# LautIOProto2.net
KiCad netlist of a schematic drawn in EAGLE
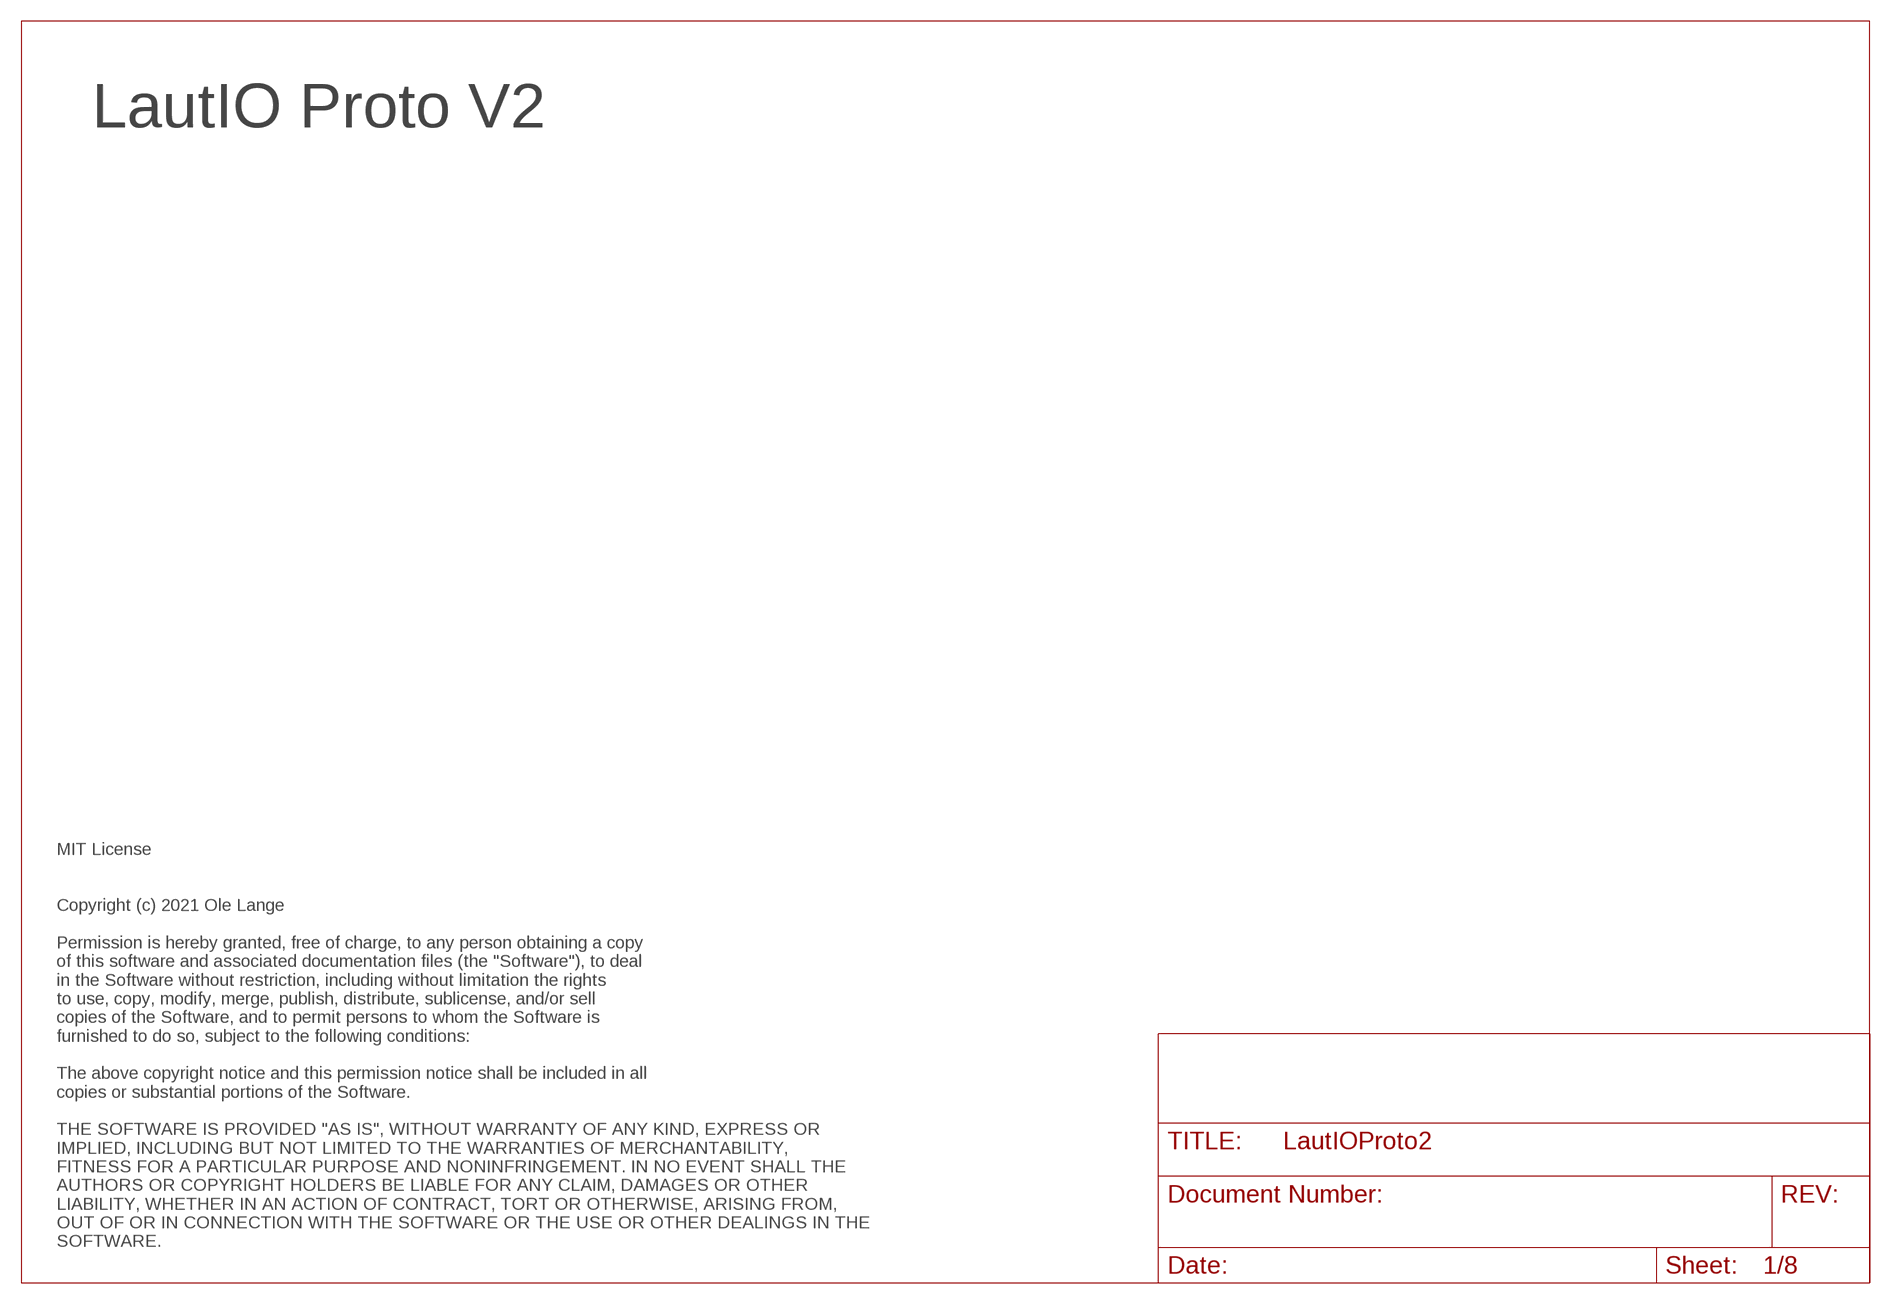
[diagram p0: schematic, sheet 1]
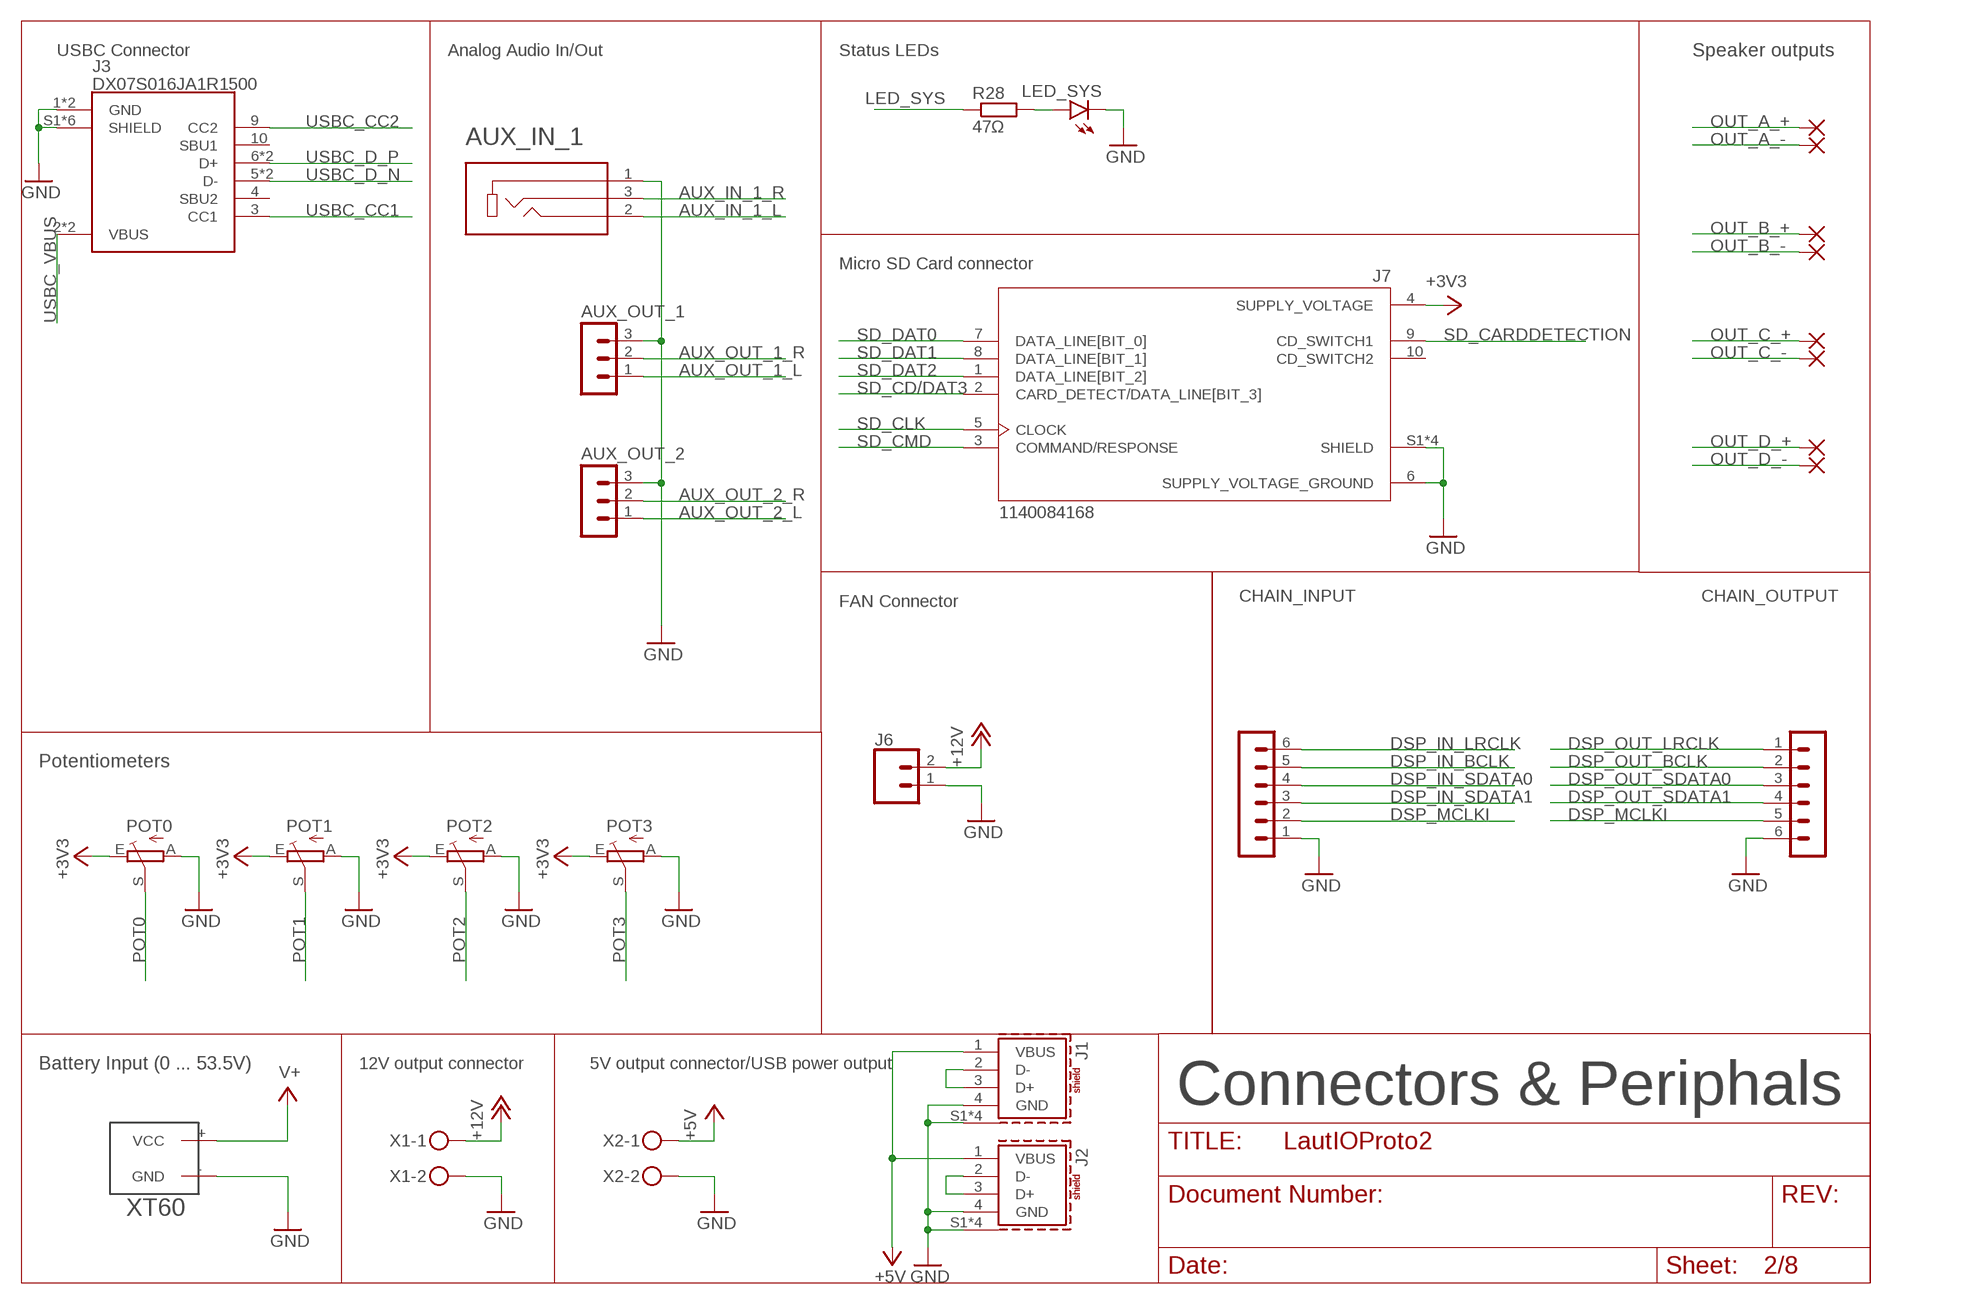
[diagram p1: schematic, sheet 2]
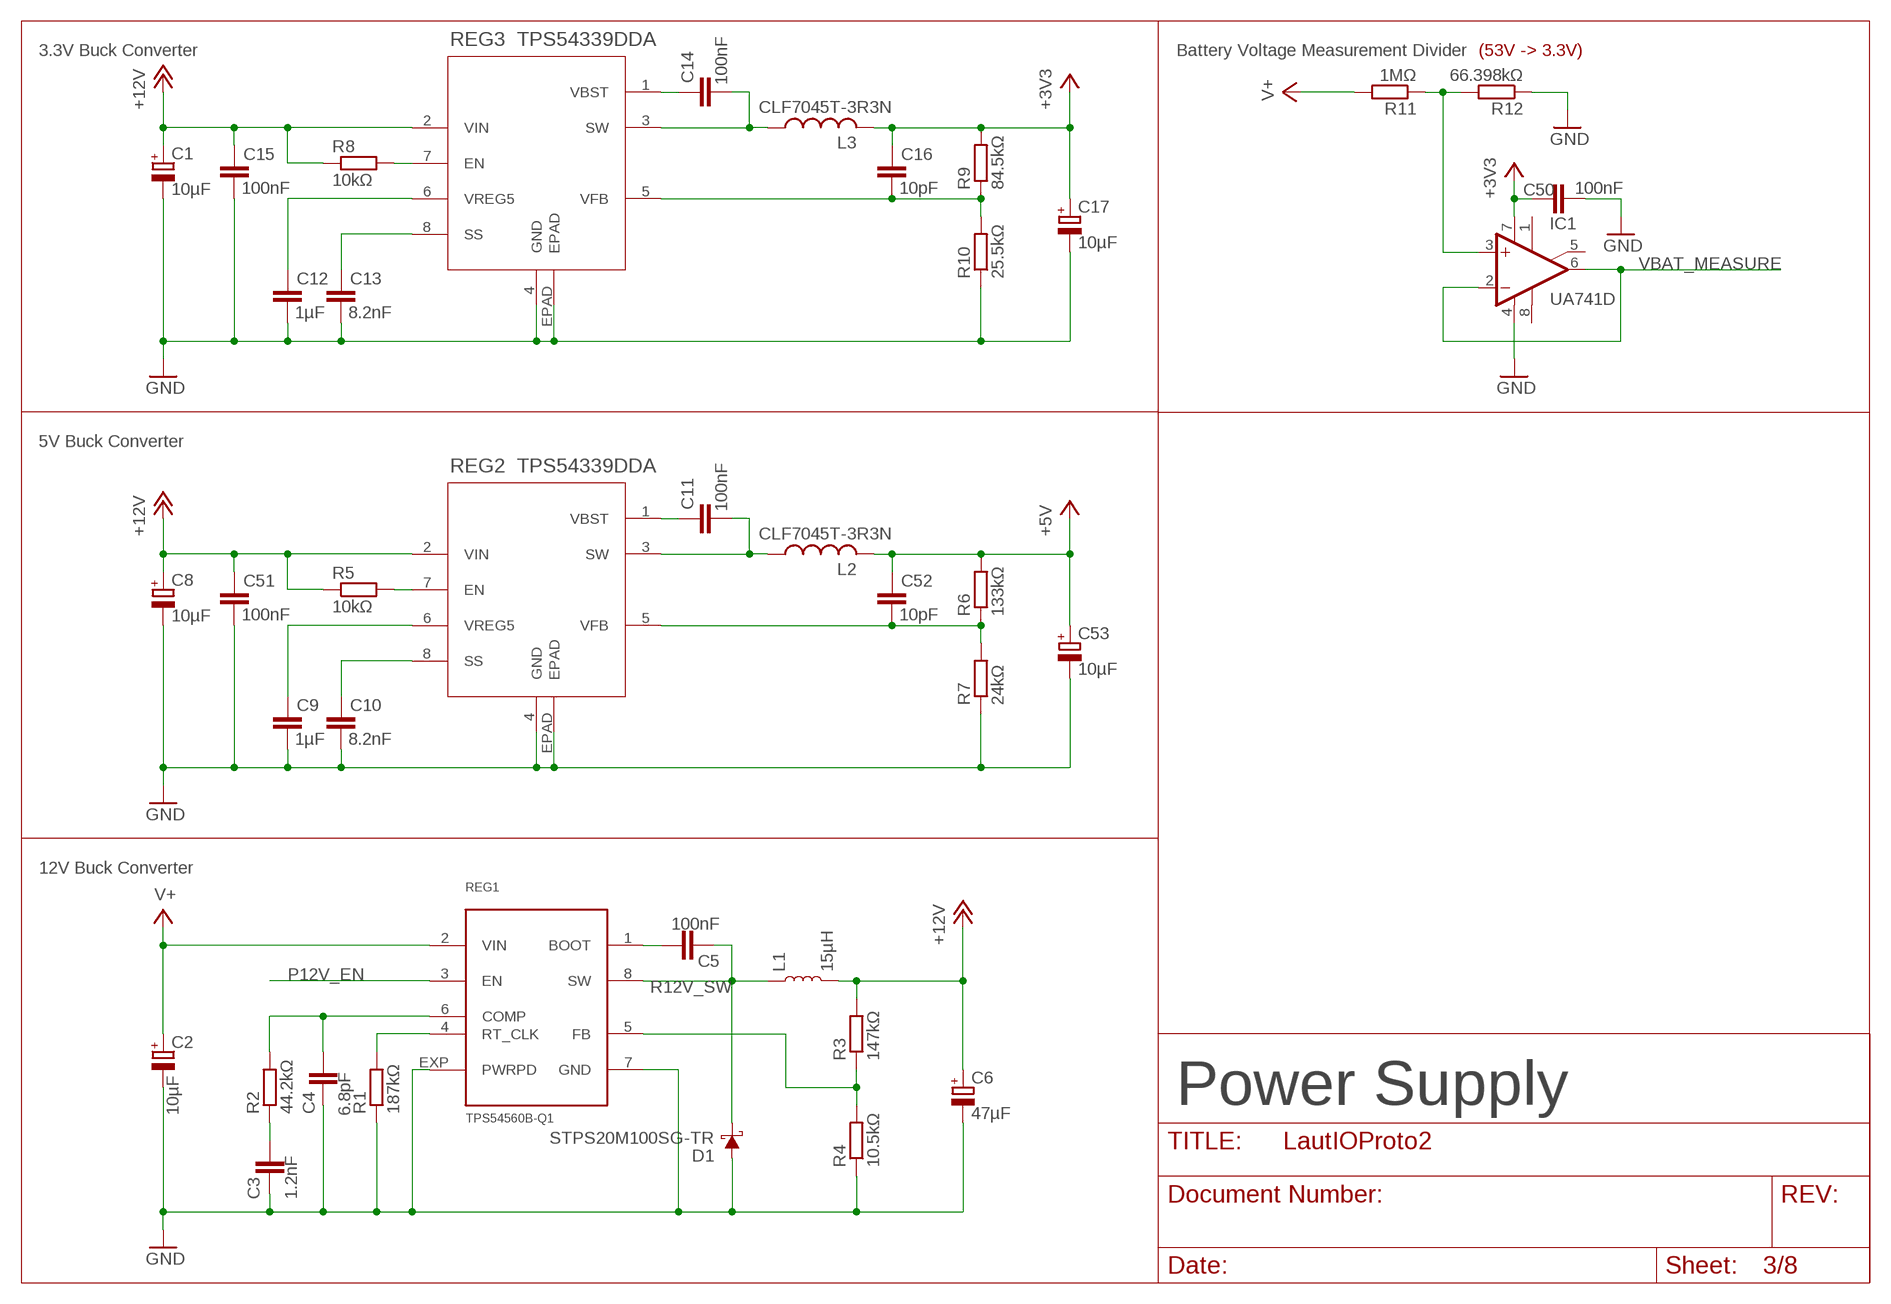
[diagram p2: schematic, sheet 3]
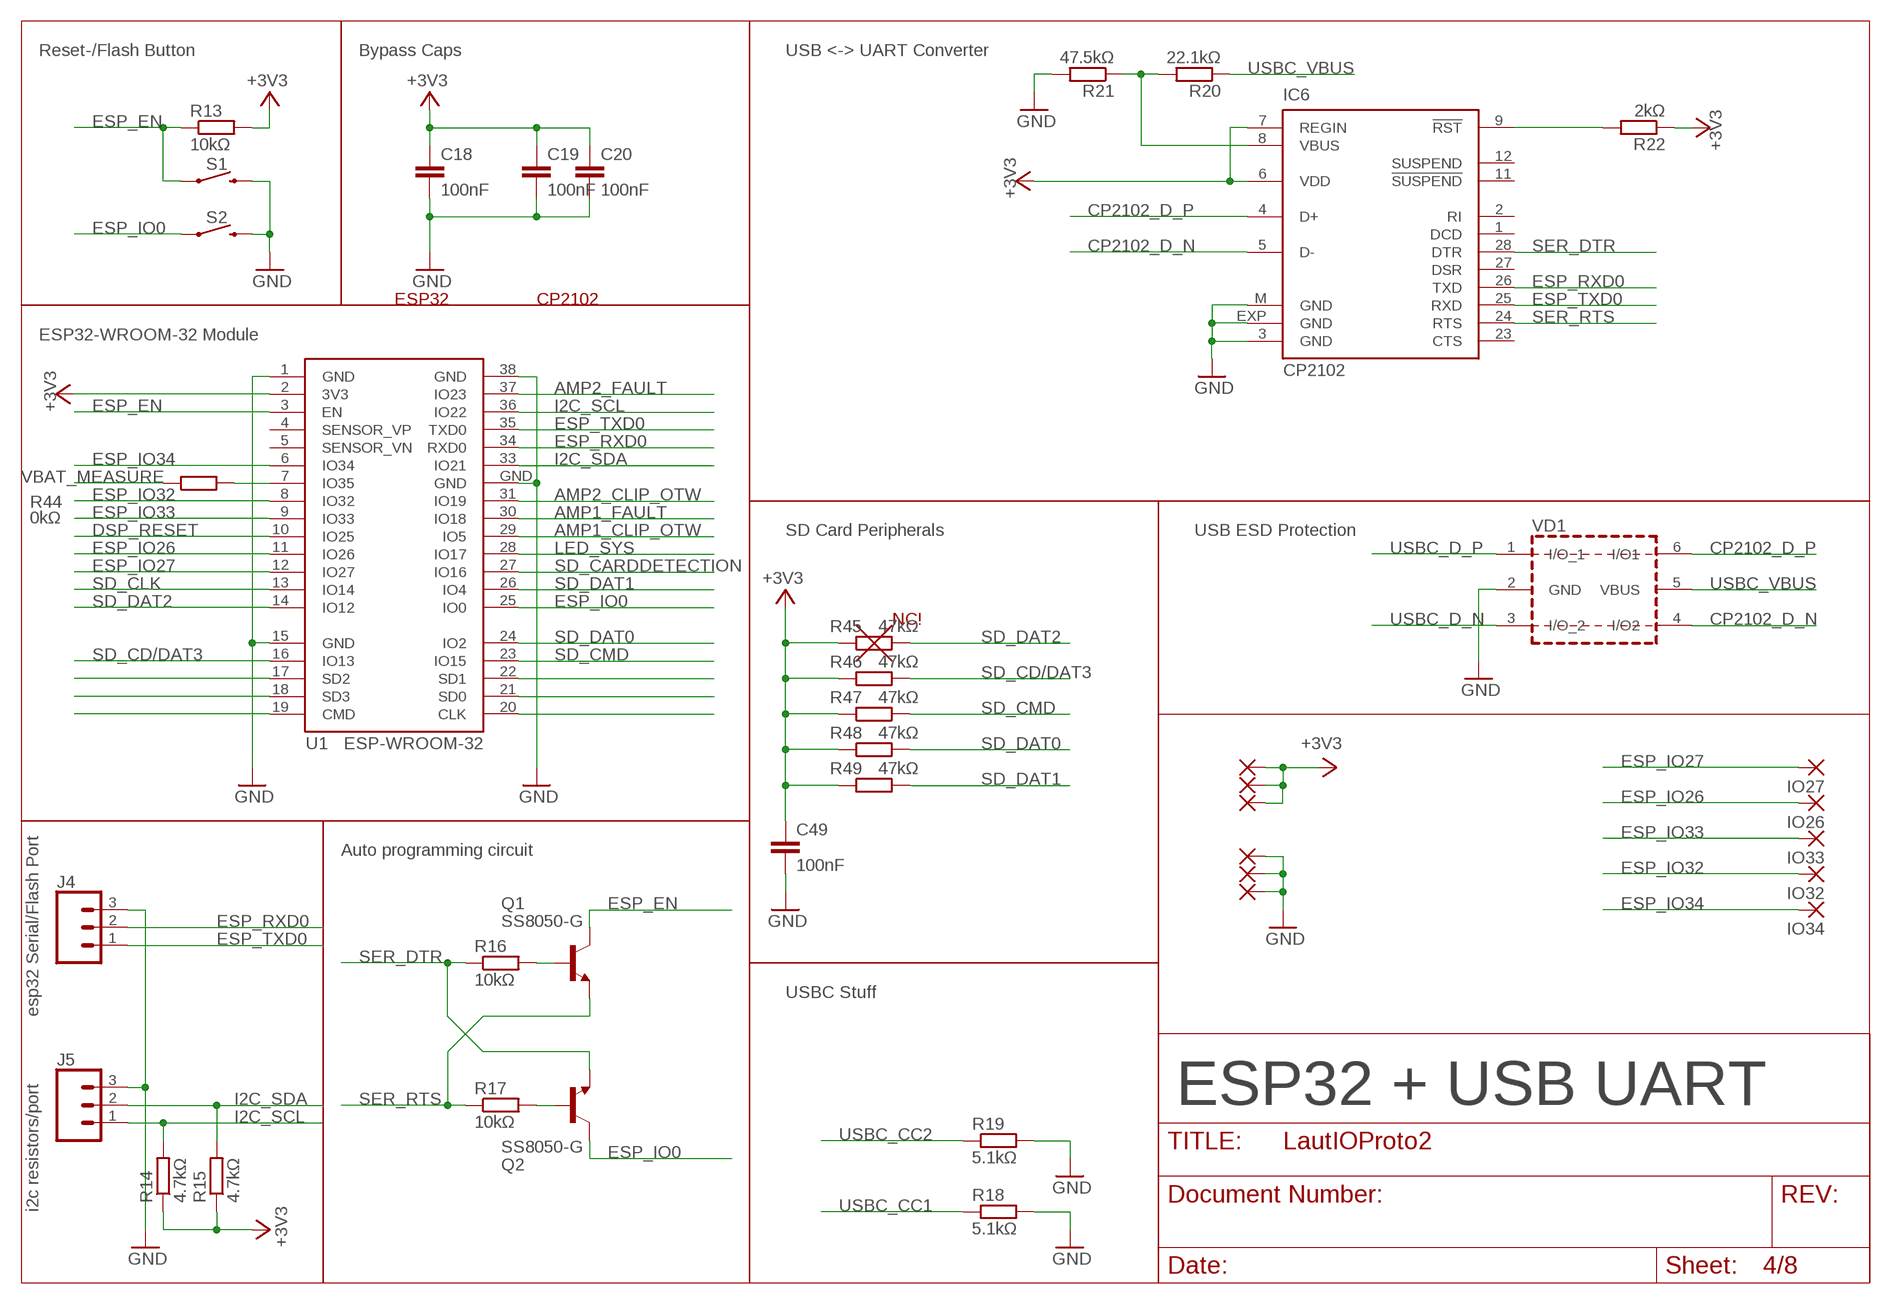
[diagram p3: schematic, sheet 4]
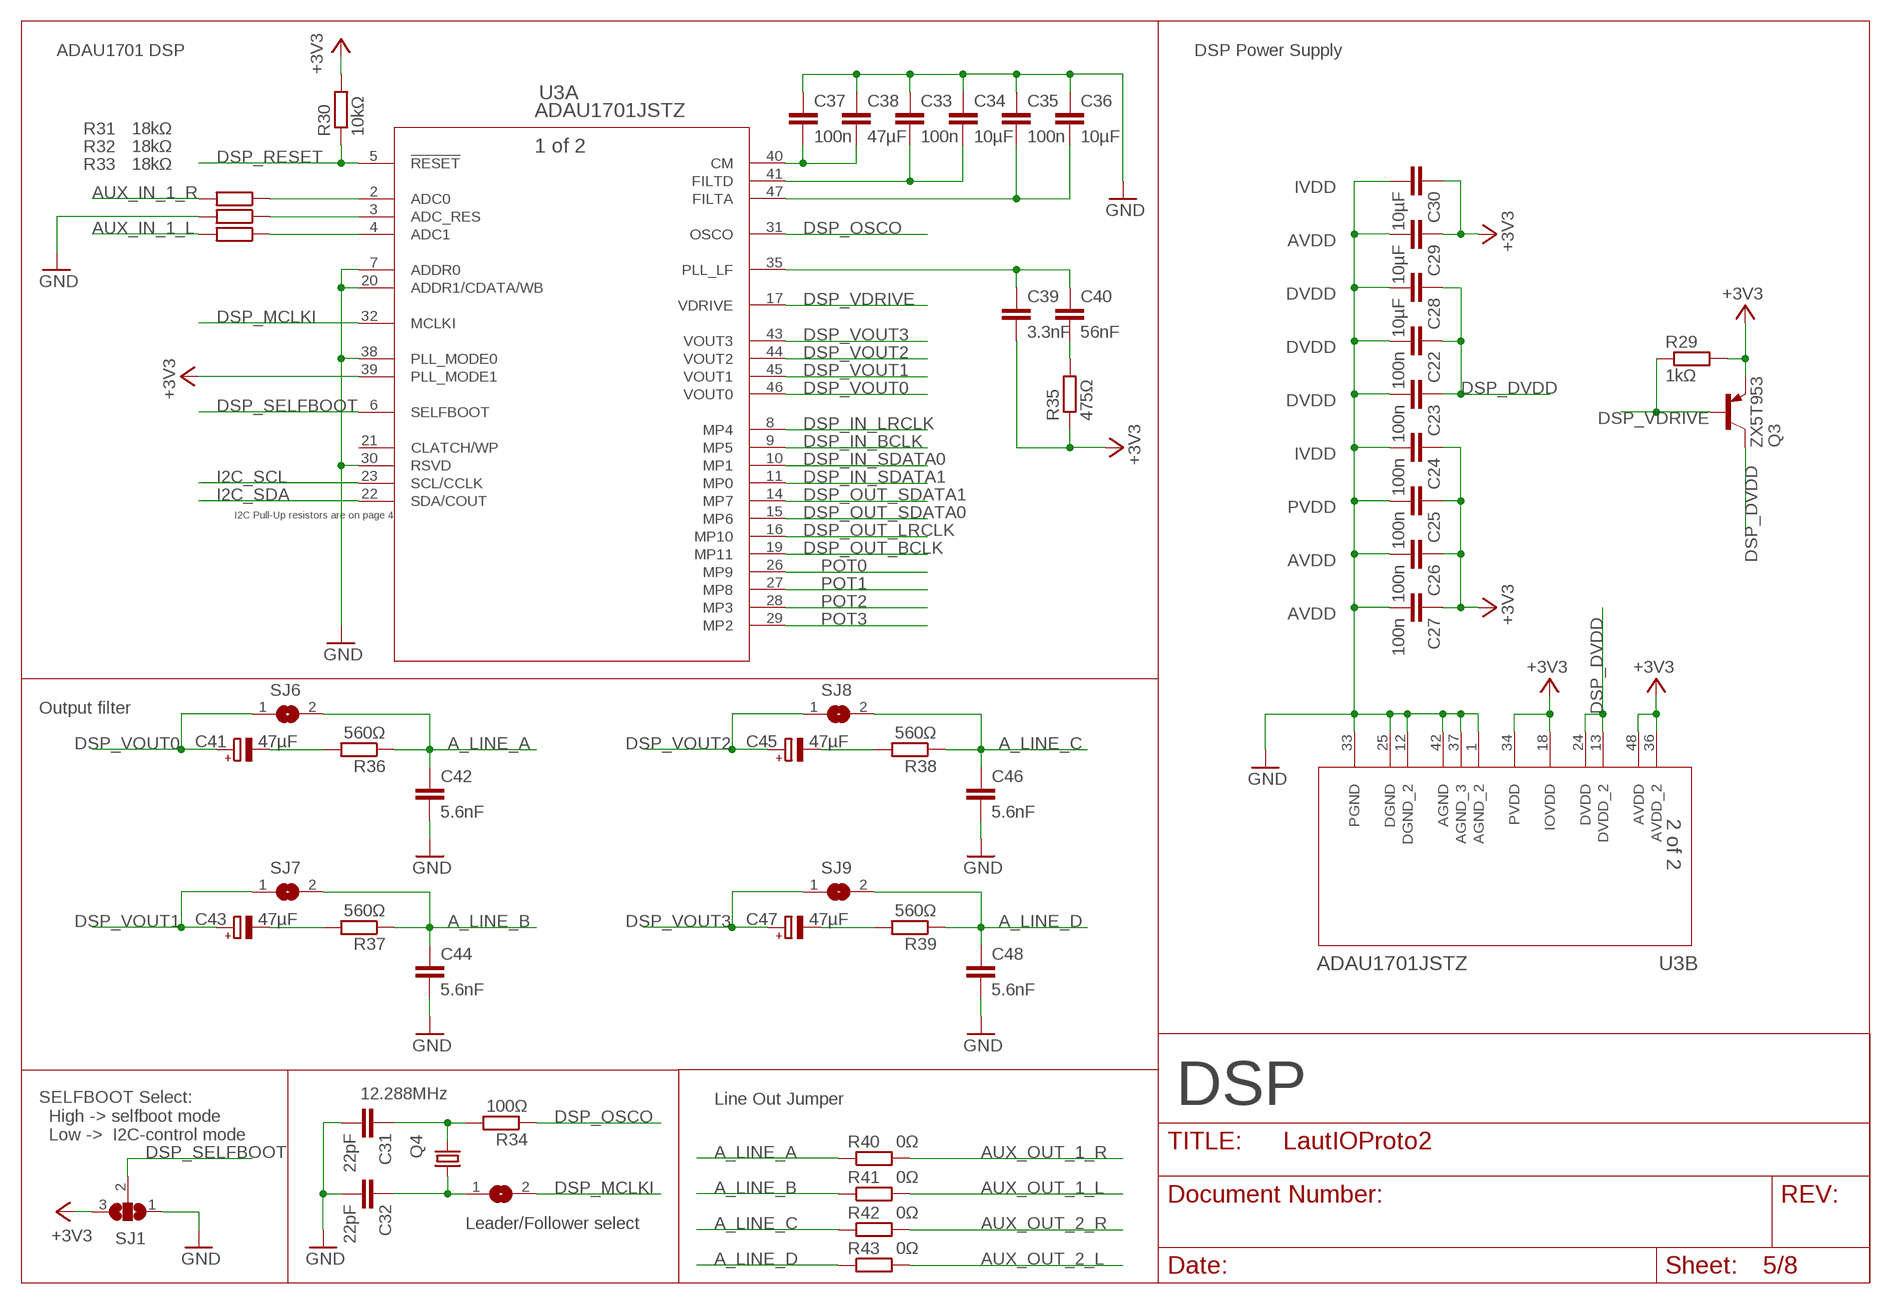
[diagram p4: schematic, sheet 5]
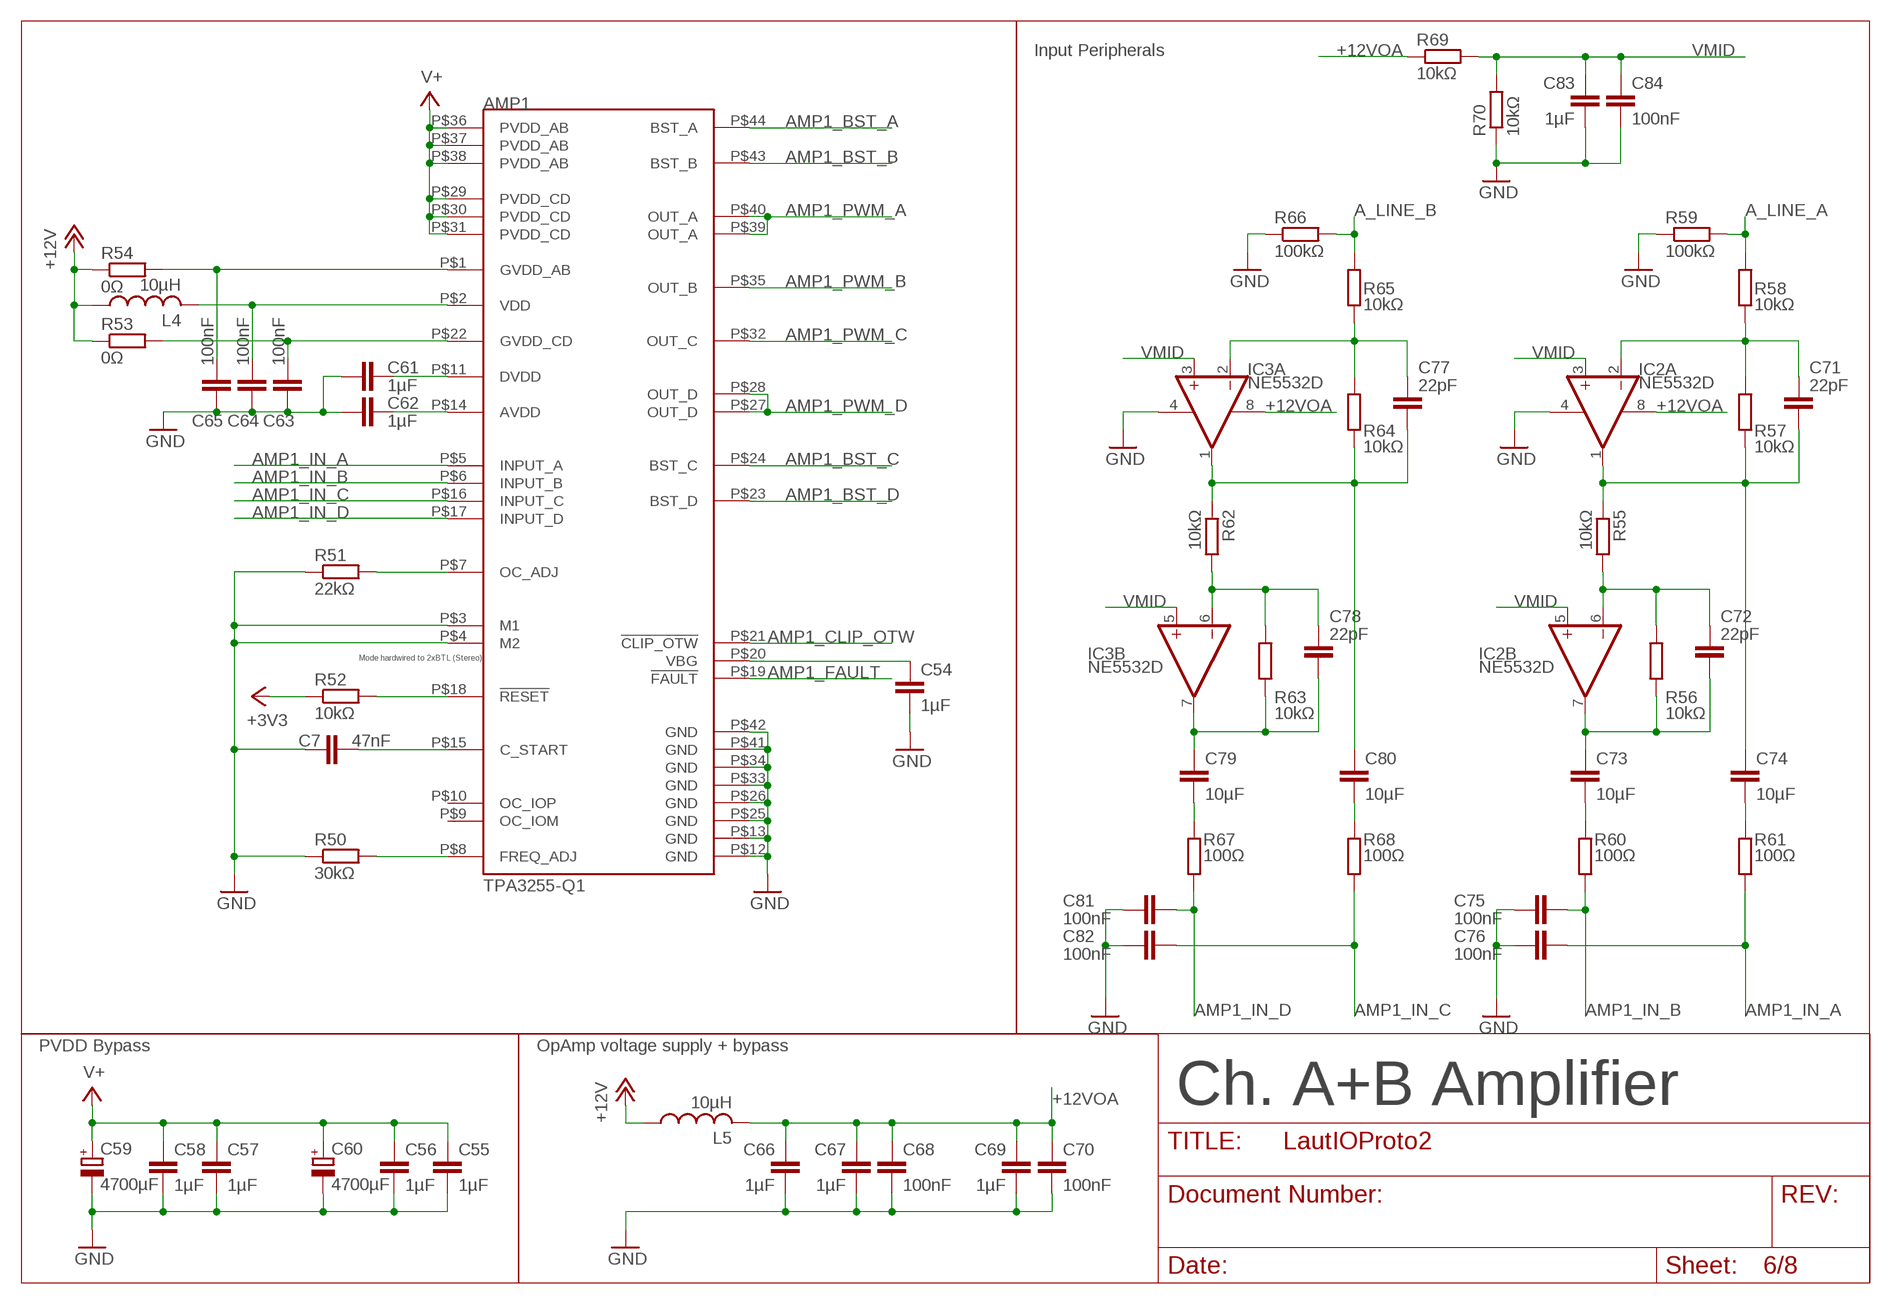
[diagram p5: schematic, sheet 6]
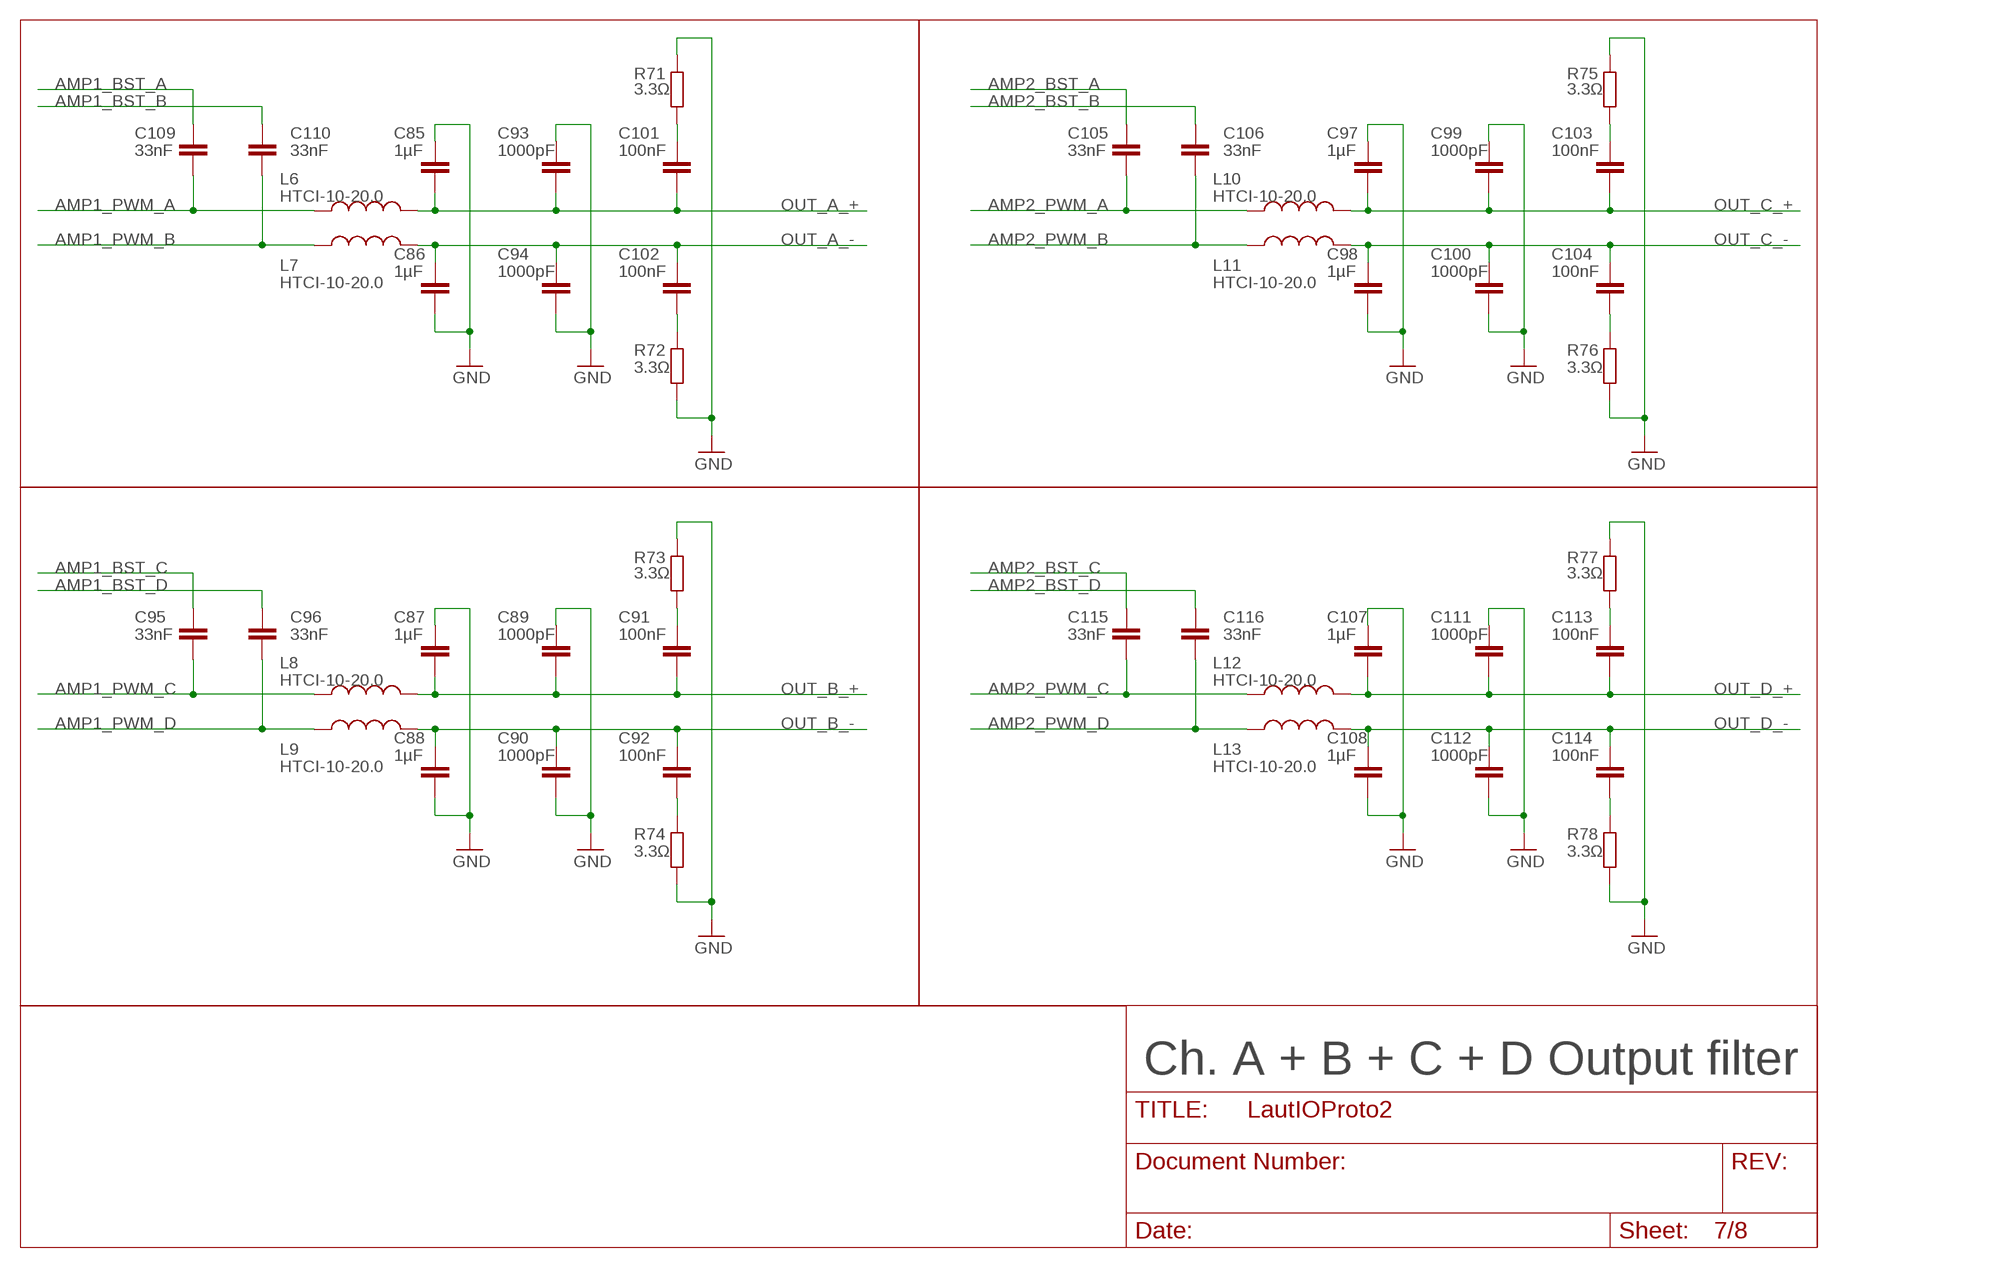
[diagram p6: schematic, sheet 7]
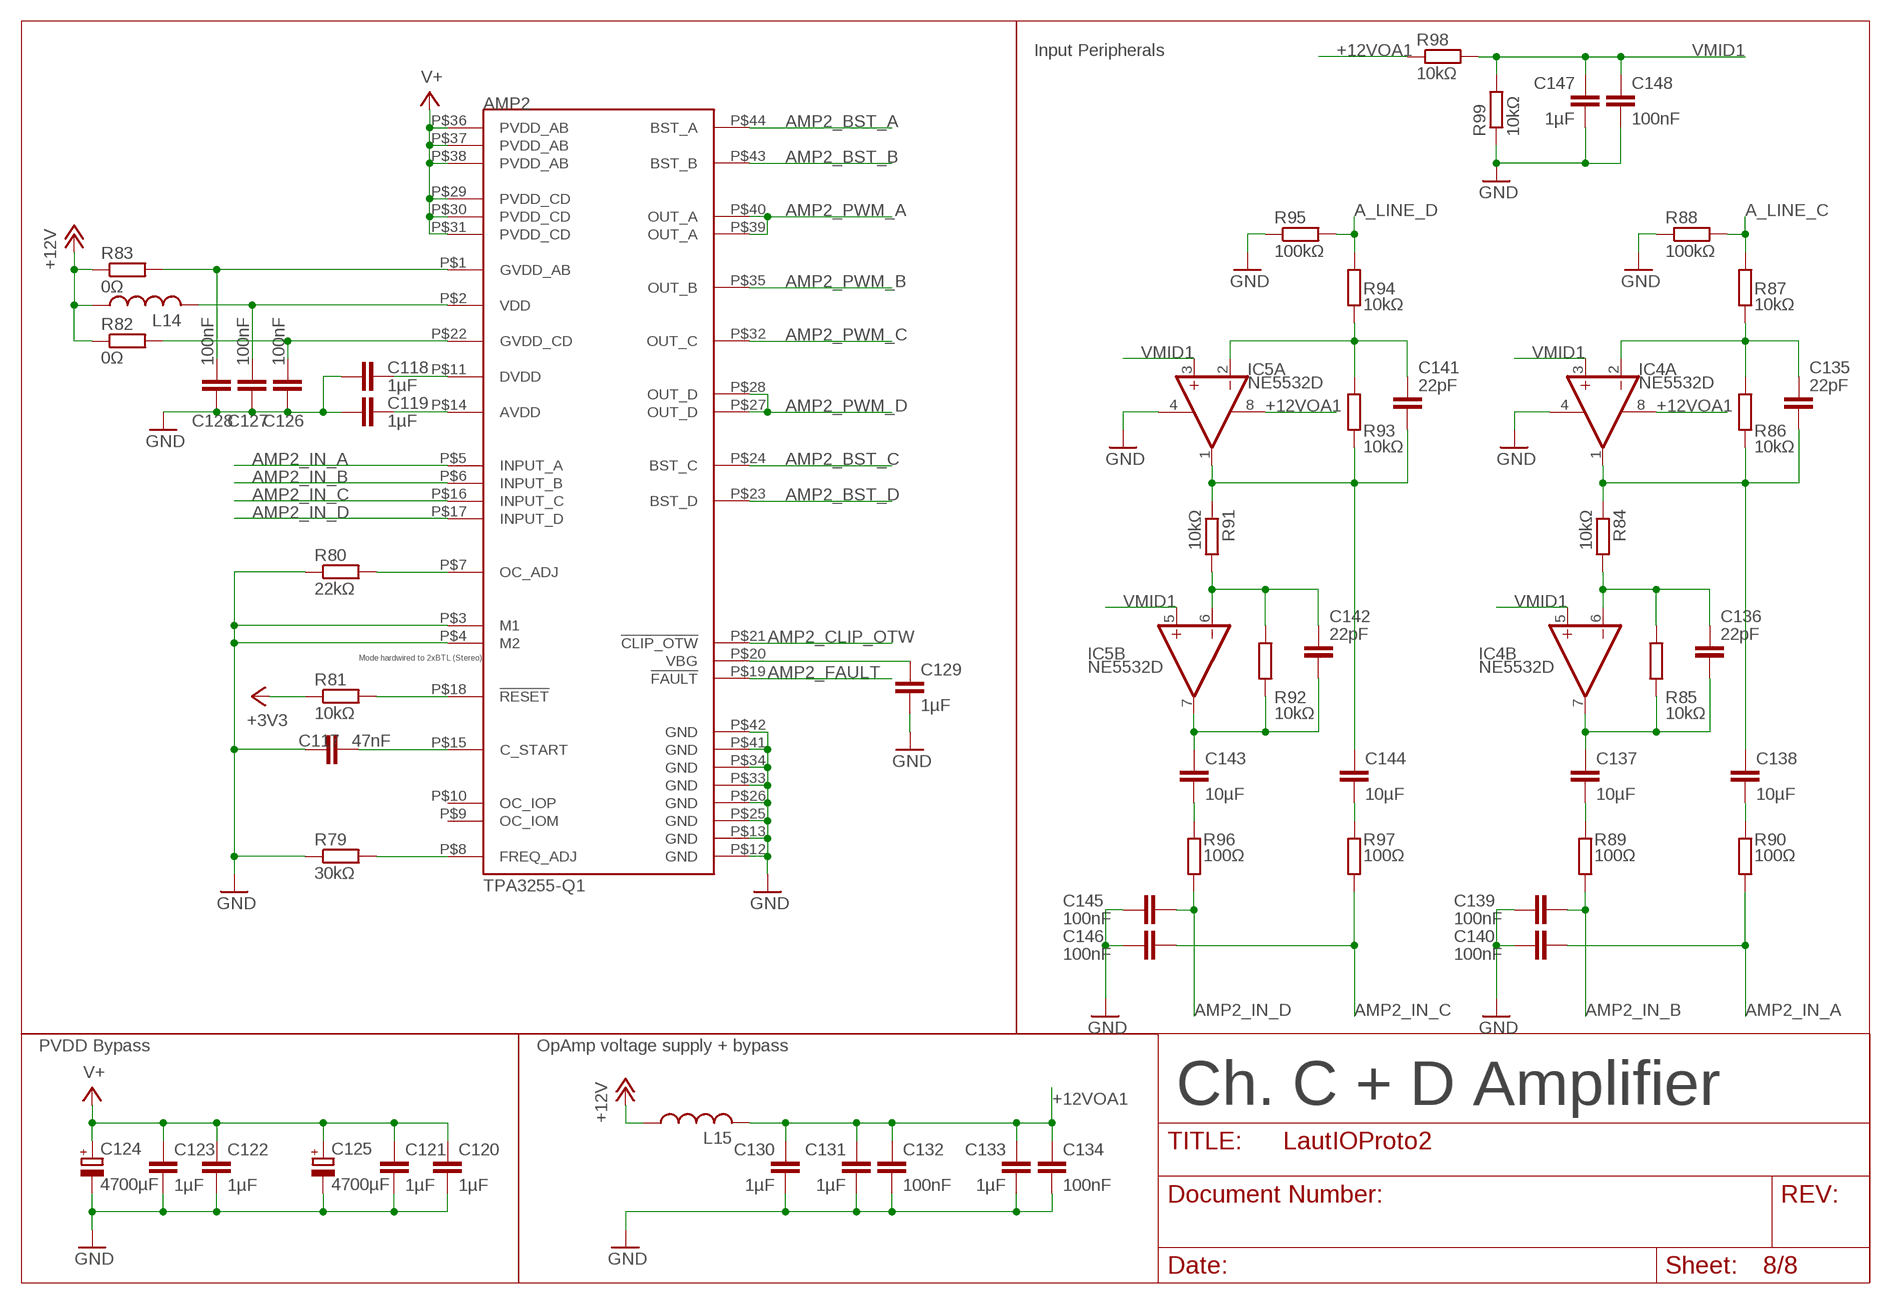
[diagram p7: schematic, sheet 8]

(export (version "E")
  (design (tool "Eeschema 10.0.6"))
  (components
    (comp (ref "AMP2")
      (value "TPA3255-Q1")
      (footprint "eagle-import:HTSSOP44")
      (libsource (lib "eagle-import") (part "TPA3255-Q1"))
    )
    (comp (ref "C117")
      (value "47nF")
      (footprint "eagle-import:C0603")
      (libsource (lib "eagle-import") (part "C-EUC0603"))
    )
    (comp (ref "C118")
      (value "1µF")
      (footprint "eagle-import:C3216")
      (libsource (lib "eagle-import") (part "C-EUC3216"))
    )
    (comp (ref "C119")
      (value "1µF")
      (footprint "eagle-import:C3216")
      (libsource (lib "eagle-import") (part "C-EUC3216"))
    )
    (comp (ref "C120")
      (value "1µF")
      (footprint "eagle-import:C3216")
      (libsource (lib "eagle-import") (part "C-EUC3216"))
    )
    (comp (ref "C121")
      (value "1µF")
      (footprint "eagle-import:C3216")
      (libsource (lib "eagle-import") (part "C-EUC3216"))
    )
    (comp (ref "C122")
      (value "1µF")
      (footprint "eagle-import:C3216")
      (libsource (lib "eagle-import") (part "C-EUC3216"))
    )
    (comp (ref "C123")
      (value "1µF")
      (footprint "eagle-import:C3216")
      (libsource (lib "eagle-import") (part "C-EUC3216"))
    )
    (comp (ref "C124")
      (value "4700µF")
      (footprint "eagle-import:EB22,5D")
      (libsource (lib "eagle-import") (part "CPOL-EUE10-22.5"))
    )
    (comp (ref "C125")
      (value "4700µF")
      (footprint "eagle-import:EB22,5D")
      (libsource (lib "eagle-import") (part "CPOL-EUE10-22.5"))
    )
    (comp (ref "C126")
      (value "100nF")
      (footprint "eagle-import:C0603")
      (libsource (lib "eagle-import") (part "C-EUC0603"))
    )
    (comp (ref "C127")
      (value "100nF")
      (footprint "eagle-import:C0603")
      (libsource (lib "eagle-import") (part "C-EUC0603"))
    )
    (comp (ref "C128")
      (value "100nF")
      (footprint "eagle-import:C0603")
      (libsource (lib "eagle-import") (part "C-EUC0603"))
    )
    (comp (ref "C129")
      (value "1µF")
      (footprint "eagle-import:C3216")
      (libsource (lib "eagle-import") (part "C-EUC3216"))
    )
    (comp (ref "C130")
      (value "1µF")
      (footprint "eagle-import:C3216")
      (libsource (lib "eagle-import") (part "C-EUC3216"))
    )
    (comp (ref "C131")
      (value "1µF")
      (footprint "eagle-import:C3216")
      (libsource (lib "eagle-import") (part "C-EUC3216"))
    )
    (comp (ref "C132")
      (value "100nF")
      (footprint "eagle-import:C0603")
      (libsource (lib "eagle-import") (part "C-EUC0603"))
    )
    (comp (ref "C133")
      (value "1µF")
      (footprint "eagle-import:C3216")
      (libsource (lib "eagle-import") (part "C-EUC3216"))
    )
    (comp (ref "C134")
      (value "100nF")
      (footprint "eagle-import:C0603")
      (libsource (lib "eagle-import") (part "C-EUC0603"))
    )
    (comp (ref "C135")
      (value "22pF")
      (footprint "eagle-import:C0603")
      (libsource (lib "eagle-import") (part "C-EUC0603"))
    )
    (comp (ref "C136")
      (value "22pF")
      (footprint "eagle-import:C0603")
      (libsource (lib "eagle-import") (part "C-EUC0603"))
    )
    (comp (ref "C137")
      (value "10µF")
      (footprint "eagle-import:C3216")
      (libsource (lib "eagle-import") (part "C-EUC3216"))
    )
    (comp (ref "C138")
      (value "10µF")
      (footprint "eagle-import:C3216")
      (libsource (lib "eagle-import") (part "C-EUC3216"))
    )
    (comp (ref "C139")
      (value "100nF")
      (footprint "eagle-import:C0603")
      (libsource (lib "eagle-import") (part "C-EUC0603"))
    )
    (comp (ref "C140")
      (value "100nF")
      (footprint "eagle-import:C0603")
      (libsource (lib "eagle-import") (part "C-EUC0603"))
    )
    (comp (ref "C141")
      (value "22pF")
      (footprint "eagle-import:C0603")
      (libsource (lib "eagle-import") (part "C-EUC0603"))
    )
    (comp (ref "C142")
      (value "22pF")
      (footprint "eagle-import:C0603")
      (libsource (lib "eagle-import") (part "C-EUC0603"))
    )
    (comp (ref "C143")
      (value "10µF")
      (footprint "eagle-import:C3216")
      (libsource (lib "eagle-import") (part "C-EUC3216"))
    )
    (comp (ref "C144")
      (value "10µF")
      (footprint "eagle-import:C3216")
      (libsource (lib "eagle-import") (part "C-EUC3216"))
    )
    (comp (ref "C145")
      (value "100nF")
      (footprint "eagle-import:C0603")
      (libsource (lib "eagle-import") (part "C-EUC0603"))
    )
    (comp (ref "C146")
      (value "100nF")
      (footprint "eagle-import:C0603")
      (libsource (lib "eagle-import") (part "C-EUC0603"))
    )
    (comp (ref "C147")
      (value "1µF")
      (footprint "eagle-import:C3216")
      (libsource (lib "eagle-import") (part "C-EUC3216"))
    )
    (comp (ref "C148")
      (value "100nF")
      (footprint "eagle-import:C0603")
      (libsource (lib "eagle-import") (part "C-EUC0603"))
    )
    (comp (ref "IC4")
      (value "NE5532D")
      (footprint "eagle-import:SO08")
      (libsource (lib "eagle-import") (part "NE5532D"))
    )
    (comp (ref "IC5")
      (value "NE5532D")
      (footprint "eagle-import:SO08")
      (libsource (lib "eagle-import") (part "NE5532D"))
    )
    (comp (ref "L14")
      (value "L-USL2012C")
      (footprint "eagle-import:L2012C")
      (libsource (lib "eagle-import") (part "L-USL2012C"))
    )
    (comp (ref "L15")
      (value "L-USL2012C")
      (footprint "eagle-import:L2012C")
      (libsource (lib "eagle-import") (part "L-USL2012C"))
    )
    (comp (ref "R79")
      (value "30kΩ")
      (footprint "eagle-import:R0603")
      (libsource (lib "eagle-import") (part "R-EU_R0603"))
    )
    (comp (ref "R80")
      (value "22kΩ")
      (footprint "eagle-import:R0603")
      (libsource (lib "eagle-import") (part "R-EU_R0603"))
    )
    (comp (ref "R81")
      (value "10kΩ")
      (footprint "eagle-import:R0603")
      (libsource (lib "eagle-import") (part "R-EU_R0603"))
    )
    (comp (ref "R82")
      (value "0Ω")
      (footprint "eagle-import:R0603")
      (libsource (lib "eagle-import") (part "R-EU_R0603"))
    )
    (comp (ref "R83")
      (value "0Ω")
      (footprint "eagle-import:R0603")
      (libsource (lib "eagle-import") (part "R-EU_R0603"))
    )
    (comp (ref "R84")
      (value "10kΩ")
      (footprint "eagle-import:R0603")
      (libsource (lib "eagle-import") (part "R-EU_R0603"))
    )
    (comp (ref "R85")
      (value "10kΩ")
      (footprint "eagle-import:R0603")
      (libsource (lib "eagle-import") (part "R-EU_R0603"))
    )
    (comp (ref "R86")
      (value "10kΩ")
      (footprint "eagle-import:R0603")
      (libsource (lib "eagle-import") (part "R-EU_R0603"))
    )
    (comp (ref "R87")
      (value "10kΩ")
      (footprint "eagle-import:R0603")
      (libsource (lib "eagle-import") (part "R-EU_R0603"))
    )
    (comp (ref "R88")
      (value "100kΩ")
      (footprint "eagle-import:R0603")
      (libsource (lib "eagle-import") (part "R-EU_R0603"))
    )
    (comp (ref "R89")
      (value "100Ω")
      (footprint "eagle-import:R0603")
      (libsource (lib "eagle-import") (part "R-EU_R0603"))
    )
    (comp (ref "R90")
      (value "100Ω")
      (footprint "eagle-import:R0603")
      (libsource (lib "eagle-import") (part "R-EU_R0603"))
    )
    (comp (ref "R91")
      (value "10kΩ")
      (footprint "eagle-import:R0603")
      (libsource (lib "eagle-import") (part "R-EU_R0603"))
    )
    (comp (ref "R92")
      (value "10kΩ")
      (footprint "eagle-import:R0603")
      (libsource (lib "eagle-import") (part "R-EU_R0603"))
    )
    (comp (ref "R93")
      (value "10kΩ")
      (footprint "eagle-import:R0603")
      (libsource (lib "eagle-import") (part "R-EU_R0603"))
    )
    (comp (ref "R94")
      (value "10kΩ")
      (footprint "eagle-import:R0603")
      (libsource (lib "eagle-import") (part "R-EU_R0603"))
    )
    (comp (ref "R95")
      (value "100kΩ")
      (footprint "eagle-import:R0603")
      (libsource (lib "eagle-import") (part "R-EU_R0603"))
    )
    (comp (ref "R96")
      (value "100Ω")
      (footprint "eagle-import:R0603")
      (libsource (lib "eagle-import") (part "R-EU_R0603"))
    )
    (comp (ref "R97")
      (value "100Ω")
      (footprint "eagle-import:R0603")
      (libsource (lib "eagle-import") (part "R-EU_R0603"))
    )
    (comp (ref "R98")
      (value "10kΩ")
      (footprint "eagle-import:R0603")
      (libsource (lib "eagle-import") (part "R-EU_R0603"))
    )
    (comp (ref "R99")
      (value "10kΩ")
      (footprint "eagle-import:R0603")
      (libsource (lib "eagle-import") (part "R-EU_R0603"))
    )
    (comp (ref "AMP1")
      (value "TPA3255-Q1")
      (footprint "eagle-import:HTSSOP44")
      (libsource (lib "eagle-import") (part "TPA3255-Q1"))
    )
    (comp (ref "C7")
      (value "47nF")
      (footprint "eagle-import:C0603")
      (libsource (lib "eagle-import") (part "C-EUC0603"))
    )
    (comp (ref "C54")
      (value "1µF")
      (footprint "eagle-import:C3216")
      (libsource (lib "eagle-import") (part "C-EUC3216"))
    )
    (comp (ref "C55")
      (value "1µF")
      (footprint "eagle-import:C3216")
      (libsource (lib "eagle-import") (part "C-EUC3216"))
    )
    (comp (ref "C56")
      (value "1µF")
      (footprint "eagle-import:C3216")
      (libsource (lib "eagle-import") (part "C-EUC3216"))
    )
    (comp (ref "C57")
      (value "1µF")
      (footprint "eagle-import:C3216")
      (libsource (lib "eagle-import") (part "C-EUC3216"))
    )
    (comp (ref "C58")
      (value "1µF")
      (footprint "eagle-import:C3216")
      (libsource (lib "eagle-import") (part "C-EUC3216"))
    )
    (comp (ref "C59")
      (value "4700µF")
      (footprint "eagle-import:EB22,5D")
      (libsource (lib "eagle-import") (part "CPOL-EUE10-22.5"))
    )
    (comp (ref "C60")
      (value "4700µF")
      (footprint "eagle-import:EB22,5D")
      (libsource (lib "eagle-import") (part "CPOL-EUE10-22.5"))
    )
    (comp (ref "C61")
      (value "1µF")
      (footprint "eagle-import:C3216")
      (libsource (lib "eagle-import") (part "C-EUC3216"))
    )
    (comp (ref "C62")
      (value "1µF")
      (footprint "eagle-import:C3216")
      (libsource (lib "eagle-import") (part "C-EUC3216"))
    )
    (comp (ref "C63")
      (value "100nF")
      (footprint "eagle-import:C0603")
      (libsource (lib "eagle-import") (part "C-EUC0603"))
    )
    (comp (ref "C64")
      (value "100nF")
      (footprint "eagle-import:C0603")
      (libsource (lib "eagle-import") (part "C-EUC0603"))
    )
    (comp (ref "C65")
      (value "100nF")
      (footprint "eagle-import:C0603")
      (libsource (lib "eagle-import") (part "C-EUC0603"))
    )
    (comp (ref "C66")
      (value "1µF")
      (footprint "eagle-import:C3216")
      (libsource (lib "eagle-import") (part "C-EUC3216"))
    )
    (comp (ref "C67")
      (value "1µF")
      (footprint "eagle-import:C3216")
      (libsource (lib "eagle-import") (part "C-EUC3216"))
    )
    (comp (ref "C68")
      (value "100nF")
      (footprint "eagle-import:C0603")
      (libsource (lib "eagle-import") (part "C-EUC0603"))
    )
    (comp (ref "C69")
      (value "1µF")
      (footprint "eagle-import:C3216")
      (libsource (lib "eagle-import") (part "C-EUC3216"))
    )
    (comp (ref "C70")
      (value "100nF")
      (footprint "eagle-import:C0603")
      (libsource (lib "eagle-import") (part "C-EUC0603"))
    )
    (comp (ref "C71")
      (value "22pF")
      (footprint "eagle-import:C0603")
      (libsource (lib "eagle-import") (part "C-EUC0603"))
    )
    (comp (ref "C72")
      (value "22pF")
      (footprint "eagle-import:C0603")
      (libsource (lib "eagle-import") (part "C-EUC0603"))
    )
    (comp (ref "C73")
      (value "10µF")
      (footprint "eagle-import:C3216")
      (libsource (lib "eagle-import") (part "C-EUC3216"))
    )
    (comp (ref "C74")
      (value "10µF")
      (footprint "eagle-import:C3216")
      (libsource (lib "eagle-import") (part "C-EUC3216"))
    )
    (comp (ref "C75")
      (value "100nF")
      (footprint "eagle-import:C0603")
      (libsource (lib "eagle-import") (part "C-EUC0603"))
    )
    (comp (ref "C76")
      (value "100nF")
      (footprint "eagle-import:C0603")
      (libsource (lib "eagle-import") (part "C-EUC0603"))
    )
    (comp (ref "C77")
      (value "22pF")
      (footprint "eagle-import:C0603")
      (libsource (lib "eagle-import") (part "C-EUC0603"))
    )
    (comp (ref "C78")
      (value "22pF")
      (footprint "eagle-import:C0603")
      (libsource (lib "eagle-import") (part "C-EUC0603"))
    )
    (comp (ref "C79")
      (value "10µF")
      (footprint "eagle-import:C3216")
      (libsource (lib "eagle-import") (part "C-EUC3216"))
    )
    (comp (ref "C80")
      (value "10µF")
      (footprint "eagle-import:C3216")
      (libsource (lib "eagle-import") (part "C-EUC3216"))
    )
    (comp (ref "C81")
      (value "100nF")
      (footprint "eagle-import:C0603")
      (libsource (lib "eagle-import") (part "C-EUC0603"))
    )
    (comp (ref "C82")
      (value "100nF")
      (footprint "eagle-import:C0603")
      (libsource (lib "eagle-import") (part "C-EUC0603"))
    )
    (comp (ref "C83")
      (value "1µF")
      (footprint "eagle-import:C3216")
      (libsource (lib "eagle-import") (part "C-EUC3216"))
    )
    (comp (ref "C84")
      (value "100nF")
      (footprint "eagle-import:C0603")
      (libsource (lib "eagle-import") (part "C-EUC0603"))
    )
    (comp (ref "IC2")
      (value "NE5532D")
      (footprint "eagle-import:SO08")
      (libsource (lib "eagle-import") (part "NE5532D"))
    )
    (comp (ref "IC3")
      (value "NE5532D")
      (footprint "eagle-import:SO08")
      (libsource (lib "eagle-import") (part "NE5532D"))
    )
    (comp (ref "L4")
      (value "10µH")
      (footprint "eagle-import:L2012C")
      (libsource (lib "eagle-import") (part "L-USL2012C"))
    )
    (comp (ref "L5")
      (value "10µH")
      (footprint "eagle-import:L2012C")
      (libsource (lib "eagle-import") (part "L-USL2012C"))
    )
    (comp (ref "R50")
      (value "30kΩ")
      (footprint "eagle-import:R0603")
      (libsource (lib "eagle-import") (part "R-EU_R0603"))
    )
    (comp (ref "R51")
      (value "22kΩ")
      (footprint "eagle-import:R0603")
      (libsource (lib "eagle-import") (part "R-EU_R0603"))
    )
    (comp (ref "R52")
      (value "10kΩ")
      (footprint "eagle-import:R0603")
      (libsource (lib "eagle-import") (part "R-EU_R0603"))
    )
    (comp (ref "R53")
      (value "0Ω")
      (footprint "eagle-import:R0603")
      (libsource (lib "eagle-import") (part "R-EU_R0603"))
    )
    (comp (ref "R54")
      (value "0Ω")
      (footprint "eagle-import:R0603")
      (libsource (lib "eagle-import") (part "R-EU_R0603"))
    )
    (comp (ref "R55")
      (value "10kΩ")
      (footprint "eagle-import:R0603")
      (libsource (lib "eagle-import") (part "R-EU_R0603"))
    )
    (comp (ref "R56")
      (value "10kΩ")
      (footprint "eagle-import:R0603")
      (libsource (lib "eagle-import") (part "R-EU_R0603"))
    )
    (comp (ref "R57")
      (value "10kΩ")
      (footprint "eagle-import:R0603")
      (libsource (lib "eagle-import") (part "R-EU_R0603"))
    )
    (comp (ref "R58")
      (value "10kΩ")
      (footprint "eagle-import:R0603")
      (libsource (lib "eagle-import") (part "R-EU_R0603"))
    )
    (comp (ref "R59")
      (value "100kΩ")
      (footprint "eagle-import:R0603")
      (libsource (lib "eagle-import") (part "R-EU_R0603"))
    )
    (comp (ref "R60")
      (value "100Ω")
      (footprint "eagle-import:R0603")
      (libsource (lib "eagle-import") (part "R-EU_R0603"))
    )
    (comp (ref "R61")
      (value "100Ω")
      (footprint "eagle-import:R0603")
      (libsource (lib "eagle-import") (part "R-EU_R0603"))
    )
    (comp (ref "R62")
      (value "10kΩ")
      (footprint "eagle-import:R0603")
      (libsource (lib "eagle-import") (part "R-EU_R0603"))
    )
    (comp (ref "R63")
      (value "10kΩ")
      (footprint "eagle-import:R0603")
      (libsource (lib "eagle-import") (part "R-EU_R0603"))
    )
    (comp (ref "R64")
      (value "10kΩ")
      (footprint "eagle-import:R0603")
      (libsource (lib "eagle-import") (part "R-EU_R0603"))
    )
    (comp (ref "R65")
      (value "10kΩ")
      (footprint "eagle-import:R0603")
      (libsource (lib "eagle-import") (part "R-EU_R0603"))
    )
    (comp (ref "R66")
      (value "100kΩ")
      (footprint "eagle-import:R0603")
      (libsource (lib "eagle-import") (part "R-EU_R0603"))
    )
    (comp (ref "R67")
      (value "100Ω")
      (footprint "eagle-import:R0603")
      (libsource (lib "eagle-import") (part "R-EU_R0603"))
    )
    (comp (ref "R68")
      (value "100Ω")
      (footprint "eagle-import:R0603")
      (libsource (lib "eagle-import") (part "R-EU_R0603"))
    )
    (comp (ref "R69")
      (value "10kΩ")
      (footprint "eagle-import:R0603")
      (libsource (lib "eagle-import") (part "R-EU_R0603"))
    )
    (comp (ref "R70")
      (value "10kΩ")
      (footprint "eagle-import:R0603")
      (libsource (lib "eagle-import") (part "R-EU_R0603"))
    )
    (comp (ref "C22")
      (value "100n")
      (footprint "eagle-import:C0603")
      (libsource (lib "eagle-import") (part "C-EUC0603"))
    )
    (comp (ref "C23")
      (value "100n")
      (footprint "eagle-import:C0603")
      (libsource (lib "eagle-import") (part "C-EUC0603"))
    )
    (comp (ref "C24")
      (value "100n")
      (footprint "eagle-import:C0603")
      (libsource (lib "eagle-import") (part "C-EUC0603"))
    )
    (comp (ref "C25")
      (value "100n")
      (footprint "eagle-import:C0603")
      (libsource (lib "eagle-import") (part "C-EUC0603"))
    )
    (comp (ref "C26")
      (value "100n")
      (footprint "eagle-import:C0603")
      (libsource (lib "eagle-import") (part "C-EUC0603"))
    )
    (comp (ref "C27")
      (value "100n")
      (footprint "eagle-import:C0603")
      (libsource (lib "eagle-import") (part "C-EUC0603"))
    )
    (comp (ref "C28")
      (value "10µF")
      (footprint "eagle-import:C1206K")
      (libsource (lib "eagle-import") (part "C-EUC1206K"))
    )
    (comp (ref "C29")
      (value "10µF")
      (footprint "eagle-import:C1206K")
      (libsource (lib "eagle-import") (part "C-EUC1206K"))
    )
    (comp (ref "C30")
      (value "10µF")
      (footprint "eagle-import:C1206K")
      (libsource (lib "eagle-import") (part "C-EUC1206K"))
    )
    (comp (ref "C31")
      (value "22pF")
      (footprint "eagle-import:C0603")
      (libsource (lib "eagle-import") (part "C-EUC0603"))
    )
    (comp (ref "C32")
      (value "22pF")
      (footprint "eagle-import:C0603")
      (libsource (lib "eagle-import") (part "C-EUC0603"))
    )
    (comp (ref "C33")
      (value "100n")
      (footprint "eagle-import:C0603")
      (libsource (lib "eagle-import") (part "C-EUC0603"))
    )
    (comp (ref "C34")
      (value "10µF")
      (footprint "eagle-import:C1206K")
      (libsource (lib "eagle-import") (part "C-EUC1206K"))
    )
    (comp (ref "C35")
      (value "100n")
      (footprint "eagle-import:C0603")
      (libsource (lib "eagle-import") (part "C-EUC0603"))
    )
    (comp (ref "C36")
      (value "10µF")
      (footprint "eagle-import:C1206K")
      (libsource (lib "eagle-import") (part "C-EUC1206K"))
    )
    (comp (ref "C37")
      (value "100n")
      (footprint "eagle-import:C0603")
      (libsource (lib "eagle-import") (part "C-EUC0603"))
    )
    (comp (ref "C38")
      (value "47µF")
      (footprint "eagle-import:C1206K")
      (libsource (lib "eagle-import") (part "C-EUC1206K"))
    )
    (comp (ref "C39")
      (value "3.3nF")
      (footprint "eagle-import:C0603")
      (libsource (lib "eagle-import") (part "C-EUC0603"))
    )
    (comp (ref "C40")
      (value "56nF")
      (footprint "eagle-import:C0603")
      (libsource (lib "eagle-import") (part "C-EUC0603"))
    )
    (comp (ref "C41")
      (value "47µF")
      (footprint "eagle-import:153CLV-0605")
      (libsource (lib "eagle-import") (part "CPOL-EU153CLV-0605"))
    )
    (comp (ref "C42")
      (value "5.6nF")
      (footprint "eagle-import:C0603")
      (libsource (lib "eagle-import") (part "C-EUC0603"))
    )
    (comp (ref "C43")
      (value "47µF")
      (footprint "eagle-import:153CLV-0605")
      (libsource (lib "eagle-import") (part "CPOL-EU153CLV-0605"))
    )
    (comp (ref "C44")
      (value "5.6nF")
      (footprint "eagle-import:C0603")
      (libsource (lib "eagle-import") (part "C-EUC0603"))
    )
    (comp (ref "C45")
      (value "47µF")
      (footprint "eagle-import:153CLV-0605")
      (libsource (lib "eagle-import") (part "CPOL-EU153CLV-0605"))
    )
    (comp (ref "C46")
      (value "5.6nF")
      (footprint "eagle-import:C0603")
      (libsource (lib "eagle-import") (part "C-EUC0603"))
    )
    (comp (ref "C47")
      (value "47µF")
      (footprint "eagle-import:153CLV-0605")
      (libsource (lib "eagle-import") (part "CPOL-EU153CLV-0605"))
    )
    (comp (ref "C48")
      (value "5.6nF")
      (footprint "eagle-import:C0603")
      (libsource (lib "eagle-import") (part "C-EUC0603"))
    )
    (comp (ref "Q3")
      (value "ZX5T953")
      (footprint "eagle-import:SOT223")
      (libsource (lib "eagle-import") (part "FZT753SMD"))
    )
    (comp (ref "Q4")
      (value "12.288MHz")
      (footprint "eagle-import:CSM-7X-DU")
      (libsource (lib "eagle-import") (part "CSM-7X-DU"))
    )
    (comp (ref "R29")
      (value "1kΩ")
      (footprint "eagle-import:R0603")
      (libsource (lib "eagle-import") (part "R-EU_R0603"))
    )
    (comp (ref "R30")
      (value "10kΩ")
      (footprint "eagle-import:R0603")
      (libsource (lib "eagle-import") (part "R-EU_R0603"))
    )
    (comp (ref "R31")
      (value "18kΩ")
      (footprint "eagle-import:R0603")
      (libsource (lib "eagle-import") (part "R-EU_R0603"))
    )
    (comp (ref "R32")
      (value "18kΩ")
      (footprint "eagle-import:R0603")
      (libsource (lib "eagle-import") (part "R-EU_R0603"))
    )
    (comp (ref "R33")
      (value "18kΩ")
      (footprint "eagle-import:R0603")
      (libsource (lib "eagle-import") (part "R-EU_R0603"))
    )
    (comp (ref "R34")
      (value "100Ω")
      (footprint "eagle-import:R0603")
      (libsource (lib "eagle-import") (part "R-EU_R0603"))
    )
    (comp (ref "R35")
      (value "475Ω")
      (footprint "eagle-import:R0603")
      (libsource (lib "eagle-import") (part "R-EU_R0603"))
    )
    (comp (ref "R36")
      (value "560Ω")
      (footprint "eagle-import:R0603")
      (libsource (lib "eagle-import") (part "R-EU_R0603"))
    )
    (comp (ref "R37")
      (value "560Ω")
      (footprint "eagle-import:R0603")
      (libsource (lib "eagle-import") (part "R-EU_R0603"))
    )
    (comp (ref "R38")
      (value "560Ω")
      (footprint "eagle-import:R0603")
      (libsource (lib "eagle-import") (part "R-EU_R0603"))
    )
    (comp (ref "R39")
      (value "560Ω")
      (footprint "eagle-import:R0603")
      (libsource (lib "eagle-import") (part "R-EU_R0603"))
    )
    (comp (ref "R40")
      (value "0Ω")
      (footprint "eagle-import:R0603")
      (libsource (lib "eagle-import") (part "R-EU_R0603"))
    )
    (comp (ref "R41")
      (value "0Ω")
      (footprint "eagle-import:R0603")
      (libsource (lib "eagle-import") (part "R-EU_R0603"))
    )
    (comp (ref "R42")
      (value "0Ω")
      (footprint "eagle-import:R0603")
      (libsource (lib "eagle-import") (part "R-EU_R0603"))
    )
    (comp (ref "R43")
      (value "0Ω")
      (footprint "eagle-import:R0603")
      (libsource (lib "eagle-import") (part "R-EU_R0603"))
    )
    (comp (ref "SJ1")
      (value "SJ2W")
      (footprint "eagle-import:SJ_2")
      (libsource (lib "eagle-import") (part "SJ2W"))
    )
    (comp (ref "SJ2") (value "SJ") (footprint "eagle-import:SJ") (libsource (lib "eagle-import") (part "SJ")))
    (comp (ref "SJ6") (value "SJ") (footprint "eagle-import:SJ") (libsource (lib "eagle-import") (part "SJ")))
    (comp (ref "SJ7") (value "SJ") (footprint "eagle-import:SJ") (libsource (lib "eagle-import") (part "SJ")))
    (comp (ref "SJ8") (value "SJ") (footprint "eagle-import:SJ") (libsource (lib "eagle-import") (part "SJ")))
    (comp (ref "SJ9") (value "SJ") (footprint "eagle-import:SJ") (libsource (lib "eagle-import") (part "SJ")))
    (comp (ref "U3")
      (value "ADAU1701JSTZ")
      (footprint "eagle-import:ST_48_ADI")
      (libsource (lib "eagle-import") (part "ADAU1701JSTZ"))
    )
    (comp (ref "C1")
      (value "10µF")
      (footprint "eagle-import:153CLV-0605")
      (libsource (lib "eagle-import") (part "CPOL-EU153CLV-0605"))
    )
    (comp (ref "C2")
      (value "10µF")
      (footprint "eagle-import:153CLV-0605")
      (libsource (lib "eagle-import") (part "CPOL-EU153CLV-0605"))
    )
    (comp (ref "C3")
      (value "1.2nF")
      (footprint "eagle-import:C0603")
      (libsource (lib "eagle-import") (part "C-EUC0603"))
    )
    (comp (ref "C4")
      (value "6.8pF")
      (footprint "eagle-import:C0603")
      (libsource (lib "eagle-import") (part "C-EUC0603"))
    )
    (comp (ref "C5")
      (value "100nF")
      (footprint "eagle-import:C0603")
      (libsource (lib "eagle-import") (part "C-EUC0603"))
    )
    (comp (ref "C6")
      (value "47µF")
      (footprint "eagle-import:153CLV-0807")
      (libsource (lib "eagle-import") (part "CPOL-EU153CLV-0807"))
    )
    (comp (ref "C8")
      (value "10µF")
      (footprint "eagle-import:153CLV-0605")
      (libsource (lib "eagle-import") (part "CPOL-EU153CLV-0605"))
    )
    (comp (ref "C9")
      (value "1µF")
      (footprint "eagle-import:C3216")
      (libsource (lib "eagle-import") (part "C-EUC3216"))
    )
    (comp (ref "C10")
      (value "8.2nF")
      (footprint "eagle-import:C0603")
      (libsource (lib "eagle-import") (part "C-EUC0603"))
    )
    (comp (ref "C11")
      (value "100nF")
      (footprint "eagle-import:C0603")
      (libsource (lib "eagle-import") (part "C-EUC0603"))
    )
    (comp (ref "C12")
      (value "1µF")
      (footprint "eagle-import:C3216")
      (libsource (lib "eagle-import") (part "C-EUC3216"))
    )
    (comp (ref "C13")
      (value "8.2nF")
      (footprint "eagle-import:C0603")
      (libsource (lib "eagle-import") (part "C-EUC0603"))
    )
    (comp (ref "C14")
      (value "100nF")
      (footprint "eagle-import:C0603")
      (libsource (lib "eagle-import") (part "C-EUC0603"))
    )
    (comp (ref "C15")
      (value "100nF")
      (footprint "eagle-import:C0603")
      (libsource (lib "eagle-import") (part "C-EUC0603"))
    )
    (comp (ref "C16")
      (value "10pF")
      (footprint "eagle-import:C0603")
      (libsource (lib "eagle-import") (part "C-EUC0603"))
    )
    (comp (ref "C17")
      (value "10µF")
      (footprint "eagle-import:153CLV-0605")
      (libsource (lib "eagle-import") (part "CPOL-EU153CLV-0605"))
    )
    (comp (ref "C50")
      (value "100nF")
      (footprint "eagle-import:C0603")
      (libsource (lib "eagle-import") (part "C-EUC0603"))
    )
    (comp (ref "C51")
      (value "100nF")
      (footprint "eagle-import:C0603")
      (libsource (lib "eagle-import") (part "C-EUC0603"))
    )
    (comp (ref "C52")
      (value "10pF")
      (footprint "eagle-import:C0603")
      (libsource (lib "eagle-import") (part "C-EUC0603"))
    )
    (comp (ref "C53")
      (value "10µF")
      (footprint "eagle-import:153CLV-0605")
      (libsource (lib "eagle-import") (part "CPOL-EU153CLV-0605"))
    )
    (comp (ref "D1")
      (value "STPS20M100SG-TR")
      (footprint "eagle-import:TO-263_D2PAK")
      (libsource (lib "eagle-import") (part "STPS20M100SG-TR"))
    )
    (comp (ref "IC1")
      (value "UA741D")
      (footprint "eagle-import:SO08")
      (libsource (lib "eagle-import") (part "741DUA"))
    )
    (comp (ref "L1")
      (value "15µH")
      (footprint "eagle-import:INDUCTOR_SDR1307")
      (libsource (lib "eagle-import") (part "INDUCTOR-SDR13-27UH"))
    )
    (comp (ref "L2")
      (value "CLF7045T-3R3N")
      (footprint "eagle-import:L5650M")
      (libsource (lib "eagle-import") (part "L-USL5650M"))
    )
    (comp (ref "L3")
      (value "CLF7045T-3R3N")
      (footprint "eagle-import:L5650M")
      (libsource (lib "eagle-import") (part "L-USL5650M"))
    )
    (comp (ref "R1")
      (value "187kΩ")
      (footprint "eagle-import:R0603")
      (libsource (lib "eagle-import") (part "R-EU_R0603"))
    )
    (comp (ref "R2")
      (value "44.2kΩ")
      (footprint "eagle-import:R0603")
      (libsource (lib "eagle-import") (part "R-EU_R0603"))
    )
    (comp (ref "R3")
      (value "147kΩ")
      (footprint "eagle-import:R0603")
      (libsource (lib "eagle-import") (part "R-EU_R0603"))
    )
    (comp (ref "R4")
      (value "10.5kΩ")
      (footprint "eagle-import:R0603")
      (libsource (lib "eagle-import") (part "R-EU_R0603"))
    )
    (comp (ref "R5")
      (value "10kΩ")
      (footprint "eagle-import:R0603")
      (libsource (lib "eagle-import") (part "R-EU_R0603"))
    )
    (comp (ref "R6")
      (value "133kΩ")
      (footprint "eagle-import:R0603")
      (libsource (lib "eagle-import") (part "R-EU_R0603"))
    )
    (comp (ref "R7")
      (value "24kΩ")
      (footprint "eagle-import:R0603")
      (libsource (lib "eagle-import") (part "R-EU_R0603"))
    )
    (comp (ref "R8")
      (value "10kΩ")
      (footprint "eagle-import:R0603")
      (libsource (lib "eagle-import") (part "R-EU_R0603"))
    )
    (comp (ref "R9")
      (value "84.5kΩ")
      (footprint "eagle-import:R0603")
      (libsource (lib "eagle-import") (part "R-EU_R0603"))
    )
    (comp (ref "R10")
      (value "25.5kΩ")
      (footprint "eagle-import:R0603")
      (libsource (lib "eagle-import") (part "R-EU_R0603"))
    )
    (comp (ref "R11")
      (value "1MΩ")
      (footprint "eagle-import:R0603")
      (libsource (lib "eagle-import") (part "R-EU_R0603"))
    )
    (comp (ref "R12")
      (value "66.398kΩ")
      (footprint "eagle-import:R0603")
      (libsource (lib "eagle-import") (part "R-EU_R0603"))
    )
    (comp (ref "REG1")
      (value "TPS54560B-Q1")
      (footprint "eagle-import:HSOP8")
      (libsource (lib "eagle-import") (part "TPS54560B-Q1"))
    )
    (comp (ref "REG2")
      (value "TPS54339DDA")
      (footprint "eagle-import:DDA8_3P1X2P4_TEX")
      (libsource (lib "eagle-import") (part "TPS54339DDA"))
    )
    (comp (ref "REG3")
      (value "TPS54339DDA")
      (footprint "eagle-import:DDA8_3P1X2P4_TEX")
      (libsource (lib "eagle-import") (part "TPS54339DDA"))
    )
    (comp (ref "3V3IO")
      (value "SMD2")
      (footprint "eagle-import:SMD1,27-2,54")
      (libsource (lib "eagle-import") (part "SMD2"))
    )
    (comp (ref "C18")
      (value "100nF")
      (footprint "eagle-import:C0603")
      (libsource (lib "eagle-import") (part "C-EUC0603"))
    )
    (comp (ref "C19")
      (value "100nF")
      (footprint "eagle-import:C0603")
      (libsource (lib "eagle-import") (part "C-EUC0603"))
    )
    (comp (ref "C20")
      (value "100nF")
      (footprint "eagle-import:C0603")
      (libsource (lib "eagle-import") (part "C-EUC0603"))
    )
    (comp (ref "C49")
      (value "100nF")
      (footprint "eagle-import:C0603")
      (libsource (lib "eagle-import") (part "C-EUC0603"))
    )
    (comp (ref "IC6")
      (value "CP2102")
      (footprint "eagle-import:MLP28")
      (fields (field (name "MF") "FARNELL") (field (name "MPN") "CP2102-GM"))
      (libsource (lib "eagle-import") (part "CP2102"))
    )
    (comp (ref "IO1")
      (value "SMD2")
      (footprint "eagle-import:SMD1,27-2,54")
      (libsource (lib "eagle-import") (part "SMD2"))
    )
    (comp (ref "IO2")
      (value "SMD2")
      (footprint "eagle-import:SMD1,27-2,54")
      (libsource (lib "eagle-import") (part "SMD2"))
    )
    (comp (ref "IO3")
      (value "SMD2")
      (footprint "eagle-import:SMD1,27-2,54")
      (libsource (lib "eagle-import") (part "SMD2"))
    )
    (comp (ref "IO4")
      (value "SMD2")
      (footprint "eagle-import:SMD1,27-2,54")
      (libsource (lib "eagle-import") (part "SMD2"))
    )
    (comp (ref "IO5")
      (value "SMD2")
      (footprint "eagle-import:SMD1,27-2,54")
      (libsource (lib "eagle-import") (part "SMD2"))
    )
    (comp (ref "IO26")
      (value "SMD2")
      (footprint "eagle-import:SMD1,27-2,54")
      (libsource (lib "eagle-import") (part "SMD2"))
    )
    (comp (ref "IO27")
      (value "SMD2")
      (footprint "eagle-import:SMD1,27-2,54")
      (libsource (lib "eagle-import") (part "SMD2"))
    )
    (comp (ref "IO32")
      (value "SMD2")
      (footprint "eagle-import:SMD1,27-2,54")
      (libsource (lib "eagle-import") (part "SMD2"))
    )
    (comp (ref "IO33")
      (value "SMD2")
      (footprint "eagle-import:SMD1,27-2,54")
      (libsource (lib "eagle-import") (part "SMD2"))
    )
    (comp (ref "IO34")
      (value "SMD2")
      (footprint "eagle-import:SMD1,27-2,54")
      (libsource (lib "eagle-import") (part "SMD2"))
    )
    (comp (ref "J4")
      (value "455-1750-1-ND")
      (footprint "eagle-import:1X03")
      (libsource (lib "eagle-import") (part "CONN_03"))
    )
    (comp (ref "J5")
      (value "455-1750-1-ND")
      (footprint "eagle-import:1X03")
      (libsource (lib "eagle-import") (part "CONN_03"))
    )
    (comp (ref "Q1")
      (value "SS8050-G")
      (footprint "eagle-import:SOT23-BEC")
      (libsource (lib "eagle-import") (part "BC849SMD"))
    )
    (comp (ref "Q2")
      (value "SS8050-G")
      (footprint "eagle-import:SOT23-BEC")
      (libsource (lib "eagle-import") (part "BC849SMD"))
    )
    (comp (ref "R13")
      (value "10kΩ")
      (footprint "eagle-import:R0603")
      (libsource (lib "eagle-import") (part "R-EU_R0603"))
    )
    (comp (ref "R14")
      (value "4.7kΩ")
      (footprint "eagle-import:R0603")
      (libsource (lib "eagle-import") (part "R-EU_R0603"))
    )
    (comp (ref "R15")
      (value "4.7kΩ")
      (footprint "eagle-import:R0603")
      (libsource (lib "eagle-import") (part "R-EU_R0603"))
    )
    (comp (ref "R16")
      (value "10kΩ")
      (footprint "eagle-import:R0603")
      (libsource (lib "eagle-import") (part "R-EU_R0603"))
    )
    (comp (ref "R17")
      (value "10kΩ")
      (footprint "eagle-import:R0603")
      (libsource (lib "eagle-import") (part "R-EU_R0603"))
    )
    (comp (ref "R18")
      (value "5.1kΩ")
      (footprint "eagle-import:R0603")
      (libsource (lib "eagle-import") (part "R-EU_R0603"))
    )
    (comp (ref "R19")
      (value "5.1kΩ")
      (footprint "eagle-import:R0603")
      (libsource (lib "eagle-import") (part "R-EU_R0603"))
    )
    (comp (ref "R20")
      (value "22.1kΩ")
      (footprint "eagle-import:R0603")
      (libsource (lib "eagle-import") (part "R-EU_R0603"))
    )
    (comp (ref "R21")
      (value "47.5kΩ")
      (footprint "eagle-import:R0603")
      (libsource (lib "eagle-import") (part "R-EU_R0603"))
    )
    (comp (ref "R22")
      (value "2kΩ")
      (footprint "eagle-import:R0603")
      (libsource (lib "eagle-import") (part "R-EU_R0603"))
    )
    (comp (ref "R44")
      (value "0kΩ")
      (footprint "eagle-import:R0603")
      (libsource (lib "eagle-import") (part "R-EU_R0603"))
    )
    (comp (ref "R45")
      (value "47kΩ")
      (footprint "eagle-import:R0603")
      (libsource (lib "eagle-import") (part "R-EU_R0603"))
    )
    (comp (ref "R46")
      (value "47kΩ")
      (footprint "eagle-import:R0603")
      (libsource (lib "eagle-import") (part "R-EU_R0603"))
    )
    (comp (ref "R47")
      (value "47kΩ")
      (footprint "eagle-import:R0603")
      (libsource (lib "eagle-import") (part "R-EU_R0603"))
    )
    (comp (ref "R48")
      (value "47kΩ")
      (footprint "eagle-import:R0603")
      (libsource (lib "eagle-import") (part "R-EU_R0603"))
    )
    (comp (ref "R49")
      (value "47kΩ")
      (footprint "eagle-import:R0603")
      (libsource (lib "eagle-import") (part "R-EU_R0603"))
    )
    (comp (ref "S1")
      (value "MOMENTARY-SWITCH-SPST-SMD-6.2MM-TALL")
      (footprint "eagle-import:TACTILE_SWITCH_SMD_6.2MM_TALL")
      (libsource (lib "eagle-import") (part "MOMENTARY-SWITCH-SPST-SMD-6.2MM-TALL"))
    )
    (comp (ref "S2")
      (value "MOMENTARY-SWITCH-SPST-SMD-6.2MM-TALL")
      (footprint "eagle-import:TACTILE_SWITCH_SMD_6.2MM_TALL")
      (libsource (lib "eagle-import") (part "MOMENTARY-SWITCH-SPST-SMD-6.2MM-TALL"))
    )
    (comp (ref "U1")
      (value "ESP-WROOM-32")
      (footprint "eagle-import:ESP-WROOM-32")
      (libsource (lib "eagle-import") (part "ESP-WROOM-32"))
    )
    (comp (ref "VD1")
      (value "USBLC6-2SC6")
      (footprint "eagle-import:SOT-23-6L")
      (libsource (lib "eagle-import") (part "USBLC6-2SC6"))
    )
    (comp (ref "C85")
      (value "1µF")
      (footprint "eagle-import:C150-091X182")
      (libsource (lib "eagle-import") (part "C-EU150-091X182"))
    )
    (comp (ref "C86")
      (value "1µF")
      (footprint "eagle-import:C150-091X182")
      (libsource (lib "eagle-import") (part "C-EU150-091X182"))
    )
    (comp (ref "C87")
      (value "1µF")
      (footprint "eagle-import:C150-091X182")
      (libsource (lib "eagle-import") (part "C-EU150-091X182"))
    )
    (comp (ref "C88")
      (value "1µF")
      (footprint "eagle-import:C150-091X182")
      (libsource (lib "eagle-import") (part "C-EU150-091X182"))
    )
    (comp (ref "C89")
      (value "1000pF")
      (footprint "eagle-import:C0805")
      (libsource (lib "eagle-import") (part "C-EUC0805"))
    )
    (comp (ref "C90")
      (value "1000pF")
      (footprint "eagle-import:C0805")
      (libsource (lib "eagle-import") (part "C-EUC0805"))
    )
    (comp (ref "C91")
      (value "100nF")
      (footprint "eagle-import:C0805")
      (libsource (lib "eagle-import") (part "C-EUC0805"))
    )
    (comp (ref "C92")
      (value "100nF")
      (footprint "eagle-import:C0805")
      (libsource (lib "eagle-import") (part "C-EUC0805"))
    )
    (comp (ref "C93")
      (value "1000pF")
      (footprint "eagle-import:C0805")
      (libsource (lib "eagle-import") (part "C-EUC0805"))
    )
    (comp (ref "C94")
      (value "1000pF")
      (footprint "eagle-import:C0805")
      (libsource (lib "eagle-import") (part "C-EUC0805"))
    )
    (comp (ref "C95")
      (value "33nF")
      (footprint "eagle-import:C0603")
      (libsource (lib "eagle-import") (part "C-EUC0603"))
    )
    (comp (ref "C96")
      (value "33nF")
      (footprint "eagle-import:C0603")
      (libsource (lib "eagle-import") (part "C-EUC0603"))
    )
    (comp (ref "C97")
      (value "1µF")
      (footprint "eagle-import:C150-091X182")
      (libsource (lib "eagle-import") (part "C-EU150-091X182"))
    )
    (comp (ref "C98")
      (value "1µF")
      (footprint "eagle-import:C150-091X182")
      (libsource (lib "eagle-import") (part "C-EU150-091X182"))
    )
    (comp (ref "C99")
      (value "1000pF")
      (footprint "eagle-import:C0805")
      (libsource (lib "eagle-import") (part "C-EUC0805"))
    )
    (comp (ref "C100")
      (value "1000pF")
      (footprint "eagle-import:C0805")
      (libsource (lib "eagle-import") (part "C-EUC0805"))
    )
    (comp (ref "C101")
      (value "100nF")
      (footprint "eagle-import:C0805")
      (libsource (lib "eagle-import") (part "C-EUC0805"))
    )
    (comp (ref "C102")
      (value "100nF")
      (footprint "eagle-import:C0805")
      (libsource (lib "eagle-import") (part "C-EUC0805"))
    )
    (comp (ref "C103")
      (value "100nF")
      (footprint "eagle-import:C0805")
      (libsource (lib "eagle-import") (part "C-EUC0805"))
    )
    (comp (ref "C104")
      (value "100nF")
      (footprint "eagle-import:C0805")
      (libsource (lib "eagle-import") (part "C-EUC0805"))
    )
    (comp (ref "C105")
      (value "33nF")
      (footprint "eagle-import:C0603")
      (libsource (lib "eagle-import") (part "C-EUC0603"))
    )
    (comp (ref "C106")
      (value "33nF")
      (footprint "eagle-import:C0603")
      (libsource (lib "eagle-import") (part "C-EUC0603"))
    )
    (comp (ref "C107")
      (value "1µF")
      (footprint "eagle-import:C150-091X182")
      (libsource (lib "eagle-import") (part "C-EU150-091X182"))
    )
    (comp (ref "C108")
      (value "1µF")
      (footprint "eagle-import:C150-091X182")
      (libsource (lib "eagle-import") (part "C-EU150-091X182"))
    )
    (comp (ref "C109")
      (value "33nF")
      (footprint "eagle-import:C0603")
      (libsource (lib "eagle-import") (part "C-EUC0603"))
    )
    (comp (ref "C110")
      (value "33nF")
      (footprint "eagle-import:C0603")
      (libsource (lib "eagle-import") (part "C-EUC0603"))
    )
    (comp (ref "C111")
      (value "1000pF")
      (footprint "eagle-import:C0805")
      (libsource (lib "eagle-import") (part "C-EUC0805"))
    )
    (comp (ref "C112")
      (value "1000pF")
      (footprint "eagle-import:C0805")
      (libsource (lib "eagle-import") (part "C-EUC0805"))
    )
    (comp (ref "C113")
      (value "100nF")
      (footprint "eagle-import:C0805")
      (libsource (lib "eagle-import") (part "C-EUC0805"))
    )
    (comp (ref "C114")
      (value "100nF")
      (footprint "eagle-import:C0805")
      (libsource (lib "eagle-import") (part "C-EUC0805"))
    )
    (comp (ref "C115")
      (value "33nF")
      (footprint "eagle-import:C0603")
      (libsource (lib "eagle-import") (part "C-EUC0603"))
    )
    (comp (ref "C116")
      (value "33nF")
      (footprint "eagle-import:C0603")
      (libsource (lib "eagle-import") (part "C-EUC0603"))
    )
    (comp (ref "L6")
      (value "HTCI-10-20.0")
      (footprint "eagle-import:HCTI-10-20.0")
      (libsource (lib "eagle-import") (part "HTCI-10-20.0"))
    )
    (comp (ref "L7")
      (value "HTCI-10-20.0")
      (footprint "eagle-import:HCTI-10-20.0")
      (libsource (lib "eagle-import") (part "HTCI-10-20.0"))
    )
    (comp (ref "L8")
      (value "HTCI-10-20.0")
      (footprint "eagle-import:HCTI-10-20.0")
      (libsource (lib "eagle-import") (part "HTCI-10-20.0"))
    )
    (comp (ref "L9")
      (value "HTCI-10-20.0")
      (footprint "eagle-import:HCTI-10-20.0")
      (libsource (lib "eagle-import") (part "HTCI-10-20.0"))
    )
    (comp (ref "L10")
      (value "HTCI-10-20.0")
      (footprint "eagle-import:HCTI-10-20.0")
      (libsource (lib "eagle-import") (part "HTCI-10-20.0"))
    )
    (comp (ref "L11")
      (value "HTCI-10-20.0")
      (footprint "eagle-import:HCTI-10-20.0")
      (libsource (lib "eagle-import") (part "HTCI-10-20.0"))
    )
    (comp (ref "L12")
      (value "HTCI-10-20.0")
      (footprint "eagle-import:HCTI-10-20.0")
      (libsource (lib "eagle-import") (part "HTCI-10-20.0"))
    )
    (comp (ref "L13")
      (value "HTCI-10-20.0")
      (footprint "eagle-import:HCTI-10-20.0")
      (libsource (lib "eagle-import") (part "HTCI-10-20.0"))
    )
    (comp (ref "R71")
      (value "3.3Ω")
      (footprint "eagle-import:R0603")
      (libsource (lib "eagle-import") (part "R-EU_R0603"))
    )
    (comp (ref "R72")
      (value "3.3Ω")
      (footprint "eagle-import:R0603")
      (libsource (lib "eagle-import") (part "R-EU_R0603"))
    )
    (comp (ref "R73")
      (value "3.3Ω")
      (footprint "eagle-import:R0603")
      (libsource (lib "eagle-import") (part "R-EU_R0603"))
    )
    (comp (ref "R74")
      (value "3.3Ω")
      (footprint "eagle-import:R0603")
      (libsource (lib "eagle-import") (part "R-EU_R0603"))
    )
    (comp (ref "R75")
      (value "3.3Ω")
      (footprint "eagle-import:R0603")
      (libsource (lib "eagle-import") (part "R-EU_R0603"))
    )
    (comp (ref "R76")
      (value "3.3Ω")
      (footprint "eagle-import:R0603")
      (libsource (lib "eagle-import") (part "R-EU_R0603"))
    )
    (comp (ref "R77")
      (value "3.3Ω")
      (footprint "eagle-import:R0603")
      (libsource (lib "eagle-import") (part "R-EU_R0603"))
    )
    (comp (ref "R78")
      (value "3.3Ω")
      (footprint "eagle-import:R0603")
      (libsource (lib "eagle-import") (part "R-EU_R0603"))
    )
    (comp (ref "AUX_IN_1")
      (value "SJ1-3523N")
      (footprint "eagle-import:CUI_SJ1-3523N")
      (fields (field (name "MANUFACTURER") "CUI"))
      (libsource (lib "eagle-import") (part "SJ1-3523N"))
    )
    (comp (ref "AUX_OUT_1")
      (value "MA03-1")
      (footprint "eagle-import:MA03-1")
      (libsource (lib "eagle-import") (part "MA03-1"))
    )
    (comp (ref "AUX_OUT_2")
      (value "MA03-1")
      (footprint "eagle-import:MA03-1")
      (libsource (lib "eagle-import") (part "MA03-1"))
    )
    (comp (ref "CHAIN_INPUT")
      (value "MA06-1")
      (footprint "eagle-import:MA06-1")
      (libsource (lib "eagle-import") (part "MA06-1"))
    )
    (comp (ref "CHAIN_OUTPUT")
      (value "MA06-1")
      (footprint "eagle-import:MA06-1")
      (libsource (lib "eagle-import") (part "MA06-1"))
    )
    (comp (ref "J1")
      (value "614004134726")
      (footprint "eagle-import:614004134726")
      (libsource (lib "eagle-import") (part "614004134726"))
    )
    (comp (ref "J2")
      (value "614004134726")
      (footprint "eagle-import:614004134726")
      (libsource (lib "eagle-import") (part "614004134726"))
    )
    (comp (ref "J3")
      (value "DX07S016JA1R1500")
      (footprint "eagle-import:JAE_DX07S016JA1R1500")
      (fields (field (name "MF") "JAE Electronics"))
      (libsource (lib "eagle-import") (part "DX07S016JA1R1500"))
    )
    (comp (ref "J6")
      (value "CONN_02PTH3")
      (footprint "eagle-import:1X02_LONGPADS")
      (libsource (lib "eagle-import") (part "CONN_02PTH3"))
    )
    (comp (ref "J7")
      (value "1140084168")
      (footprint "eagle-import:AMPHENOL_1140084168")
      (fields (field (name "MF") "Amphenol Commercial Products"))
      (libsource (lib "eagle-import") (part "1140084168"))
    )
    (comp (ref "LED_SYS")
      (value "LEDSML0603")
      (footprint "eagle-import:SML0603")
      (libsource (lib "eagle-import") (part "LEDSML0603"))
    )
    (comp (ref "PAD1")
      (value "SMD2")
      (footprint "eagle-import:SMD1,27-2,54")
      (libsource (lib "eagle-import") (part "SMD2"))
    )
    (comp (ref "PAD2")
      (value "SMD2")
      (footprint "eagle-import:SMD1,27-2,54")
      (libsource (lib "eagle-import") (part "SMD2"))
    )
    (comp (ref "PAD3")
      (value "SMD2")
      (footprint "eagle-import:SMD1,27-2,54")
      (libsource (lib "eagle-import") (part "SMD2"))
    )
    (comp (ref "PAD4")
      (value "SMD2")
      (footprint "eagle-import:SMD1,27-2,54")
      (libsource (lib "eagle-import") (part "SMD2"))
    )
    (comp (ref "PAD5")
      (value "SMD2")
      (footprint "eagle-import:SMD1,27-2,54")
      (libsource (lib "eagle-import") (part "SMD2"))
    )
    (comp (ref "PAD6")
      (value "SMD2")
      (footprint "eagle-import:SMD1,27-2,54")
      (libsource (lib "eagle-import") (part "SMD2"))
    )
    (comp (ref "PAD7")
      (value "SMD2")
      (footprint "eagle-import:SMD1,27-2,54")
      (libsource (lib "eagle-import") (part "SMD2"))
    )
    (comp (ref "PAD8")
      (value "SMD2")
      (footprint "eagle-import:SMD1,27-2,54")
      (libsource (lib "eagle-import") (part "SMD2"))
    )
    (comp (ref "POT0")
      (value "TRIM_EU-CIP20C-6MM")
      (footprint "eagle-import:CIP20C-6MM")
      (libsource (lib "eagle-import") (part "TRIM_EU-CIP20C-6MM"))
    )
    (comp (ref "POT1")
      (value "TRIM_EU-CIP20C-6MM")
      (footprint "eagle-import:CIP20C-6MM")
      (libsource (lib "eagle-import") (part "TRIM_EU-CIP20C-6MM"))
    )
    (comp (ref "POT2")
      (value "TRIM_EU-CIP20C-6MM")
      (footprint "eagle-import:CIP20C-6MM")
      (libsource (lib "eagle-import") (part "TRIM_EU-CIP20C-6MM"))
    )
    (comp (ref "POT3")
      (value "TRIM_EU-CIP20C-6MM")
      (footprint "eagle-import:CIP20C-6MM")
      (libsource (lib "eagle-import") (part "TRIM_EU-CIP20C-6MM"))
    )
    (comp (ref "R28")
      (value "47Ω")
      (footprint "eagle-import:R0603")
      (libsource (lib "eagle-import") (part "R-EU_R0603"))
    )
    (comp (ref "U$1")
      (value "XT60")
      (footprint "eagle-import:XT60")
      (libsource (lib "eagle-import") (part "XT60"))
    )
    (comp (ref "X1")
      (value "MKDSN1,5/2-5,08")
      (footprint "eagle-import:MKDSN1,5_2-5,08")
      (libsource (lib "eagle-import") (part "MKDSN1,5/2-5,08"))
    )
    (comp (ref "X2")
      (value "MKDSN1,5/2-5,08")
      (footprint "eagle-import:MKDSN1,5_2-5,08")
      (libsource (lib "eagle-import") (part "MKDSN1,5/2-5,08"))
    )
  )
  (nets
    (net (code "1") (name "+3V3") (class "Default")
      (node (ref "3V3IO") (pin "1") (pinfunction "P_1") (pintype "passive"))
      (node (ref "C16") (pin "1") (pinfunction "1_1") (pintype "passive"))
      (node (ref "C17") (pin "+") (pinfunction "+_+") (pintype "passive"))
      (node (ref "C18") (pin "1") (pinfunction "1_1") (pintype "passive"))
      (node (ref "C19") (pin "1") (pinfunction "1_1") (pintype "passive"))
      (node (ref "C20") (pin "1") (pinfunction "1_1") (pintype "passive"))
      (node (ref "C24") (pin "1") (pinfunction "1_1") (pintype "passive"))
      (node (ref "C25") (pin "1") (pinfunction "1_1") (pintype "passive"))
      (node (ref "C26") (pin "1") (pinfunction "1_1") (pintype "passive"))
      (node (ref "C27") (pin "1") (pinfunction "1_1") (pintype "passive"))
      (node (ref "C29") (pin "1") (pinfunction "1_1") (pintype "passive"))
      (node (ref "C30") (pin "1") (pinfunction "1_1") (pintype "passive"))
      (node (ref "C39") (pin "2") (pinfunction "2_2") (pintype "passive"))
      (node (ref "C49") (pin "1") (pinfunction "1_1") (pintype "passive"))
      (node (ref "C50") (pin "1") (pinfunction "1_1") (pintype "passive"))
      (node (ref "IC1") (pin "7") (pinfunction "V+_7") (pintype "power_in"))
      (node (ref "IC6") (pin "6") (pinfunction "VDD_6") (pintype "power_in"))
      (node (ref "IC6") (pin "7") (pinfunction "REGIN_7") (pintype "passive"))
      (node (ref "IO2") (pin "1") (pinfunction "P_1") (pintype "passive"))
      (node (ref "IO3") (pin "1") (pinfunction "P_1") (pintype "passive"))
      (node (ref "J7") (pin "4") (pinfunction "SUPPLY_VOLTAGE_4") (pintype "power_in"))
      (node (ref "L3") (pin "2") (pinfunction "2_2") (pintype "passive"))
      (node (ref "POT0") (pin "E") (pinfunction "E_E") (pintype "passive"))
      (node (ref "POT1") (pin "E") (pinfunction "E_E") (pintype "passive"))
      (node (ref "POT2") (pin "E") (pinfunction "E_E") (pintype "passive"))
      (node (ref "POT3") (pin "E") (pinfunction "E_E") (pintype "passive"))
      (node (ref "Q3") (pin "3") (pinfunction "E_3") (pintype "passive"))
      (node (ref "R13") (pin "2") (pinfunction "2_2") (pintype "passive"))
      (node (ref "R14") (pin "1") (pinfunction "1_1") (pintype "passive"))
      (node (ref "R15") (pin "1") (pinfunction "1_1") (pintype "passive"))
      (node (ref "R22") (pin "1") (pinfunction "1_1") (pintype "passive"))
      (node (ref "R29") (pin "2") (pinfunction "2_2") (pintype "passive"))
      (node (ref "R30") (pin "2") (pinfunction "2_2") (pintype "passive"))
      (node (ref "R35") (pin "1") (pinfunction "1_1") (pintype "passive"))
      (node (ref "R45") (pin "1") (pinfunction "1_1") (pintype "passive"))
      (node (ref "R46") (pin "1") (pinfunction "1_1") (pintype "passive"))
      (node (ref "R47") (pin "1") (pinfunction "1_1") (pintype "passive"))
      (node (ref "R48") (pin "1") (pinfunction "1_1") (pintype "passive"))
      (node (ref "R49") (pin "1") (pinfunction "1_1") (pintype "passive"))
      (node (ref "R52") (pin "1") (pinfunction "1_1") (pintype "passive"))
      (node (ref "R81") (pin "1") (pinfunction "1_1") (pintype "passive"))
      (node (ref "R9") (pin "2") (pinfunction "2_2") (pintype "passive"))
      (node (ref "SJ1") (pin "3") (pinfunction "3_3") (pintype "passive"))
      (node (ref "U1") (pin "2") (pinfunction "3V3_2") (pintype "power_in"))
      (node (ref "U3") (pin "18") (pinfunction "IOVDD_18") (pintype "power_in"))
      (node (ref "U3") (pin "34") (pinfunction "PVDD_34") (pintype "power_in"))
      (node (ref "U3") (pin "36") (pinfunction "AVDD_2_36") (pintype "power_in"))
      (node (ref "U3") (pin "39") (pinfunction "PLL_MODE1_39") (pintype "input"))
      (node (ref "U3") (pin "48") (pinfunction "AVDD_48") (pintype "power_in"))
    )
    (net (code "2") (name "+5V") (class "Default")
      (node (ref "C52") (pin "1") (pinfunction "1_1") (pintype "passive"))
      (node (ref "C53") (pin "+") (pinfunction "+_+") (pintype "passive"))
      (node (ref "J1") (pin "1") (pinfunction "VBUS_1") (pintype "bidirectional"))
      (node (ref "J2") (pin "1") (pinfunction "VBUS_1") (pintype "bidirectional"))
      (node (ref "L2") (pin "2") (pinfunction "2_2") (pintype "passive"))
      (node (ref "R6") (pin "2") (pinfunction "2_2") (pintype "passive"))
      (node (ref "X2") (pin "1") (pinfunction "KL_1") (pintype "passive"))
    )
    (net (code "3") (name "+12V") (class "Default")
      (node (ref "C1") (pin "+") (pinfunction "+_+") (pintype "passive"))
      (node (ref "C15") (pin "1") (pinfunction "1_1") (pintype "passive"))
      (node (ref "C51") (pin "1") (pinfunction "1_1") (pintype "passive"))
      (node (ref "C6") (pin "+") (pinfunction "+_+") (pintype "passive"))
      (node (ref "C8") (pin "+") (pinfunction "+_+") (pintype "passive"))
      (node (ref "J6") (pin "2") (pinfunction "2_2") (pintype "passive"))
      (node (ref "L1") (pin "P$2") (pinfunction "2_P$2") (pintype "passive"))
      (node (ref "L14") (pin "1") (pinfunction "1_1") (pintype "passive"))
      (node (ref "L15") (pin "1") (pinfunction "1_1") (pintype "passive"))
      (node (ref "L4") (pin "1") (pinfunction "1_1") (pintype "passive"))
      (node (ref "L5") (pin "1") (pinfunction "1_1") (pintype "passive"))
      (node (ref "R3") (pin "2") (pinfunction "2_2") (pintype "passive"))
      (node (ref "R5") (pin "1") (pinfunction "1_1") (pintype "passive"))
      (node (ref "R53") (pin "1") (pinfunction "1_1") (pintype "passive"))
      (node (ref "R54") (pin "1") (pinfunction "1_1") (pintype "passive"))
      (node (ref "R8") (pin "1") (pinfunction "1_1") (pintype "passive"))
      (node (ref "R82") (pin "1") (pinfunction "1_1") (pintype "passive"))
      (node (ref "R83") (pin "1") (pinfunction "1_1") (pintype "passive"))
      (node (ref "REG2") (pin "2") (pinfunction "VIN_2") (pintype "input"))
      (node (ref "REG3") (pin "2") (pinfunction "VIN_2") (pintype "input"))
      (node (ref "X1") (pin "1") (pinfunction "KL_1") (pintype "passive"))
    )
    (net (code "4") (name "+12VOA") (class "Default")
      (node (ref "C66") (pin "1") (pinfunction "1_1") (pintype "passive"))
      (node (ref "C67") (pin "1") (pinfunction "1_1") (pintype "passive"))
      (node (ref "C68") (pin "1") (pinfunction "1_1") (pintype "passive"))
      (node (ref "C69") (pin "1") (pinfunction "1_1") (pintype "passive"))
      (node (ref "C70") (pin "1") (pinfunction "1_1") (pintype "passive"))
      (node (ref "IC2") (pin "8") (pinfunction "V+_8") (pintype "power_in"))
      (node (ref "IC3") (pin "8") (pinfunction "V+_8") (pintype "power_in"))
      (node (ref "L5") (pin "2") (pinfunction "2_2") (pintype "passive"))
      (node (ref "R69") (pin "1") (pinfunction "1_1") (pintype "passive"))
    )
    (net (code "5") (name "+12VOA1") (class "Default")
      (node (ref "C130") (pin "1") (pinfunction "1_1") (pintype "passive"))
      (node (ref "C131") (pin "1") (pinfunction "1_1") (pintype "passive"))
      (node (ref "C132") (pin "1") (pinfunction "1_1") (pintype "passive"))
      (node (ref "C133") (pin "1") (pinfunction "1_1") (pintype "passive"))
      (node (ref "C134") (pin "1") (pinfunction "1_1") (pintype "passive"))
      (node (ref "IC4") (pin "8") (pinfunction "V+_8") (pintype "power_in"))
      (node (ref "IC5") (pin "8") (pinfunction "V+_8") (pintype "power_in"))
      (node (ref "L15") (pin "2") (pinfunction "2_2") (pintype "passive"))
      (node (ref "R98") (pin "1") (pinfunction "1_1") (pintype "passive"))
    )
    (net (code "6") (name "AMP1_BST_A") (class "Default")
      (node (ref "AMP1") (pin "P$44") (pinfunction "BST_A_P$44") (pintype "bidirectional"))
      (node (ref "C109") (pin "1") (pinfunction "1_1") (pintype "passive"))
    )
    (net (code "7") (name "AMP1_BST_B") (class "Default")
      (node (ref "AMP1") (pin "P$43") (pinfunction "BST_B_P$43") (pintype "bidirectional"))
      (node (ref "C110") (pin "1") (pinfunction "1_1") (pintype "passive"))
    )
    (net (code "8") (name "AMP1_BST_C") (class "Default")
      (node (ref "AMP1") (pin "P$24") (pinfunction "BST_C_P$24") (pintype "bidirectional"))
      (node (ref "C95") (pin "1") (pinfunction "1_1") (pintype "passive"))
    )
    (net (code "9") (name "AMP1_BST_D") (class "Default")
      (node (ref "AMP1") (pin "P$23") (pinfunction "BST_D_P$23") (pintype "bidirectional"))
      (node (ref "C96") (pin "1") (pinfunction "1_1") (pintype "passive"))
    )
    (net (code "10") (name "AMP1_CLIP_OTW") (class "Default")
      (node (ref "AMP1") (pin "P$21") (pinfunction "~{CLIP_OTW}_P$21") (pintype "bidirectional"))
      (node (ref "U1") (pin "29") (pinfunction "IO5_29") (pintype "bidirectional"))
    )
    (net (code "11") (name "AMP1_FAULT") (class "Default")
      (node (ref "AMP1") (pin "P$19") (pinfunction "~{FAULT}_P$19") (pintype "bidirectional"))
      (node (ref "U1") (pin "30") (pinfunction "IO18_30") (pintype "bidirectional"))
    )
    (net (code "12") (name "AMP1_IN_A") (class "Default")
      (node (ref "AMP1") (pin "P$5") (pinfunction "INPUT_A_P$5") (pintype "bidirectional"))
      (node (ref "C76") (pin "2") (pinfunction "2_2") (pintype "passive"))
      (node (ref "R61") (pin "2") (pinfunction "2_2") (pintype "passive"))
    )
    (net (code "13") (name "AMP1_IN_B") (class "Default")
      (node (ref "AMP1") (pin "P$6") (pinfunction "INPUT_B_P$6") (pintype "bidirectional"))
      (node (ref "C75") (pin "2") (pinfunction "2_2") (pintype "passive"))
      (node (ref "R60") (pin "2") (pinfunction "2_2") (pintype "passive"))
    )
    (net (code "14") (name "AMP1_IN_C") (class "Default")
      (node (ref "AMP1") (pin "P$16") (pinfunction "INPUT_C_P$16") (pintype "bidirectional"))
      (node (ref "C82") (pin "2") (pinfunction "2_2") (pintype "passive"))
      (node (ref "R68") (pin "2") (pinfunction "2_2") (pintype "passive"))
    )
    (net (code "15") (name "AMP1_IN_D") (class "Default")
      (node (ref "AMP1") (pin "P$17") (pinfunction "INPUT_D_P$17") (pintype "bidirectional"))
      (node (ref "C81") (pin "2") (pinfunction "2_2") (pintype "passive"))
      (node (ref "R67") (pin "2") (pinfunction "2_2") (pintype "passive"))
    )
    (net (code "16") (name "AMP1_PWM_A") (class "Default")
      (node (ref "AMP1") (pin "P$39") (pinfunction "OUT_A_P$39") (pintype "bidirectional"))
      (node (ref "AMP1") (pin "P$40") (pinfunction "OUT_A_P$40") (pintype "bidirectional"))
      (node (ref "C109") (pin "2") (pinfunction "2_2") (pintype "passive"))
      (node (ref "L6") (pin "P$1") (pinfunction "1_P$1") (pintype "passive"))
    )
    (net (code "17") (name "AMP1_PWM_B") (class "Default")
      (node (ref "AMP1") (pin "P$35") (pinfunction "OUT_B_P$35") (pintype "bidirectional"))
      (node (ref "C110") (pin "2") (pinfunction "2_2") (pintype "passive"))
      (node (ref "L7") (pin "P$1") (pinfunction "1_P$1") (pintype "passive"))
    )
    (net (code "18") (name "AMP1_PWM_C") (class "Default")
      (node (ref "AMP1") (pin "P$32") (pinfunction "OUT_C_P$32") (pintype "bidirectional"))
      (node (ref "C95") (pin "2") (pinfunction "2_2") (pintype "passive"))
      (node (ref "L8") (pin "P$1") (pinfunction "1_P$1") (pintype "passive"))
    )
    (net (code "19") (name "AMP1_PWM_D") (class "Default")
      (node (ref "AMP1") (pin "P$27") (pinfunction "OUT_D_P$27") (pintype "bidirectional"))
      (node (ref "AMP1") (pin "P$28") (pinfunction "OUT_D_P$28") (pintype "bidirectional"))
      (node (ref "C96") (pin "2") (pinfunction "2_2") (pintype "passive"))
      (node (ref "L9") (pin "P$1") (pinfunction "1_P$1") (pintype "passive"))
    )
    (net (code "20") (name "AMP2_BST_A") (class "Default")
      (node (ref "AMP2") (pin "P$44") (pinfunction "BST_A_P$44") (pintype "bidirectional"))
      (node (ref "C105") (pin "1") (pinfunction "1_1") (pintype "passive"))
    )
    (net (code "21") (name "AMP2_BST_B") (class "Default")
      (node (ref "AMP2") (pin "P$43") (pinfunction "BST_B_P$43") (pintype "bidirectional"))
      (node (ref "C106") (pin "1") (pinfunction "1_1") (pintype "passive"))
    )
    (net (code "22") (name "AMP2_BST_C") (class "Default")
      (node (ref "AMP2") (pin "P$24") (pinfunction "BST_C_P$24") (pintype "bidirectional"))
      (node (ref "C115") (pin "1") (pinfunction "1_1") (pintype "passive"))
    )
    (net (code "23") (name "AMP2_BST_D") (class "Default")
      (node (ref "AMP2") (pin "P$23") (pinfunction "BST_D_P$23") (pintype "bidirectional"))
      (node (ref "C116") (pin "1") (pinfunction "1_1") (pintype "passive"))
    )
    (net (code "24") (name "AMP2_CLIP_OTW") (class "Default")
      (node (ref "AMP2") (pin "P$21") (pinfunction "~{CLIP_OTW}_P$21") (pintype "bidirectional"))
      (node (ref "U1") (pin "31") (pinfunction "IO19_31") (pintype "bidirectional"))
    )
    (net (code "25") (name "AMP2_FAULT") (class "Default")
      (node (ref "AMP2") (pin "P$19") (pinfunction "~{FAULT}_P$19") (pintype "bidirectional"))
      (node (ref "U1") (pin "37") (pinfunction "IO23_37") (pintype "bidirectional"))
    )
    (net (code "26") (name "AMP2_IN_A") (class "Default")
      (node (ref "AMP2") (pin "P$5") (pinfunction "INPUT_A_P$5") (pintype "bidirectional"))
      (node (ref "C140") (pin "2") (pinfunction "2_2") (pintype "passive"))
      (node (ref "R90") (pin "2") (pinfunction "2_2") (pintype "passive"))
    )
    (net (code "27") (name "AMP2_IN_B") (class "Default")
      (node (ref "AMP2") (pin "P$6") (pinfunction "INPUT_B_P$6") (pintype "bidirectional"))
      (node (ref "C139") (pin "2") (pinfunction "2_2") (pintype "passive"))
      (node (ref "R89") (pin "2") (pinfunction "2_2") (pintype "passive"))
    )
    (net (code "28") (name "AMP2_IN_C") (class "Default")
      (node (ref "AMP2") (pin "P$16") (pinfunction "INPUT_C_P$16") (pintype "bidirectional"))
      (node (ref "C146") (pin "2") (pinfunction "2_2") (pintype "passive"))
      (node (ref "R97") (pin "2") (pinfunction "2_2") (pintype "passive"))
    )
    (net (code "29") (name "AMP2_IN_D") (class "Default")
      (node (ref "AMP2") (pin "P$17") (pinfunction "INPUT_D_P$17") (pintype "bidirectional"))
      (node (ref "C145") (pin "2") (pinfunction "2_2") (pintype "passive"))
      (node (ref "R96") (pin "2") (pinfunction "2_2") (pintype "passive"))
    )
    (net (code "30") (name "AMP2_PWM_A") (class "Default")
      (node (ref "AMP2") (pin "P$39") (pinfunction "OUT_A_P$39") (pintype "bidirectional"))
      (node (ref "AMP2") (pin "P$40") (pinfunction "OUT_A_P$40") (pintype "bidirectional"))
      (node (ref "C105") (pin "2") (pinfunction "2_2") (pintype "passive"))
      (node (ref "L10") (pin "P$1") (pinfunction "1_P$1") (pintype "passive"))
    )
    (net (code "31") (name "AMP2_PWM_B") (class "Default")
      (node (ref "AMP2") (pin "P$35") (pinfunction "OUT_B_P$35") (pintype "bidirectional"))
      (node (ref "C106") (pin "2") (pinfunction "2_2") (pintype "passive"))
      (node (ref "L11") (pin "P$1") (pinfunction "1_P$1") (pintype "passive"))
    )
    (net (code "32") (name "AMP2_PWM_C") (class "Default")
      (node (ref "AMP2") (pin "P$32") (pinfunction "OUT_C_P$32") (pintype "bidirectional"))
      (node (ref "C115") (pin "2") (pinfunction "2_2") (pintype "passive"))
      (node (ref "L12") (pin "P$1") (pinfunction "1_P$1") (pintype "passive"))
    )
    (net (code "33") (name "AMP2_PWM_D") (class "Default")
      (node (ref "AMP2") (pin "P$27") (pinfunction "OUT_D_P$27") (pintype "bidirectional"))
      (node (ref "AMP2") (pin "P$28") (pinfunction "OUT_D_P$28") (pintype "bidirectional"))
      (node (ref "C116") (pin "2") (pinfunction "2_2") (pintype "passive"))
      (node (ref "L13") (pin "P$1") (pinfunction "1_P$1") (pintype "passive"))
    )
    (net (code "34") (name "AUX_IN_1_L") (class "Default")
      (node (ref "AUX_IN_1") (pin "2") (pinfunction "2_2") (pintype "passive"))
      (node (ref "R33") (pin "2") (pinfunction "2_2") (pintype "passive"))
    )
    (net (code "35") (name "AUX_IN_1_R") (class "Default")
      (node (ref "AUX_IN_1") (pin "3") (pinfunction "3_3") (pintype "passive"))
      (node (ref "R31") (pin "2") (pinfunction "2_2") (pintype "passive"))
    )
    (net (code "36") (name "AUX_OUT_1_L") (class "Default")
      (node (ref "AUX_OUT_1") (pin "1") (pinfunction "1_1") (pintype "passive"))
      (node (ref "R41") (pin "2") (pinfunction "2_2") (pintype "passive"))
    )
    (net (code "37") (name "AUX_OUT_1_R") (class "Default")
      (node (ref "AUX_OUT_1") (pin "2") (pinfunction "2_2") (pintype "passive"))
      (node (ref "R40") (pin "2") (pinfunction "2_2") (pintype "passive"))
    )
    (net (code "38") (name "AUX_OUT_2_L") (class "Default")
      (node (ref "AUX_OUT_2") (pin "1") (pinfunction "1_1") (pintype "passive"))
      (node (ref "R43") (pin "2") (pinfunction "2_2") (pintype "passive"))
    )
    (net (code "39") (name "AUX_OUT_2_R") (class "Default")
      (node (ref "AUX_OUT_2") (pin "2") (pinfunction "2_2") (pintype "passive"))
      (node (ref "R42") (pin "2") (pinfunction "2_2") (pintype "passive"))
    )
    (net (code "40") (name "A_LINE_A") (class "Default")
      (node (ref "C42") (pin "1") (pinfunction "1_1") (pintype "passive"))
      (node (ref "R36") (pin "1") (pinfunction "1_1") (pintype "passive"))
      (node (ref "R40") (pin "1") (pinfunction "1_1") (pintype "passive"))
      (node (ref "R58") (pin "1") (pinfunction "1_1") (pintype "passive"))
      (node (ref "R59") (pin "2") (pinfunction "2_2") (pintype "passive"))
      (node (ref "SJ6") (pin "2") (pinfunction "2_2") (pintype "passive"))
    )
    (net (code "41") (name "A_LINE_B") (class "Default")
      (node (ref "C44") (pin "1") (pinfunction "1_1") (pintype "passive"))
      (node (ref "R37") (pin "1") (pinfunction "1_1") (pintype "passive"))
      (node (ref "R41") (pin "1") (pinfunction "1_1") (pintype "passive"))
      (node (ref "R65") (pin "1") (pinfunction "1_1") (pintype "passive"))
      (node (ref "R66") (pin "2") (pinfunction "2_2") (pintype "passive"))
      (node (ref "SJ7") (pin "2") (pinfunction "2_2") (pintype "passive"))
    )
    (net (code "42") (name "A_LINE_C") (class "Default")
      (node (ref "C46") (pin "1") (pinfunction "1_1") (pintype "passive"))
      (node (ref "R38") (pin "1") (pinfunction "1_1") (pintype "passive"))
      (node (ref "R42") (pin "1") (pinfunction "1_1") (pintype "passive"))
      (node (ref "R87") (pin "1") (pinfunction "1_1") (pintype "passive"))
      (node (ref "R88") (pin "2") (pinfunction "2_2") (pintype "passive"))
      (node (ref "SJ8") (pin "2") (pinfunction "2_2") (pintype "passive"))
    )
    (net (code "43") (name "A_LINE_D") (class "Default")
      (node (ref "C48") (pin "1") (pinfunction "1_1") (pintype "passive"))
      (node (ref "R39") (pin "1") (pinfunction "1_1") (pintype "passive"))
      (node (ref "R43") (pin "1") (pinfunction "1_1") (pintype "passive"))
      (node (ref "R94") (pin "1") (pinfunction "1_1") (pintype "passive"))
      (node (ref "R95") (pin "2") (pinfunction "2_2") (pintype "passive"))
      (node (ref "SJ9") (pin "2") (pinfunction "2_2") (pintype "passive"))
    )
    (net (code "44") (name "CP2102_D_N") (class "Default")
      (node (ref "IC6") (pin "5") (pinfunction "D-_5") (pintype "bidirectional"))
      (node (ref "VD1") (pin "4") (pinfunction "I/O2_4") (pintype "bidirectional"))
    )
    (net (code "45") (name "CP2102_D_P") (class "Default")
      (node (ref "IC6") (pin "4") (pinfunction "D+_4") (pintype "bidirectional"))
      (node (ref "VD1") (pin "6") (pinfunction "I/O1_6") (pintype "bidirectional"))
    )
    (net (code "46") (name "DSP_DVDD") (class "Default")
      (node (ref "C22") (pin "1") (pinfunction "1_1") (pintype "passive"))
      (node (ref "C23") (pin "1") (pinfunction "1_1") (pintype "passive"))
      (node (ref "C28") (pin "1") (pinfunction "1_1") (pintype "passive"))
      (node (ref "Q3") (pin "2") (pinfunction "C_2") (pintype "passive"))
      (node (ref "Q3") (pin "4") (pinfunction "C_4") (pintype "passive"))
      (node (ref "U3") (pin "13") (pinfunction "DVDD_2_13") (pintype "power_in"))
      (node (ref "U3") (pin "24") (pinfunction "DVDD_24") (pintype "power_in"))
    )
    (net (code "47") (name "DSP_IN_BCLK") (class "Default")
      (node (ref "CHAIN_INPUT") (pin "5") (pinfunction "5_5") (pintype "passive"))
      (node (ref "U3") (pin "9") (pinfunction "MP5_9") (pintype "bidirectional"))
    )
    (net (code "48") (name "DSP_IN_LRCLK") (class "Default")
      (node (ref "CHAIN_INPUT") (pin "6") (pinfunction "6_6") (pintype "passive"))
      (node (ref "U3") (pin "8") (pinfunction "MP4_8") (pintype "bidirectional"))
    )
    (net (code "49") (name "DSP_IN_SDATA0") (class "Default")
      (node (ref "CHAIN_INPUT") (pin "4") (pinfunction "4_4") (pintype "passive"))
      (node (ref "U3") (pin "10") (pinfunction "MP1_10") (pintype "bidirectional"))
    )
    (net (code "50") (name "DSP_IN_SDATA1") (class "Default")
      (node (ref "CHAIN_INPUT") (pin "3") (pinfunction "3_3") (pintype "passive"))
      (node (ref "U3") (pin "11") (pinfunction "MP0_11") (pintype "bidirectional"))
    )
    (net (code "51") (name "DSP_MCLKI") (class "Default")
      (node (ref "CHAIN_INPUT") (pin "2") (pinfunction "2_2") (pintype "passive"))
      (node (ref "CHAIN_OUTPUT") (pin "5") (pinfunction "5_5") (pintype "passive"))
      (node (ref "SJ2") (pin "2") (pinfunction "2_2") (pintype "passive"))
      (node (ref "U3") (pin "32") (pinfunction "MCLKI_32") (pintype "input"))
    )
    (net (code "52") (name "DSP_OSCO") (class "Default")
      (node (ref "R34") (pin "1") (pinfunction "1_1") (pintype "passive"))
      (node (ref "U3") (pin "31") (pinfunction "OSCO_31") (pintype "output"))
    )
    (net (code "53") (name "DSP_OUT_BCLK") (class "Default")
      (node (ref "CHAIN_OUTPUT") (pin "2") (pinfunction "2_2") (pintype "passive"))
      (node (ref "U3") (pin "19") (pinfunction "MP11_19") (pintype "bidirectional"))
    )
    (net (code "54") (name "DSP_OUT_LRCLK") (class "Default")
      (node (ref "CHAIN_OUTPUT") (pin "1") (pinfunction "1_1") (pintype "passive"))
      (node (ref "U3") (pin "16") (pinfunction "MP10_16") (pintype "bidirectional"))
    )
    (net (code "55") (name "DSP_OUT_SDATA0") (class "Default")
      (node (ref "CHAIN_OUTPUT") (pin "3") (pinfunction "3_3") (pintype "passive"))
      (node (ref "U3") (pin "15") (pinfunction "MP6_15") (pintype "bidirectional"))
    )
    (net (code "56") (name "DSP_OUT_SDATA1") (class "Default")
      (node (ref "CHAIN_OUTPUT") (pin "4") (pinfunction "4_4") (pintype "passive"))
      (node (ref "U3") (pin "14") (pinfunction "MP7_14") (pintype "bidirectional"))
    )
    (net (code "57") (name "DSP_RESET") (class "Default")
      (node (ref "R30") (pin "1") (pinfunction "1_1") (pintype "passive"))
      (node (ref "U1") (pin "10") (pinfunction "IO25_10") (pintype "bidirectional"))
      (node (ref "U3") (pin "5") (pinfunction "~{RESET}_5") (pintype "input"))
    )
    (net (code "58") (name "DSP_SELFBOOT") (class "Default")
      (node (ref "SJ1") (pin "2") (pinfunction "2_2") (pintype "passive"))
      (node (ref "U3") (pin "6") (pinfunction "SELFBOOT_6") (pintype "input"))
    )
    (net (code "59") (name "DSP_VDRIVE") (class "Default")
      (node (ref "Q3") (pin "1") (pinfunction "B_1") (pintype "passive"))
      (node (ref "R29") (pin "1") (pinfunction "1_1") (pintype "passive"))
      (node (ref "U3") (pin "17") (pinfunction "VDRIVE_17") (pintype "output"))
    )
    (net (code "60") (name "DSP_VOUT0") (class "Default")
      (node (ref "C41") (pin "+") (pinfunction "+_+") (pintype "passive"))
      (node (ref "SJ6") (pin "1") (pinfunction "1_1") (pintype "passive"))
      (node (ref "U3") (pin "46") (pinfunction "VOUT0_46") (pintype "output"))
    )
    (net (code "61") (name "DSP_VOUT1") (class "Default")
      (node (ref "C43") (pin "+") (pinfunction "+_+") (pintype "passive"))
      (node (ref "SJ7") (pin "1") (pinfunction "1_1") (pintype "passive"))
      (node (ref "U3") (pin "45") (pinfunction "VOUT1_45") (pintype "output"))
    )
    (net (code "62") (name "DSP_VOUT2") (class "Default")
      (node (ref "C45") (pin "+") (pinfunction "+_+") (pintype "passive"))
      (node (ref "SJ8") (pin "1") (pinfunction "1_1") (pintype "passive"))
      (node (ref "U3") (pin "44") (pinfunction "VOUT2_44") (pintype "output"))
    )
    (net (code "63") (name "DSP_VOUT3") (class "Default")
      (node (ref "C47") (pin "+") (pinfunction "+_+") (pintype "passive"))
      (node (ref "SJ9") (pin "1") (pinfunction "1_1") (pintype "passive"))
      (node (ref "U3") (pin "43") (pinfunction "VOUT3_43") (pintype "output"))
    )
    (net (code "64") (name "ESP_EN") (class "Default")
      (node (ref "Q1") (pin "C") (pinfunction "C_C") (pintype "passive"))
      (node (ref "R13") (pin "1") (pinfunction "1_1") (pintype "passive"))
      (node (ref "S1") (pin "A2") (pinfunction "1_A2") (pintype "passive"))
      (node (ref "U1") (pin "3") (pinfunction "EN_3") (pintype "input"))
    )
    (net (code "65") (name "ESP_IO0") (class "Default")
      (node (ref "Q2") (pin "C") (pinfunction "C_C") (pintype "passive"))
      (node (ref "S2") (pin "A2") (pinfunction "1_A2") (pintype "passive"))
      (node (ref "U1") (pin "25") (pinfunction "IO0_25") (pintype "bidirectional"))
    )
    (net (code "66") (name "ESP_IO26") (class "Default")
      (node (ref "IO26") (pin "1") (pinfunction "P_1") (pintype "passive"))
      (node (ref "U1") (pin "11") (pinfunction "IO26_11") (pintype "bidirectional"))
    )
    (net (code "67") (name "ESP_IO27") (class "Default")
      (node (ref "IO27") (pin "1") (pinfunction "P_1") (pintype "passive"))
      (node (ref "U1") (pin "12") (pinfunction "IO27_12") (pintype "bidirectional"))
    )
    (net (code "68") (name "ESP_IO32") (class "Default")
      (node (ref "IO32") (pin "1") (pinfunction "P_1") (pintype "passive"))
      (node (ref "U1") (pin "8") (pinfunction "IO32_8") (pintype "bidirectional"))
    )
    (net (code "69") (name "ESP_IO33") (class "Default")
      (node (ref "IO33") (pin "1") (pinfunction "P_1") (pintype "passive"))
      (node (ref "U1") (pin "9") (pinfunction "IO33_9") (pintype "bidirectional"))
    )
    (net (code "70") (name "ESP_IO34") (class "Default")
      (node (ref "IO34") (pin "1") (pinfunction "P_1") (pintype "passive"))
      (node (ref "U1") (pin "6") (pinfunction "IO34_6") (pintype "bidirectional"))
    )
    (net (code "71") (name "ESP_RXD0") (class "Default")
      (node (ref "IC6") (pin "26") (pinfunction "TXD_26") (pintype "output"))
      (node (ref "J4") (pin "2") (pinfunction "2_2") (pintype "passive"))
      (node (ref "U1") (pin "34") (pinfunction "RXD0_34") (pintype "bidirectional"))
    )
    (net (code "72") (name "ESP_TXD0") (class "Default")
      (node (ref "IC6") (pin "25") (pinfunction "RXD_25") (pintype "input"))
      (node (ref "J4") (pin "1") (pinfunction "1_1") (pintype "passive"))
      (node (ref "U1") (pin "35") (pinfunction "TXD0_35") (pintype "bidirectional"))
    )
    (net (code "73") (name "GND") (class "Default")
      (node (ref "AMP1") (pin "P$12") (pinfunction "GND_P$12") (pintype "bidirectional"))
      (node (ref "AMP1") (pin "P$13") (pinfunction "GND_P$13") (pintype "bidirectional"))
      (node (ref "AMP1") (pin "P$25") (pinfunction "GND_P$25") (pintype "bidirectional"))
      (node (ref "AMP1") (pin "P$26") (pinfunction "GND_P$26") (pintype "bidirectional"))
      (node (ref "AMP1") (pin "P$3") (pinfunction "M1_P$3") (pintype "bidirectional"))
      (node (ref "AMP1") (pin "P$33") (pinfunction "GND_P$33") (pintype "bidirectional"))
      (node (ref "AMP1") (pin "P$34") (pinfunction "GND_P$34") (pintype "bidirectional"))
      (node (ref "AMP1") (pin "P$4") (pinfunction "M2_P$4") (pintype "bidirectional"))
      (node (ref "AMP1") (pin "P$41") (pinfunction "GND_P$41") (pintype "bidirectional"))
      (node (ref "AMP1") (pin "P$42") (pinfunction "GND_P$42") (pintype "bidirectional"))
      (node (ref "AMP2") (pin "P$12") (pinfunction "GND_P$12") (pintype "bidirectional"))
      (node (ref "AMP2") (pin "P$13") (pinfunction "GND_P$13") (pintype "bidirectional"))
      (node (ref "AMP2") (pin "P$25") (pinfunction "GND_P$25") (pintype "bidirectional"))
      (node (ref "AMP2") (pin "P$26") (pinfunction "GND_P$26") (pintype "bidirectional"))
      (node (ref "AMP2") (pin "P$3") (pinfunction "M1_P$3") (pintype "bidirectional"))
      (node (ref "AMP2") (pin "P$33") (pinfunction "GND_P$33") (pintype "bidirectional"))
      (node (ref "AMP2") (pin "P$34") (pinfunction "GND_P$34") (pintype "bidirectional"))
      (node (ref "AMP2") (pin "P$4") (pinfunction "M2_P$4") (pintype "bidirectional"))
      (node (ref "AMP2") (pin "P$41") (pinfunction "GND_P$41") (pintype "bidirectional"))
      (node (ref "AMP2") (pin "P$42") (pinfunction "GND_P$42") (pintype "bidirectional"))
      (node (ref "AUX_IN_1") (pin "1") (pinfunction "1_1") (pintype "passive"))
      (node (ref "AUX_OUT_1") (pin "3") (pinfunction "3_3") (pintype "passive"))
      (node (ref "AUX_OUT_2") (pin "3") (pinfunction "3_3") (pintype "passive"))
      (node (ref "C1") (pin "-") (pinfunction "-_-") (pintype "passive"))
      (node (ref "C10") (pin "2") (pinfunction "2_2") (pintype "passive"))
      (node (ref "C100") (pin "2") (pinfunction "2_2") (pintype "passive"))
      (node (ref "C107") (pin "2") (pinfunction "2_2") (pintype "passive"))
      (node (ref "C108") (pin "2") (pinfunction "2_2") (pintype "passive"))
      (node (ref "C111") (pin "2") (pinfunction "2_2") (pintype "passive"))
      (node (ref "C112") (pin "2") (pinfunction "2_2") (pintype "passive"))
      (node (ref "C117") (pin "1") (pinfunction "1_1") (pintype "passive"))
      (node (ref "C118") (pin "2") (pinfunction "2_2") (pintype "passive"))
      (node (ref "C119") (pin "2") (pinfunction "2_2") (pintype "passive"))
      (node (ref "C12") (pin "2") (pinfunction "2_2") (pintype "passive"))
      (node (ref "C120") (pin "2") (pinfunction "2_2") (pintype "passive"))
      (node (ref "C121") (pin "2") (pinfunction "2_2") (pintype "passive"))
      (node (ref "C122") (pin "2") (pinfunction "2_2") (pintype "passive"))
      (node (ref "C123") (pin "2") (pinfunction "2_2") (pintype "passive"))
      (node (ref "C124") (pin "-") (pinfunction "-_-") (pintype "passive"))
      (node (ref "C125") (pin "-") (pinfunction "-_-") (pintype "passive"))
      (node (ref "C126") (pin "2") (pinfunction "2_2") (pintype "passive"))
      (node (ref "C127") (pin "2") (pinfunction "2_2") (pintype "passive"))
      (node (ref "C128") (pin "2") (pinfunction "2_2") (pintype "passive"))
      (node (ref "C129") (pin "2") (pinfunction "2_2") (pintype "passive"))
      (node (ref "C13") (pin "2") (pinfunction "2_2") (pintype "passive"))
      (node (ref "C130") (pin "2") (pinfunction "2_2") (pintype "passive"))
      (node (ref "C131") (pin "2") (pinfunction "2_2") (pintype "passive"))
      (node (ref "C132") (pin "2") (pinfunction "2_2") (pintype "passive"))
      (node (ref "C133") (pin "2") (pinfunction "2_2") (pintype "passive"))
      (node (ref "C134") (pin "2") (pinfunction "2_2") (pintype "passive"))
      (node (ref "C139") (pin "1") (pinfunction "1_1") (pintype "passive"))
      (node (ref "C140") (pin "1") (pinfunction "1_1") (pintype "passive"))
      (node (ref "C145") (pin "1") (pinfunction "1_1") (pintype "passive"))
      (node (ref "C146") (pin "1") (pinfunction "1_1") (pintype "passive"))
      (node (ref "C147") (pin "2") (pinfunction "2_2") (pintype "passive"))
      (node (ref "C148") (pin "2") (pinfunction "2_2") (pintype "passive"))
      (node (ref "C15") (pin "2") (pinfunction "2_2") (pintype "passive"))
      (node (ref "C17") (pin "-") (pinfunction "-_-") (pintype "passive"))
      (node (ref "C18") (pin "2") (pinfunction "2_2") (pintype "passive"))
      (node (ref "C19") (pin "2") (pinfunction "2_2") (pintype "passive"))
      (node (ref "C2") (pin "-") (pinfunction "-_-") (pintype "passive"))
      (node (ref "C20") (pin "2") (pinfunction "2_2") (pintype "passive"))
      (node (ref "C22") (pin "2") (pinfunction "2_2") (pintype "passive"))
      (node (ref "C23") (pin "2") (pinfunction "2_2") (pintype "passive"))
      (node (ref "C24") (pin "2") (pinfunction "2_2") (pintype "passive"))
      (node (ref "C25") (pin "2") (pinfunction "2_2") (pintype "passive"))
      (node (ref "C26") (pin "2") (pinfunction "2_2") (pintype "passive"))
      (node (ref "C27") (pin "2") (pinfunction "2_2") (pintype "passive"))
      (node (ref "C28") (pin "2") (pinfunction "2_2") (pintype "passive"))
      (node (ref "C29") (pin "2") (pinfunction "2_2") (pintype "passive"))
      (node (ref "C3") (pin "2") (pinfunction "2_2") (pintype "passive"))
      (node (ref "C30") (pin "2") (pinfunction "2_2") (pintype "passive"))
      (node (ref "C31") (pin "2") (pinfunction "2_2") (pintype "passive"))
      (node (ref "C32") (pin "2") (pinfunction "2_2") (pintype "passive"))
      (node (ref "C33") (pin "1") (pinfunction "1_1") (pintype "passive"))
      (node (ref "C34") (pin "1") (pinfunction "1_1") (pintype "passive"))
      (node (ref "C35") (pin "1") (pinfunction "1_1") (pintype "passive"))
      (node (ref "C36") (pin "1") (pinfunction "1_1") (pintype "passive"))
      (node (ref "C37") (pin "1") (pinfunction "1_1") (pintype "passive"))
      (node (ref "C38") (pin "1") (pinfunction "1_1") (pintype "passive"))
      (node (ref "C4") (pin "2") (pinfunction "2_2") (pintype "passive"))
      (node (ref "C42") (pin "2") (pinfunction "2_2") (pintype "passive"))
      (node (ref "C44") (pin "2") (pinfunction "2_2") (pintype "passive"))
      (node (ref "C46") (pin "2") (pinfunction "2_2") (pintype "passive"))
      (node (ref "C48") (pin "2") (pinfunction "2_2") (pintype "passive"))
      (node (ref "C49") (pin "2") (pinfunction "2_2") (pintype "passive"))
      (node (ref "C50") (pin "2") (pinfunction "2_2") (pintype "passive"))
      (node (ref "C51") (pin "2") (pinfunction "2_2") (pintype "passive"))
      (node (ref "C53") (pin "-") (pinfunction "-_-") (pintype "passive"))
      (node (ref "C54") (pin "2") (pinfunction "2_2") (pintype "passive"))
      (node (ref "C55") (pin "2") (pinfunction "2_2") (pintype "passive"))
      (node (ref "C56") (pin "2") (pinfunction "2_2") (pintype "passive"))
      (node (ref "C57") (pin "2") (pinfunction "2_2") (pintype "passive"))
      (node (ref "C58") (pin "2") (pinfunction "2_2") (pintype "passive"))
      (node (ref "C59") (pin "-") (pinfunction "-_-") (pintype "passive"))
      (node (ref "C6") (pin "-") (pinfunction "-_-") (pintype "passive"))
      (node (ref "C60") (pin "-") (pinfunction "-_-") (pintype "passive"))
      (node (ref "C61") (pin "2") (pinfunction "2_2") (pintype "passive"))
      (node (ref "C62") (pin "2") (pinfunction "2_2") (pintype "passive"))
      (node (ref "C63") (pin "2") (pinfunction "2_2") (pintype "passive"))
      (node (ref "C64") (pin "2") (pinfunction "2_2") (pintype "passive"))
      (node (ref "C65") (pin "2") (pinfunction "2_2") (pintype "passive"))
      (node (ref "C66") (pin "2") (pinfunction "2_2") (pintype "passive"))
      (node (ref "C67") (pin "2") (pinfunction "2_2") (pintype "passive"))
      (node (ref "C68") (pin "2") (pinfunction "2_2") (pintype "passive"))
      (node (ref "C69") (pin "2") (pinfunction "2_2") (pintype "passive"))
      (node (ref "C7") (pin "1") (pinfunction "1_1") (pintype "passive"))
      (node (ref "C70") (pin "2") (pinfunction "2_2") (pintype "passive"))
      (node (ref "C75") (pin "1") (pinfunction "1_1") (pintype "passive"))
      (node (ref "C76") (pin "1") (pinfunction "1_1") (pintype "passive"))
      (node (ref "C8") (pin "-") (pinfunction "-_-") (pintype "passive"))
      (node (ref "C81") (pin "1") (pinfunction "1_1") (pintype "passive"))
      (node (ref "C82") (pin "1") (pinfunction "1_1") (pintype "passive"))
      (node (ref "C83") (pin "2") (pinfunction "2_2") (pintype "passive"))
      (node (ref "C84") (pin "2") (pinfunction "2_2") (pintype "passive"))
      (node (ref "C85") (pin "2") (pinfunction "2_2") (pintype "passive"))
      (node (ref "C86") (pin "2") (pinfunction "2_2") (pintype "passive"))
      (node (ref "C87") (pin "2") (pinfunction "2_2") (pintype "passive"))
      (node (ref "C88") (pin "2") (pinfunction "2_2") (pintype "passive"))
      (node (ref "C89") (pin "2") (pinfunction "2_2") (pintype "passive"))
      (node (ref "C9") (pin "2") (pinfunction "2_2") (pintype "passive"))
      (node (ref "C90") (pin "2") (pinfunction "2_2") (pintype "passive"))
      (node (ref "C93") (pin "2") (pinfunction "2_2") (pintype "passive"))
      (node (ref "C94") (pin "2") (pinfunction "2_2") (pintype "passive"))
      (node (ref "C97") (pin "2") (pinfunction "2_2") (pintype "passive"))
      (node (ref "C98") (pin "2") (pinfunction "2_2") (pintype "passive"))
      (node (ref "C99") (pin "2") (pinfunction "2_2") (pintype "passive"))
      (node (ref "CHAIN_INPUT") (pin "1") (pinfunction "1_1") (pintype "passive"))
      (node (ref "CHAIN_OUTPUT") (pin "6") (pinfunction "6_6") (pintype "passive"))
      (node (ref "D1") (pin "1") (pinfunction "A_1") (pintype "passive"))
      (node (ref "D1") (pin "3") (pinfunction "A_3") (pintype "passive"))
      (node (ref "IC1") (pin "4") (pinfunction "V-_4") (pintype "power_in"))
      (node (ref "IC2") (pin "4") (pinfunction "V-_4") (pintype "power_in"))
      (node (ref "IC3") (pin "4") (pinfunction "V-_4") (pintype "power_in"))
      (node (ref "IC4") (pin "4") (pinfunction "V-_4") (pintype "power_in"))
      (node (ref "IC5") (pin "4") (pinfunction "V-_4") (pintype "power_in"))
      (node (ref "IC6") (pin "3") (pinfunction "GND_3") (pintype "power_in"))
      (node (ref "IC6") (pin "EXP") (pinfunction "GND_EXP") (pintype "power_in"))
      (node (ref "IC6") (pin "M") (pinfunction "GND_M") (pintype "power_in"))
      (node (ref "IO1") (pin "1") (pinfunction "P_1") (pintype "passive"))
      (node (ref "IO4") (pin "1") (pinfunction "P_1") (pintype "passive"))
      (node (ref "IO5") (pin "1") (pinfunction "P_1") (pintype "passive"))
      (node (ref "J1") (pin "4") (pinfunction "GND_4") (pintype "bidirectional"))
      (node (ref "J1") (pin "S1") (pinfunction "SHIELD_S1") (pintype "bidirectional"))
      (node (ref "J1") (pin "S2") (pinfunction "SHIELD_S2") (pintype "bidirectional"))
      (node (ref "J1") (pin "S3") (pinfunction "SHIELD_S3") (pintype "bidirectional"))
      (node (ref "J1") (pin "S4") (pinfunction "SHIELD_S4") (pintype "bidirectional"))
      (node (ref "J2") (pin "4") (pinfunction "GND_4") (pintype "bidirectional"))
      (node (ref "J2") (pin "S1") (pinfunction "SHIELD_S1") (pintype "bidirectional"))
      (node (ref "J2") (pin "S2") (pinfunction "SHIELD_S2") (pintype "bidirectional"))
      (node (ref "J2") (pin "S3") (pinfunction "SHIELD_S3") (pintype "bidirectional"))
      (node (ref "J2") (pin "S4") (pinfunction "SHIELD_S4") (pintype "bidirectional"))
      (node (ref "J3") (pin "1") (pinfunction "GND_1") (pintype "power_in"))
      (node (ref "J3") (pin "12") (pinfunction "GND_12") (pintype "power_in"))
      (node (ref "J3") (pin "S1") (pinfunction "SHIELD_S1") (pintype "passive"))
      (node (ref "J3") (pin "S2") (pinfunction "SHIELD_S2") (pintype "passive"))
      (node (ref "J3") (pin "S3") (pinfunction "SHIELD_S3") (pintype "passive"))
      (node (ref "J3") (pin "S4") (pinfunction "SHIELD_S4") (pintype "passive"))
      (node (ref "J3") (pin "S5") (pinfunction "SHIELD_S5") (pintype "passive"))
      (node (ref "J3") (pin "S6") (pinfunction "SHIELD_S6") (pintype "passive"))
      (node (ref "J4") (pin "3") (pinfunction "3_3") (pintype "passive"))
      (node (ref "J5") (pin "3") (pinfunction "3_3") (pintype "passive"))
      (node (ref "J6") (pin "1") (pinfunction "1_1") (pintype "passive"))
      (node (ref "J7") (pin "6") (pinfunction "SUPPLY_VOLTAGE_GROUND_6") (pintype "power_in"))
      (node (ref "J7") (pin "S1") (pinfunction "SHIELD_S1") (pintype "passive"))
      (node (ref "J7") (pin "S2") (pinfunction "SHIELD_S2") (pintype "passive"))
      (node (ref "J7") (pin "S3") (pinfunction "SHIELD_S3") (pintype "passive"))
      (node (ref "J7") (pin "S4") (pinfunction "SHIELD_S4") (pintype "passive"))
      (node (ref "LED_SYS") (pin "C") (pinfunction "C_C") (pintype "passive"))
      (node (ref "POT0") (pin "A") (pinfunction "A_A") (pintype "passive"))
      (node (ref "POT1") (pin "A") (pinfunction "A_A") (pintype "passive"))
      (node (ref "POT2") (pin "A") (pinfunction "A_A") (pintype "passive"))
      (node (ref "POT3") (pin "A") (pinfunction "A_A") (pintype "passive"))
      (node (ref "R1") (pin "1") (pinfunction "1_1") (pintype "passive"))
      (node (ref "R10") (pin "1") (pinfunction "1_1") (pintype "passive"))
      (node (ref "R12") (pin "1") (pinfunction "1_1") (pintype "passive"))
      (node (ref "R18") (pin "2") (pinfunction "2_2") (pintype "passive"))
      (node (ref "R19") (pin "2") (pinfunction "2_2") (pintype "passive"))
      (node (ref "R21") (pin "2") (pinfunction "2_2") (pintype "passive"))
      (node (ref "R32") (pin "2") (pinfunction "2_2") (pintype "passive"))
      (node (ref "R4") (pin "1") (pinfunction "1_1") (pintype "passive"))
      (node (ref "R50") (pin "1") (pinfunction "1_1") (pintype "passive"))
      (node (ref "R51") (pin "1") (pinfunction "1_1") (pintype "passive"))
      (node (ref "R59") (pin "1") (pinfunction "1_1") (pintype "passive"))
      (node (ref "R66") (pin "1") (pinfunction "1_1") (pintype "passive"))
      (node (ref "R7") (pin "1") (pinfunction "1_1") (pintype "passive"))
      (node (ref "R70") (pin "1") (pinfunction "1_1") (pintype "passive"))
      (node (ref "R71") (pin "2") (pinfunction "2_2") (pintype "passive"))
      (node (ref "R72") (pin "2") (pinfunction "2_2") (pintype "passive"))
      (node (ref "R73") (pin "2") (pinfunction "2_2") (pintype "passive"))
      (node (ref "R74") (pin "2") (pinfunction "2_2") (pintype "passive"))
      (node (ref "R75") (pin "2") (pinfunction "2_2") (pintype "passive"))
      (node (ref "R76") (pin "2") (pinfunction "2_2") (pintype "passive"))
      (node (ref "R77") (pin "2") (pinfunction "2_2") (pintype "passive"))
      (node (ref "R78") (pin "2") (pinfunction "2_2") (pintype "passive"))
      (node (ref "R79") (pin "1") (pinfunction "1_1") (pintype "passive"))
      (node (ref "R80") (pin "1") (pinfunction "1_1") (pintype "passive"))
      (node (ref "R88") (pin "1") (pinfunction "1_1") (pintype "passive"))
      (node (ref "R95") (pin "1") (pinfunction "1_1") (pintype "passive"))
      (node (ref "R99") (pin "1") (pinfunction "1_1") (pintype "passive"))
      (node (ref "REG1") (pin "7") (pinfunction "GND_7") (pintype "bidirectional"))
      (node (ref "REG1") (pin "EXP") (pinfunction "PWRPD_EXP") (pintype "bidirectional"))
      (node (ref "REG2") (pin "4") (pinfunction "GND_4") (pintype "power_in"))
      (node (ref "REG2") (pin "EPAD") (pinfunction "EPAD_EPAD") (pintype "passive"))
      (node (ref "REG3") (pin "4") (pinfunction "GND_4") (pintype "power_in"))
      (node (ref "REG3") (pin "EPAD") (pinfunction "EPAD_EPAD") (pintype "passive"))
      (node (ref "S1") (pin "B2") (pinfunction "2_B2") (pintype "passive"))
      (node (ref "S2") (pin "B2") (pinfunction "2_B2") (pintype "passive"))
      (node (ref "SJ1") (pin "1") (pinfunction "1_1") (pintype "passive"))
      (node (ref "U$1") (pin "-") (pinfunction "GND_-") (pintype "bidirectional"))
      (node (ref "U1") (pin "1") (pinfunction "GND_1") (pintype "power_in"))
      (node (ref "U1") (pin "15") (pinfunction "GND_15") (pintype "power_in"))
      (node (ref "U1") (pin "38") (pinfunction "GND_38") (pintype "power_in"))
      (node (ref "U1") (pin "GND") (pinfunction "GND_GND") (pintype "power_in"))
      (node (ref "U3") (pin "1") (pinfunction "AGND_2_1") (pintype "power_in"))
      (node (ref "U3") (pin "12") (pinfunction "DGND_2_12") (pintype "power_in"))
      (node (ref "U3") (pin "20") (pinfunction "ADDR1/CDATA/WB_20") (pintype "input"))
      (node (ref "U3") (pin "25") (pinfunction "DGND_25") (pintype "power_in"))
      (node (ref "U3") (pin "30") (pinfunction "RSVD_30") (pintype "passive"))
      (node (ref "U3") (pin "33") (pinfunction "PGND_33") (pintype "power_in"))
      (node (ref "U3") (pin "37") (pinfunction "AGND_3_37") (pintype "power_in"))
      (node (ref "U3") (pin "38") (pinfunction "PLL_MODE0_38") (pintype "input"))
      (node (ref "U3") (pin "42") (pinfunction "AGND_42") (pintype "power_in"))
      (node (ref "U3") (pin "7") (pinfunction "ADDR0_7") (pintype "input"))
      (node (ref "VD1") (pin "2") (pinfunction "GND_2") (pintype "bidirectional"))
      (node (ref "X1") (pin "2") (pinfunction "KL_2") (pintype "passive"))
      (node (ref "X2") (pin "2") (pinfunction "KL_2") (pintype "passive"))
    )
    (net (code "74") (name "I2C_SCL") (class "Default")
      (node (ref "J5") (pin "1") (pinfunction "1_1") (pintype "passive"))
      (node (ref "R14") (pin "2") (pinfunction "2_2") (pintype "passive"))
      (node (ref "U1") (pin "36") (pinfunction "IO22_36") (pintype "bidirectional"))
      (node (ref "U3") (pin "23") (pinfunction "SCL/CCLK_23") (pintype "bidirectional"))
    )
    (net (code "75") (name "I2C_SDA") (class "Default")
      (node (ref "J5") (pin "2") (pinfunction "2_2") (pintype "passive"))
      (node (ref "R15") (pin "2") (pinfunction "2_2") (pintype "passive"))
      (node (ref "U1") (pin "33") (pinfunction "IO21_33") (pintype "bidirectional"))
      (node (ref "U3") (pin "22") (pinfunction "SDA/COUT_22") (pintype "bidirectional"))
    )
    (net (code "76") (name "LED_SYS") (class "Default")
      (node (ref "R28") (pin "1") (pinfunction "1_1") (pintype "passive"))
      (node (ref "U1") (pin "28") (pinfunction "IO17_28") (pintype "bidirectional"))
    )
    (net (code "77") (name "Net-(AMP1-AVDD)") (class "Default")
      (node (ref "AMP1") (pin "P$14") (pinfunction "AVDD_P$14") (pintype "bidirectional"))
      (node (ref "C62") (pin "1") (pinfunction "1_1") (pintype "passive"))
    )
    (net (code "78") (name "Net-(AMP1-C_START)") (class "Default")
      (node (ref "AMP1") (pin "P$15") (pinfunction "C_START_P$15") (pintype "bidirectional"))
      (node (ref "C7") (pin "2") (pinfunction "2_2") (pintype "passive"))
    )
    (net (code "79") (name "Net-(AMP1-DVDD)") (class "Default")
      (node (ref "AMP1") (pin "P$11") (pinfunction "DVDD_P$11") (pintype "bidirectional"))
      (node (ref "C61") (pin "1") (pinfunction "1_1") (pintype "passive"))
    )
    (net (code "80") (name "Net-(AMP1-FREQ_ADJ)") (class "Default")
      (node (ref "AMP1") (pin "P$8") (pinfunction "FREQ_ADJ_P$8") (pintype "bidirectional"))
      (node (ref "R50") (pin "2") (pinfunction "2_2") (pintype "passive"))
    )
    (net (code "81") (name "Net-(AMP1-GVDD_AB)") (class "Default")
      (node (ref "AMP1") (pin "P$1") (pinfunction "GVDD_AB_P$1") (pintype "bidirectional"))
      (node (ref "C65") (pin "1") (pinfunction "1_1") (pintype "passive"))
      (node (ref "R54") (pin "2") (pinfunction "2_2") (pintype "passive"))
    )
    (net (code "82") (name "Net-(AMP1-GVDD_CD)") (class "Default")
      (node (ref "AMP1") (pin "P$22") (pinfunction "GVDD_CD_P$22") (pintype "bidirectional"))
      (node (ref "C63") (pin "1") (pinfunction "1_1") (pintype "passive"))
      (node (ref "R53") (pin "2") (pinfunction "2_2") (pintype "passive"))
    )
    (net (code "83") (name "Net-(AMP1-OC_ADJ)") (class "Default")
      (node (ref "AMP1") (pin "P$7") (pinfunction "OC_ADJ_P$7") (pintype "bidirectional"))
      (node (ref "R51") (pin "2") (pinfunction "2_2") (pintype "passive"))
    )
    (net (code "84") (name "Net-(AMP1-VBG)") (class "Default")
      (node (ref "AMP1") (pin "P$20") (pinfunction "VBG_P$20") (pintype "bidirectional"))
      (node (ref "C54") (pin "1") (pinfunction "1_1") (pintype "passive"))
    )
    (net (code "85") (name "Net-(AMP1-VDD)") (class "Default")
      (node (ref "AMP1") (pin "P$2") (pinfunction "VDD_P$2") (pintype "bidirectional"))
      (node (ref "C64") (pin "1") (pinfunction "1_1") (pintype "passive"))
      (node (ref "L4") (pin "2") (pinfunction "2_2") (pintype "passive"))
    )
    (net (code "86") (name "Net-(AMP1-~{RESET})") (class "Default")
      (node (ref "AMP1") (pin "P$18") (pinfunction "~{RESET}_P$18") (pintype "bidirectional"))
      (node (ref "R52") (pin "2") (pinfunction "2_2") (pintype "passive"))
    )
    (net (code "87") (name "Net-(AMP2-AVDD)") (class "Default")
      (node (ref "AMP2") (pin "P$14") (pinfunction "AVDD_P$14") (pintype "bidirectional"))
      (node (ref "C119") (pin "1") (pinfunction "1_1") (pintype "passive"))
    )
    (net (code "88") (name "Net-(AMP2-C_START)") (class "Default")
      (node (ref "AMP2") (pin "P$15") (pinfunction "C_START_P$15") (pintype "bidirectional"))
      (node (ref "C117") (pin "2") (pinfunction "2_2") (pintype "passive"))
    )
    (net (code "89") (name "Net-(AMP2-DVDD)") (class "Default")
      (node (ref "AMP2") (pin "P$11") (pinfunction "DVDD_P$11") (pintype "bidirectional"))
      (node (ref "C118") (pin "1") (pinfunction "1_1") (pintype "passive"))
    )
    (net (code "90") (name "Net-(AMP2-FREQ_ADJ)") (class "Default")
      (node (ref "AMP2") (pin "P$8") (pinfunction "FREQ_ADJ_P$8") (pintype "bidirectional"))
      (node (ref "R79") (pin "2") (pinfunction "2_2") (pintype "passive"))
    )
    (net (code "91") (name "Net-(AMP2-GVDD_AB)") (class "Default")
      (node (ref "AMP2") (pin "P$1") (pinfunction "GVDD_AB_P$1") (pintype "bidirectional"))
      (node (ref "C128") (pin "1") (pinfunction "1_1") (pintype "passive"))
      (node (ref "R83") (pin "2") (pinfunction "2_2") (pintype "passive"))
    )
    (net (code "92") (name "Net-(AMP2-GVDD_CD)") (class "Default")
      (node (ref "AMP2") (pin "P$22") (pinfunction "GVDD_CD_P$22") (pintype "bidirectional"))
      (node (ref "C126") (pin "1") (pinfunction "1_1") (pintype "passive"))
      (node (ref "R82") (pin "2") (pinfunction "2_2") (pintype "passive"))
    )
    (net (code "93") (name "Net-(AMP2-OC_ADJ)") (class "Default")
      (node (ref "AMP2") (pin "P$7") (pinfunction "OC_ADJ_P$7") (pintype "bidirectional"))
      (node (ref "R80") (pin "2") (pinfunction "2_2") (pintype "passive"))
    )
    (net (code "94") (name "Net-(AMP2-VBG)") (class "Default")
      (node (ref "AMP2") (pin "P$20") (pinfunction "VBG_P$20") (pintype "bidirectional"))
      (node (ref "C129") (pin "1") (pinfunction "1_1") (pintype "passive"))
    )
    (net (code "95") (name "Net-(AMP2-VDD)") (class "Default")
      (node (ref "AMP2") (pin "P$2") (pinfunction "VDD_P$2") (pintype "bidirectional"))
      (node (ref "C127") (pin "1") (pinfunction "1_1") (pintype "passive"))
      (node (ref "L14") (pin "2") (pinfunction "2_2") (pintype "passive"))
    )
    (net (code "96") (name "Net-(AMP2-~{RESET})") (class "Default")
      (node (ref "AMP2") (pin "P$18") (pinfunction "~{RESET}_P$18") (pintype "bidirectional"))
      (node (ref "R81") (pin "2") (pinfunction "2_2") (pintype "passive"))
    )
    (net (code "97") (name "Net-(C3-Pad1)") (class "Default")
      (node (ref "C3") (pin "1") (pinfunction "1_1") (pintype "passive"))
      (node (ref "R2") (pin "1") (pinfunction "1_1") (pintype "passive"))
    )
    (net (code "98") (name "Net-(C31-Pad1)") (class "Default")
      (node (ref "C31") (pin "1") (pinfunction "1_1") (pintype "passive"))
      (node (ref "Q4") (pin "2") (pinfunction "2_2") (pintype "passive"))
      (node (ref "R34") (pin "2") (pinfunction "2_2") (pintype "passive"))
    )
    (net (code "99") (name "Net-(C32-Pad1)") (class "Default")
      (node (ref "C32") (pin "1") (pinfunction "1_1") (pintype "passive"))
      (node (ref "Q4") (pin "1") (pinfunction "1_1") (pintype "passive"))
      (node (ref "SJ2") (pin "1") (pinfunction "1_1") (pintype "passive"))
    )
    (net (code "100") (name "Net-(C40-Pad2)") (class "Default")
      (node (ref "C40") (pin "2") (pinfunction "2_2") (pintype "passive"))
      (node (ref "R35") (pin "2") (pinfunction "2_2") (pintype "passive"))
    )
    (net (code "101") (name "Net-(C41-Pad-)") (class "Default")
      (node (ref "C41") (pin "-") (pinfunction "-_-") (pintype "passive"))
      (node (ref "R36") (pin "2") (pinfunction "2_2") (pintype "passive"))
    )
    (net (code "102") (name "Net-(C43-Pad-)") (class "Default")
      (node (ref "C43") (pin "-") (pinfunction "-_-") (pintype "passive"))
      (node (ref "R37") (pin "2") (pinfunction "2_2") (pintype "passive"))
    )
    (net (code "103") (name "Net-(C45-Pad-)") (class "Default")
      (node (ref "C45") (pin "-") (pinfunction "-_-") (pintype "passive"))
      (node (ref "R38") (pin "2") (pinfunction "2_2") (pintype "passive"))
    )
    (net (code "104") (name "Net-(C47-Pad-)") (class "Default")
      (node (ref "C47") (pin "-") (pinfunction "-_-") (pintype "passive"))
      (node (ref "R39") (pin "2") (pinfunction "2_2") (pintype "passive"))
    )
    (net (code "105") (name "Net-(C73-Pad2)") (class "Default")
      (node (ref "C73") (pin "2") (pinfunction "2_2") (pintype "passive"))
      (node (ref "R60") (pin "1") (pinfunction "1_1") (pintype "passive"))
    )
    (net (code "106") (name "Net-(C74-Pad2)") (class "Default")
      (node (ref "C74") (pin "2") (pinfunction "2_2") (pintype "passive"))
      (node (ref "R61") (pin "1") (pinfunction "1_1") (pintype "passive"))
    )
    (net (code "107") (name "Net-(C79-Pad2)") (class "Default")
      (node (ref "C79") (pin "2") (pinfunction "2_2") (pintype "passive"))
      (node (ref "R67") (pin "1") (pinfunction "1_1") (pintype "passive"))
    )
    (net (code "108") (name "Net-(C80-Pad2)") (class "Default")
      (node (ref "C80") (pin "2") (pinfunction "2_2") (pintype "passive"))
      (node (ref "R68") (pin "1") (pinfunction "1_1") (pintype "passive"))
    )
    (net (code "109") (name "Net-(C91-Pad2)") (class "Default")
      (node (ref "C91") (pin "2") (pinfunction "2_2") (pintype "passive"))
      (node (ref "R73") (pin "1") (pinfunction "1_1") (pintype "passive"))
    )
    (net (code "110") (name "Net-(C92-Pad2)") (class "Default")
      (node (ref "C92") (pin "2") (pinfunction "2_2") (pintype "passive"))
      (node (ref "R74") (pin "1") (pinfunction "1_1") (pintype "passive"))
    )
    (net (code "111") (name "Net-(C101-Pad2)") (class "Default")
      (node (ref "C101") (pin "2") (pinfunction "2_2") (pintype "passive"))
      (node (ref "R71") (pin "1") (pinfunction "1_1") (pintype "passive"))
    )
    (net (code "112") (name "Net-(C102-Pad2)") (class "Default")
      (node (ref "C102") (pin "2") (pinfunction "2_2") (pintype "passive"))
      (node (ref "R72") (pin "1") (pinfunction "1_1") (pintype "passive"))
    )
    (net (code "113") (name "Net-(C103-Pad2)") (class "Default")
      (node (ref "C103") (pin "2") (pinfunction "2_2") (pintype "passive"))
      (node (ref "R75") (pin "1") (pinfunction "1_1") (pintype "passive"))
    )
    (net (code "114") (name "Net-(C104-Pad2)") (class "Default")
      (node (ref "C104") (pin "2") (pinfunction "2_2") (pintype "passive"))
      (node (ref "R76") (pin "1") (pinfunction "1_1") (pintype "passive"))
    )
    (net (code "115") (name "Net-(C113-Pad2)") (class "Default")
      (node (ref "C113") (pin "2") (pinfunction "2_2") (pintype "passive"))
      (node (ref "R77") (pin "1") (pinfunction "1_1") (pintype "passive"))
    )
    (net (code "116") (name "Net-(C114-Pad2)") (class "Default")
      (node (ref "C114") (pin "2") (pinfunction "2_2") (pintype "passive"))
      (node (ref "R78") (pin "1") (pinfunction "1_1") (pintype "passive"))
    )
    (net (code "117") (name "Net-(C137-Pad2)") (class "Default")
      (node (ref "C137") (pin "2") (pinfunction "2_2") (pintype "passive"))
      (node (ref "R89") (pin "1") (pinfunction "1_1") (pintype "passive"))
    )
    (net (code "118") (name "Net-(C138-Pad2)") (class "Default")
      (node (ref "C138") (pin "2") (pinfunction "2_2") (pintype "passive"))
      (node (ref "R90") (pin "1") (pinfunction "1_1") (pintype "passive"))
    )
    (net (code "119") (name "Net-(C143-Pad2)") (class "Default")
      (node (ref "C143") (pin "2") (pinfunction "2_2") (pintype "passive"))
      (node (ref "R96") (pin "1") (pinfunction "1_1") (pintype "passive"))
    )
    (net (code "120") (name "Net-(C144-Pad2)") (class "Default")
      (node (ref "C144") (pin "2") (pinfunction "2_2") (pintype "passive"))
      (node (ref "R97") (pin "1") (pinfunction "1_1") (pintype "passive"))
    )
    (net (code "121") (name "Net-(IC1-+IN)") (class "Default")
      (node (ref "IC1") (pin "3") (pinfunction "+IN_3") (pintype "input"))
      (node (ref "R11") (pin "1") (pinfunction "1_1") (pintype "passive"))
      (node (ref "R12") (pin "2") (pinfunction "2_2") (pintype "passive"))
    )
    (net (code "122") (name "Net-(IC2A--IN)") (class "Default")
      (node (ref "C71") (pin "1") (pinfunction "1_1") (pintype "passive"))
      (node (ref "IC2") (pin "2") (pinfunction "-IN_2") (pintype "input"))
      (node (ref "R57") (pin "1") (pinfunction "1_1") (pintype "passive"))
      (node (ref "R58") (pin "2") (pinfunction "2_2") (pintype "passive"))
    )
    (net (code "123") (name "Net-(IC2A-OUT)") (class "Default")
      (node (ref "C71") (pin "2") (pinfunction "2_2") (pintype "passive"))
      (node (ref "C74") (pin "1") (pinfunction "1_1") (pintype "passive"))
      (node (ref "IC2") (pin "1") (pinfunction "OUT_1") (pintype "output"))
      (node (ref "R55") (pin "1") (pinfunction "1_1") (pintype "passive"))
      (node (ref "R57") (pin "2") (pinfunction "2_2") (pintype "passive"))
    )
    (net (code "124") (name "Net-(IC2B--IN)") (class "Default")
      (node (ref "C72") (pin "1") (pinfunction "1_1") (pintype "passive"))
      (node (ref "IC2") (pin "6") (pinfunction "-IN_6") (pintype "input"))
      (node (ref "R55") (pin "2") (pinfunction "2_2") (pintype "passive"))
      (node (ref "R56") (pin "1") (pinfunction "1_1") (pintype "passive"))
    )
    (net (code "125") (name "Net-(IC2B-OUT)") (class "Default")
      (node (ref "C72") (pin "2") (pinfunction "2_2") (pintype "passive"))
      (node (ref "C73") (pin "1") (pinfunction "1_1") (pintype "passive"))
      (node (ref "IC2") (pin "7") (pinfunction "OUT_7") (pintype "output"))
      (node (ref "R56") (pin "2") (pinfunction "2_2") (pintype "passive"))
    )
    (net (code "126") (name "Net-(IC3A--IN)") (class "Default")
      (node (ref "C77") (pin "1") (pinfunction "1_1") (pintype "passive"))
      (node (ref "IC3") (pin "2") (pinfunction "-IN_2") (pintype "input"))
      (node (ref "R64") (pin "1") (pinfunction "1_1") (pintype "passive"))
      (node (ref "R65") (pin "2") (pinfunction "2_2") (pintype "passive"))
    )
    (net (code "127") (name "Net-(IC3A-OUT)") (class "Default")
      (node (ref "C77") (pin "2") (pinfunction "2_2") (pintype "passive"))
      (node (ref "C80") (pin "1") (pinfunction "1_1") (pintype "passive"))
      (node (ref "IC3") (pin "1") (pinfunction "OUT_1") (pintype "output"))
      (node (ref "R62") (pin "1") (pinfunction "1_1") (pintype "passive"))
      (node (ref "R64") (pin "2") (pinfunction "2_2") (pintype "passive"))
    )
    (net (code "128") (name "Net-(IC3B--IN)") (class "Default")
      (node (ref "C78") (pin "1") (pinfunction "1_1") (pintype "passive"))
      (node (ref "IC3") (pin "6") (pinfunction "-IN_6") (pintype "input"))
      (node (ref "R62") (pin "2") (pinfunction "2_2") (pintype "passive"))
      (node (ref "R63") (pin "1") (pinfunction "1_1") (pintype "passive"))
    )
    (net (code "129") (name "Net-(IC3B-OUT)") (class "Default")
      (node (ref "C78") (pin "2") (pinfunction "2_2") (pintype "passive"))
      (node (ref "C79") (pin "1") (pinfunction "1_1") (pintype "passive"))
      (node (ref "IC3") (pin "7") (pinfunction "OUT_7") (pintype "output"))
      (node (ref "R63") (pin "2") (pinfunction "2_2") (pintype "passive"))
    )
    (net (code "130") (name "Net-(IC4A--IN)") (class "Default")
      (node (ref "C135") (pin "1") (pinfunction "1_1") (pintype "passive"))
      (node (ref "IC4") (pin "2") (pinfunction "-IN_2") (pintype "input"))
      (node (ref "R86") (pin "1") (pinfunction "1_1") (pintype "passive"))
      (node (ref "R87") (pin "2") (pinfunction "2_2") (pintype "passive"))
    )
    (net (code "131") (name "Net-(IC4A-OUT)") (class "Default")
      (node (ref "C135") (pin "2") (pinfunction "2_2") (pintype "passive"))
      (node (ref "C138") (pin "1") (pinfunction "1_1") (pintype "passive"))
      (node (ref "IC4") (pin "1") (pinfunction "OUT_1") (pintype "output"))
      (node (ref "R84") (pin "1") (pinfunction "1_1") (pintype "passive"))
      (node (ref "R86") (pin "2") (pinfunction "2_2") (pintype "passive"))
    )
    (net (code "132") (name "Net-(IC4B--IN)") (class "Default")
      (node (ref "C136") (pin "1") (pinfunction "1_1") (pintype "passive"))
      (node (ref "IC4") (pin "6") (pinfunction "-IN_6") (pintype "input"))
      (node (ref "R84") (pin "2") (pinfunction "2_2") (pintype "passive"))
      (node (ref "R85") (pin "1") (pinfunction "1_1") (pintype "passive"))
    )
    (net (code "133") (name "Net-(IC4B-OUT)") (class "Default")
      (node (ref "C136") (pin "2") (pinfunction "2_2") (pintype "passive"))
      (node (ref "C137") (pin "1") (pinfunction "1_1") (pintype "passive"))
      (node (ref "IC4") (pin "7") (pinfunction "OUT_7") (pintype "output"))
      (node (ref "R85") (pin "2") (pinfunction "2_2") (pintype "passive"))
    )
    (net (code "134") (name "Net-(IC5A--IN)") (class "Default")
      (node (ref "C141") (pin "1") (pinfunction "1_1") (pintype "passive"))
      (node (ref "IC5") (pin "2") (pinfunction "-IN_2") (pintype "input"))
      (node (ref "R93") (pin "1") (pinfunction "1_1") (pintype "passive"))
      (node (ref "R94") (pin "2") (pinfunction "2_2") (pintype "passive"))
    )
    (net (code "135") (name "Net-(IC5A-OUT)") (class "Default")
      (node (ref "C141") (pin "2") (pinfunction "2_2") (pintype "passive"))
      (node (ref "C144") (pin "1") (pinfunction "1_1") (pintype "passive"))
      (node (ref "IC5") (pin "1") (pinfunction "OUT_1") (pintype "output"))
      (node (ref "R91") (pin "1") (pinfunction "1_1") (pintype "passive"))
      (node (ref "R93") (pin "2") (pinfunction "2_2") (pintype "passive"))
    )
    (net (code "136") (name "Net-(IC5B--IN)") (class "Default")
      (node (ref "C142") (pin "1") (pinfunction "1_1") (pintype "passive"))
      (node (ref "IC5") (pin "6") (pinfunction "-IN_6") (pintype "input"))
      (node (ref "R91") (pin "2") (pinfunction "2_2") (pintype "passive"))
      (node (ref "R92") (pin "1") (pinfunction "1_1") (pintype "passive"))
    )
    (net (code "137") (name "Net-(IC5B-OUT)") (class "Default")
      (node (ref "C142") (pin "2") (pinfunction "2_2") (pintype "passive"))
      (node (ref "C143") (pin "1") (pinfunction "1_1") (pintype "passive"))
      (node (ref "IC5") (pin "7") (pinfunction "OUT_7") (pintype "output"))
      (node (ref "R92") (pin "2") (pinfunction "2_2") (pintype "passive"))
    )
    (net (code "138") (name "Net-(IC6-VBUS)") (class "Default")
      (node (ref "IC6") (pin "8") (pinfunction "VBUS_8") (pintype "input"))
      (node (ref "R20") (pin "2") (pinfunction "2_2") (pintype "passive"))
      (node (ref "R21") (pin "1") (pinfunction "1_1") (pintype "passive"))
    )
    (net (code "139") (name "Net-(IC6-~{RST})") (class "Default")
      (node (ref "IC6") (pin "9") (pinfunction "~{RST}_9") (pintype "bidirectional"))
      (node (ref "R22") (pin "2") (pinfunction "2_2") (pintype "passive"))
    )
    (net (code "140") (name "Net-(J1-D+)") (class "Default")
      (node (ref "J1") (pin "2") (pinfunction "D-_2") (pintype "bidirectional"))
      (node (ref "J1") (pin "3") (pinfunction "D+_3") (pintype "bidirectional"))
    )
    (net (code "141") (name "Net-(J2-D+)") (class "Default")
      (node (ref "J2") (pin "2") (pinfunction "D-_2") (pintype "bidirectional"))
      (node (ref "J2") (pin "3") (pinfunction "D+_3") (pintype "bidirectional"))
    )
    (net (code "142") (name "Net-(LED_SYS-PadA)") (class "Default")
      (node (ref "LED_SYS") (pin "A") (pinfunction "A_A") (pintype "passive"))
      (node (ref "R28") (pin "2") (pinfunction "2_2") (pintype "passive"))
    )
    (net (code "143") (name "Net-(Q1-PadB)") (class "Default")
      (node (ref "Q1") (pin "B") (pinfunction "B_B") (pintype "passive"))
      (node (ref "R16") (pin "2") (pinfunction "2_2") (pintype "passive"))
    )
    (net (code "144") (name "Net-(Q2-PadB)") (class "Default")
      (node (ref "Q2") (pin "B") (pinfunction "B_B") (pintype "passive"))
      (node (ref "R17") (pin "2") (pinfunction "2_2") (pintype "passive"))
    )
    (net (code "145") (name "Net-(REG1-BOOT)") (class "Default")
      (node (ref "C5") (pin "1") (pinfunction "1_1") (pintype "passive"))
      (node (ref "REG1") (pin "1") (pinfunction "BOOT_1") (pintype "bidirectional"))
    )
    (net (code "146") (name "Net-(REG1-COMP)") (class "Default")
      (node (ref "C4") (pin "1") (pinfunction "1_1") (pintype "passive"))
      (node (ref "R2") (pin "2") (pinfunction "2_2") (pintype "passive"))
      (node (ref "REG1") (pin "6") (pinfunction "COMP_6") (pintype "bidirectional"))
    )
    (net (code "147") (name "Net-(REG1-FB)") (class "Default")
      (node (ref "R3") (pin "1") (pinfunction "1_1") (pintype "passive"))
      (node (ref "R4") (pin "2") (pinfunction "2_2") (pintype "passive"))
      (node (ref "REG1") (pin "5") (pinfunction "FB_5") (pintype "bidirectional"))
    )
    (net (code "148") (name "Net-(REG1-RT_CLK)") (class "Default")
      (node (ref "R1") (pin "2") (pinfunction "2_2") (pintype "passive"))
      (node (ref "REG1") (pin "4") (pinfunction "RT_CLK_4") (pintype "bidirectional"))
    )
    (net (code "149") (name "Net-(REG2-EN)") (class "Default")
      (node (ref "R5") (pin "2") (pinfunction "2_2") (pintype "passive"))
      (node (ref "REG2") (pin "7") (pinfunction "EN_7") (pintype "input"))
    )
    (net (code "150") (name "Net-(REG2-SS)") (class "Default")
      (node (ref "C10") (pin "1") (pinfunction "1_1") (pintype "passive"))
      (node (ref "REG2") (pin "8") (pinfunction "SS_8") (pintype "passive"))
    )
    (net (code "151") (name "Net-(REG2-SW)") (class "Default")
      (node (ref "C11") (pin "2") (pinfunction "2_2") (pintype "passive"))
      (node (ref "L2") (pin "1") (pinfunction "1_1") (pintype "passive"))
      (node (ref "REG2") (pin "3") (pinfunction "SW_3") (pintype "passive"))
    )
    (net (code "152") (name "Net-(REG2-VBST)") (class "Default")
      (node (ref "C11") (pin "1") (pinfunction "1_1") (pintype "passive"))
      (node (ref "REG2") (pin "1") (pinfunction "VBST_1") (pintype "passive"))
    )
    (net (code "153") (name "Net-(REG2-VFB)") (class "Default")
      (node (ref "C52") (pin "2") (pinfunction "2_2") (pintype "passive"))
      (node (ref "R6") (pin "1") (pinfunction "1_1") (pintype "passive"))
      (node (ref "R7") (pin "2") (pinfunction "2_2") (pintype "passive"))
      (node (ref "REG2") (pin "5") (pinfunction "VFB_5") (pintype "input"))
    )
    (net (code "154") (name "Net-(REG2-VREG5)") (class "Default")
      (node (ref "C9") (pin "1") (pinfunction "1_1") (pintype "passive"))
      (node (ref "REG2") (pin "6") (pinfunction "VREG5_6") (pintype "power_in"))
    )
    (net (code "155") (name "Net-(REG3-EN)") (class "Default")
      (node (ref "R8") (pin "2") (pinfunction "2_2") (pintype "passive"))
      (node (ref "REG3") (pin "7") (pinfunction "EN_7") (pintype "input"))
    )
    (net (code "156") (name "Net-(REG3-SS)") (class "Default")
      (node (ref "C13") (pin "1") (pinfunction "1_1") (pintype "passive"))
      (node (ref "REG3") (pin "8") (pinfunction "SS_8") (pintype "passive"))
    )
    (net (code "157") (name "Net-(REG3-SW)") (class "Default")
      (node (ref "C14") (pin "2") (pinfunction "2_2") (pintype "passive"))
      (node (ref "L3") (pin "1") (pinfunction "1_1") (pintype "passive"))
      (node (ref "REG3") (pin "3") (pinfunction "SW_3") (pintype "passive"))
    )
    (net (code "158") (name "Net-(REG3-VBST)") (class "Default")
      (node (ref "C14") (pin "1") (pinfunction "1_1") (pintype "passive"))
      (node (ref "REG3") (pin "1") (pinfunction "VBST_1") (pintype "passive"))
    )
    (net (code "159") (name "Net-(REG3-VFB)") (class "Default")
      (node (ref "C16") (pin "2") (pinfunction "2_2") (pintype "passive"))
      (node (ref "R10") (pin "2") (pinfunction "2_2") (pintype "passive"))
      (node (ref "R9") (pin "1") (pinfunction "1_1") (pintype "passive"))
      (node (ref "REG3") (pin "5") (pinfunction "VFB_5") (pintype "input"))
    )
    (net (code "160") (name "Net-(REG3-VREG5)") (class "Default")
      (node (ref "C12") (pin "1") (pinfunction "1_1") (pintype "passive"))
      (node (ref "REG3") (pin "6") (pinfunction "VREG5_6") (pintype "power_in"))
    )
    (net (code "161") (name "Net-(U1-IO35)") (class "Default")
      (node (ref "R44") (pin "2") (pinfunction "2_2") (pintype "passive"))
      (node (ref "U1") (pin "7") (pinfunction "IO35_7") (pintype "bidirectional"))
    )
    (net (code "162") (name "Net-(U3A-ADC0)") (class "Default")
      (node (ref "R31") (pin "1") (pinfunction "1_1") (pintype "passive"))
      (node (ref "U3") (pin "2") (pinfunction "ADC0_2") (pintype "input"))
    )
    (net (code "163") (name "Net-(U3A-ADC1)") (class "Default")
      (node (ref "R33") (pin "1") (pinfunction "1_1") (pintype "passive"))
      (node (ref "U3") (pin "4") (pinfunction "ADC1_4") (pintype "input"))
    )
    (net (code "164") (name "Net-(U3A-ADC_RES)") (class "Default")
      (node (ref "R32") (pin "1") (pinfunction "1_1") (pintype "passive"))
      (node (ref "U3") (pin "3") (pinfunction "ADC_RES_3") (pintype "input"))
    )
    (net (code "165") (name "Net-(U3A-CM)") (class "Default")
      (node (ref "C37") (pin "2") (pinfunction "2_2") (pintype "passive"))
      (node (ref "C38") (pin "2") (pinfunction "2_2") (pintype "passive"))
      (node (ref "U3") (pin "40") (pinfunction "CM_40") (pintype "output"))
    )
    (net (code "166") (name "Net-(U3A-FILTA)") (class "Default")
      (node (ref "C35") (pin "2") (pinfunction "2_2") (pintype "passive"))
      (node (ref "C36") (pin "2") (pinfunction "2_2") (pintype "passive"))
      (node (ref "U3") (pin "47") (pinfunction "FILTA_47") (pintype "output"))
    )
    (net (code "167") (name "Net-(U3A-FILTD)") (class "Default")
      (node (ref "C33") (pin "2") (pinfunction "2_2") (pintype "passive"))
      (node (ref "C34") (pin "2") (pinfunction "2_2") (pintype "passive"))
      (node (ref "U3") (pin "41") (pinfunction "FILTD_41") (pintype "output"))
    )
    (net (code "168") (name "Net-(U3A-PLL_LF)") (class "Default")
      (node (ref "C39") (pin "1") (pinfunction "1_1") (pintype "passive"))
      (node (ref "C40") (pin "1") (pinfunction "1_1") (pintype "passive"))
      (node (ref "U3") (pin "35") (pinfunction "PLL_LF_35") (pintype "output"))
    )
    (net (code "169") (name "OUT_A_+") (class "Default")
      (node (ref "C101") (pin "1") (pinfunction "1_1") (pintype "passive"))
      (node (ref "C85") (pin "1") (pinfunction "1_1") (pintype "passive"))
      (node (ref "C93") (pin "1") (pinfunction "1_1") (pintype "passive"))
      (node (ref "L6") (pin "P$2") (pinfunction "2_P$2") (pintype "passive"))
      (node (ref "PAD1") (pin "1") (pinfunction "P_1") (pintype "passive"))
    )
    (net (code "170") (name "OUT_A_-") (class "Default")
      (node (ref "C102") (pin "1") (pinfunction "1_1") (pintype "passive"))
      (node (ref "C86") (pin "1") (pinfunction "1_1") (pintype "passive"))
      (node (ref "C94") (pin "1") (pinfunction "1_1") (pintype "passive"))
      (node (ref "L7") (pin "P$2") (pinfunction "2_P$2") (pintype "passive"))
      (node (ref "PAD2") (pin "1") (pinfunction "P_1") (pintype "passive"))
    )
    (net (code "171") (name "OUT_B_+") (class "Default")
      (node (ref "C87") (pin "1") (pinfunction "1_1") (pintype "passive"))
      (node (ref "C89") (pin "1") (pinfunction "1_1") (pintype "passive"))
      (node (ref "C91") (pin "1") (pinfunction "1_1") (pintype "passive"))
      (node (ref "L8") (pin "P$2") (pinfunction "2_P$2") (pintype "passive"))
      (node (ref "PAD4") (pin "1") (pinfunction "P_1") (pintype "passive"))
    )
    (net (code "172") (name "OUT_B_-") (class "Default")
      (node (ref "C88") (pin "1") (pinfunction "1_1") (pintype "passive"))
      (node (ref "C90") (pin "1") (pinfunction "1_1") (pintype "passive"))
      (node (ref "C92") (pin "1") (pinfunction "1_1") (pintype "passive"))
      (node (ref "L9") (pin "P$2") (pinfunction "2_P$2") (pintype "passive"))
      (node (ref "PAD3") (pin "1") (pinfunction "P_1") (pintype "passive"))
    )
    (net (code "173") (name "OUT_C_+") (class "Default")
      (node (ref "C103") (pin "1") (pinfunction "1_1") (pintype "passive"))
      (node (ref "C97") (pin "1") (pinfunction "1_1") (pintype "passive"))
      (node (ref "C99") (pin "1") (pinfunction "1_1") (pintype "passive"))
      (node (ref "L10") (pin "P$2") (pinfunction "2_P$2") (pintype "passive"))
      (node (ref "PAD5") (pin "1") (pinfunction "P_1") (pintype "passive"))
    )
    (net (code "174") (name "OUT_C_-") (class "Default")
      (node (ref "C100") (pin "1") (pinfunction "1_1") (pintype "passive"))
      (node (ref "C104") (pin "1") (pinfunction "1_1") (pintype "passive"))
      (node (ref "C98") (pin "1") (pinfunction "1_1") (pintype "passive"))
      (node (ref "L11") (pin "P$2") (pinfunction "2_P$2") (pintype "passive"))
      (node (ref "PAD6") (pin "1") (pinfunction "P_1") (pintype "passive"))
    )
    (net (code "175") (name "OUT_D_+") (class "Default")
      (node (ref "C107") (pin "1") (pinfunction "1_1") (pintype "passive"))
      (node (ref "C111") (pin "1") (pinfunction "1_1") (pintype "passive"))
      (node (ref "C113") (pin "1") (pinfunction "1_1") (pintype "passive"))
      (node (ref "L12") (pin "P$2") (pinfunction "2_P$2") (pintype "passive"))
      (node (ref "PAD8") (pin "1") (pinfunction "P_1") (pintype "passive"))
    )
    (net (code "176") (name "OUT_D_-") (class "Default")
      (node (ref "C108") (pin "1") (pinfunction "1_1") (pintype "passive"))
      (node (ref "C112") (pin "1") (pinfunction "1_1") (pintype "passive"))
      (node (ref "C114") (pin "1") (pinfunction "1_1") (pintype "passive"))
      (node (ref "L13") (pin "P$2") (pinfunction "2_P$2") (pintype "passive"))
      (node (ref "PAD7") (pin "1") (pinfunction "P_1") (pintype "passive"))
    )
    (net (code "177") (name "P12V_EN") (class "Default")
      (node (ref "REG1") (pin "3") (pinfunction "EN_3") (pintype "bidirectional"))
    )
    (net (code "178") (name "POT0") (class "Default")
      (node (ref "POT0") (pin "S") (pinfunction "S_S") (pintype "passive"))
      (node (ref "U3") (pin "26") (pinfunction "MP9_26") (pintype "bidirectional"))
    )
    (net (code "179") (name "POT1") (class "Default")
      (node (ref "POT1") (pin "S") (pinfunction "S_S") (pintype "passive"))
      (node (ref "U3") (pin "27") (pinfunction "MP8_27") (pintype "bidirectional"))
    )
    (net (code "180") (name "POT2") (class "Default")
      (node (ref "POT2") (pin "S") (pinfunction "S_S") (pintype "passive"))
      (node (ref "U3") (pin "28") (pinfunction "MP3_28") (pintype "bidirectional"))
    )
    (net (code "181") (name "POT3") (class "Default")
      (node (ref "POT3") (pin "S") (pinfunction "S_S") (pintype "passive"))
      (node (ref "U3") (pin "29") (pinfunction "MP2_29") (pintype "bidirectional"))
    )
    (net (code "182") (name "R12V_SW") (class "Default")
      (node (ref "C5") (pin "2") (pinfunction "2_2") (pintype "passive"))
      (node (ref "D1") (pin "2") (pinfunction "C_2") (pintype "passive"))
      (node (ref "L1") (pin "P$1") (pinfunction "1_P$1") (pintype "passive"))
      (node (ref "REG1") (pin "8") (pinfunction "SW_8") (pintype "bidirectional"))
    )
    (net (code "183") (name "SD_CARDDETECTION") (class "Default")
      (node (ref "J7") (pin "9") (pinfunction "CD_SWITCH1_9") (pintype "bidirectional"))
      (node (ref "U1") (pin "27") (pinfunction "IO16_27") (pintype "bidirectional"))
    )
    (net (code "184") (name "SD_CD{slash}DAT3") (class "Default")
      (node (ref "J7") (pin "2") (pinfunction "CARD_DETECT/DATA_LINE[BIT_3]_2") (pintype "bidirectional"))
      (node (ref "R46") (pin "2") (pinfunction "2_2") (pintype "passive"))
      (node (ref "U1") (pin "16") (pinfunction "IO13_16") (pintype "bidirectional"))
    )
    (net (code "185") (name "SD_CLK") (class "Default")
      (node (ref "J7") (pin "5") (pinfunction "CLOCK_5") (pintype "bidirectional"))
      (node (ref "U1") (pin "13") (pinfunction "IO14_13") (pintype "bidirectional"))
    )
    (net (code "186") (name "SD_CMD") (class "Default")
      (node (ref "J7") (pin "3") (pinfunction "COMMAND/RESPONSE_3") (pintype "bidirectional"))
      (node (ref "R47") (pin "2") (pinfunction "2_2") (pintype "passive"))
      (node (ref "U1") (pin "23") (pinfunction "IO15_23") (pintype "bidirectional"))
    )
    (net (code "187") (name "SD_DAT0") (class "Default")
      (node (ref "J7") (pin "7") (pinfunction "DATA_LINE[BIT_0]_7") (pintype "bidirectional"))
      (node (ref "R48") (pin "2") (pinfunction "2_2") (pintype "passive"))
      (node (ref "U1") (pin "24") (pinfunction "IO2_24") (pintype "bidirectional"))
    )
    (net (code "188") (name "SD_DAT1") (class "Default")
      (node (ref "J7") (pin "8") (pinfunction "DATA_LINE[BIT_1]_8") (pintype "bidirectional"))
      (node (ref "R49") (pin "2") (pinfunction "2_2") (pintype "passive"))
      (node (ref "U1") (pin "26") (pinfunction "IO4_26") (pintype "bidirectional"))
    )
    (net (code "189") (name "SD_DAT2") (class "Default")
      (node (ref "J7") (pin "1") (pinfunction "DATA_LINE[BIT_2]_1") (pintype "bidirectional"))
      (node (ref "R45") (pin "2") (pinfunction "2_2") (pintype "passive"))
      (node (ref "U1") (pin "14") (pinfunction "IO12_14") (pintype "bidirectional"))
    )
    (net (code "190") (name "SER_DTR") (class "Default")
      (node (ref "IC6") (pin "28") (pinfunction "DTR_28") (pintype "output"))
      (node (ref "Q2") (pin "E") (pinfunction "E_E") (pintype "passive"))
      (node (ref "R16") (pin "1") (pinfunction "1_1") (pintype "passive"))
    )
    (net (code "191") (name "SER_RTS") (class "Default")
      (node (ref "IC6") (pin "24") (pinfunction "RTS_24") (pintype "output"))
      (node (ref "Q1") (pin "E") (pinfunction "E_E") (pintype "passive"))
      (node (ref "R17") (pin "1") (pinfunction "1_1") (pintype "passive"))
    )
    (net (code "192") (name "USBC_CC1") (class "Default")
      (node (ref "J3") (pin "3") (pinfunction "CC1_3") (pintype "passive"))
      (node (ref "R18") (pin "1") (pinfunction "1_1") (pintype "passive"))
    )
    (net (code "193") (name "USBC_CC2") (class "Default")
      (node (ref "J3") (pin "9") (pinfunction "CC2_9") (pintype "passive"))
      (node (ref "R19") (pin "1") (pinfunction "1_1") (pintype "passive"))
    )
    (net (code "194") (name "USBC_D_N") (class "Default")
      (node (ref "J3") (pin "5") (pinfunction "D-_5") (pintype "passive"))
      (node (ref "J3") (pin "8") (pinfunction "D-_8") (pintype "passive"))
      (node (ref "VD1") (pin "3") (pinfunction "I/O_2_3") (pintype "bidirectional"))
    )
    (net (code "195") (name "USBC_D_P") (class "Default")
      (node (ref "J3") (pin "6") (pinfunction "D+_6") (pintype "passive"))
      (node (ref "J3") (pin "7") (pinfunction "D+_7") (pintype "passive"))
      (node (ref "VD1") (pin "1") (pinfunction "I/O_1_1") (pintype "bidirectional"))
    )
    (net (code "196") (name "USBC_VBUS") (class "Default")
      (node (ref "J3") (pin "11") (pinfunction "VBUS_11") (pintype "power_in"))
      (node (ref "J3") (pin "2") (pinfunction "VBUS_2") (pintype "power_in"))
      (node (ref "R20") (pin "1") (pinfunction "1_1") (pintype "passive"))
      (node (ref "VD1") (pin "5") (pinfunction "VBUS_5") (pintype "bidirectional"))
    )
    (net (code "197") (name "V+") (class "Default")
      (node (ref "AMP1") (pin "P$29") (pinfunction "PVDD_CD_P$29") (pintype "bidirectional"))
      (node (ref "AMP1") (pin "P$30") (pinfunction "PVDD_CD_P$30") (pintype "bidirectional"))
      (node (ref "AMP1") (pin "P$31") (pinfunction "PVDD_CD_P$31") (pintype "bidirectional"))
      (node (ref "AMP1") (pin "P$36") (pinfunction "PVDD_AB_P$36") (pintype "bidirectional"))
      (node (ref "AMP1") (pin "P$37") (pinfunction "PVDD_AB_P$37") (pintype "bidirectional"))
      (node (ref "AMP1") (pin "P$38") (pinfunction "PVDD_AB_P$38") (pintype "bidirectional"))
      (node (ref "AMP2") (pin "P$29") (pinfunction "PVDD_CD_P$29") (pintype "bidirectional"))
      (node (ref "AMP2") (pin "P$30") (pinfunction "PVDD_CD_P$30") (pintype "bidirectional"))
      (node (ref "AMP2") (pin "P$31") (pinfunction "PVDD_CD_P$31") (pintype "bidirectional"))
      (node (ref "AMP2") (pin "P$36") (pinfunction "PVDD_AB_P$36") (pintype "bidirectional"))
      (node (ref "AMP2") (pin "P$37") (pinfunction "PVDD_AB_P$37") (pintype "bidirectional"))
      (node (ref "AMP2") (pin "P$38") (pinfunction "PVDD_AB_P$38") (pintype "bidirectional"))
      (node (ref "C120") (pin "1") (pinfunction "1_1") (pintype "passive"))
      (node (ref "C121") (pin "1") (pinfunction "1_1") (pintype "passive"))
      (node (ref "C122") (pin "1") (pinfunction "1_1") (pintype "passive"))
      (node (ref "C123") (pin "1") (pinfunction "1_1") (pintype "passive"))
      (node (ref "C124") (pin "+") (pinfunction "+_+") (pintype "passive"))
      (node (ref "C125") (pin "+") (pinfunction "+_+") (pintype "passive"))
      (node (ref "C2") (pin "+") (pinfunction "+_+") (pintype "passive"))
      (node (ref "C55") (pin "1") (pinfunction "1_1") (pintype "passive"))
      (node (ref "C56") (pin "1") (pinfunction "1_1") (pintype "passive"))
      (node (ref "C57") (pin "1") (pinfunction "1_1") (pintype "passive"))
      (node (ref "C58") (pin "1") (pinfunction "1_1") (pintype "passive"))
      (node (ref "C59") (pin "+") (pinfunction "+_+") (pintype "passive"))
      (node (ref "C60") (pin "+") (pinfunction "+_+") (pintype "passive"))
      (node (ref "R11") (pin "2") (pinfunction "2_2") (pintype "passive"))
      (node (ref "REG1") (pin "2") (pinfunction "VIN_2") (pintype "bidirectional"))
      (node (ref "U$1") (pin "+") (pinfunction "VCC_+") (pintype "bidirectional"))
    )
    (net (code "198") (name "VBAT_MEASURE") (class "Default")
      (node (ref "IC1") (pin "2") (pinfunction "-IN_2") (pintype "input"))
      (node (ref "IC1") (pin "6") (pinfunction "OUT_6") (pintype "output"))
      (node (ref "R44") (pin "1") (pinfunction "1_1") (pintype "passive"))
    )
    (net (code "199") (name "VMID") (class "Default")
      (node (ref "C83") (pin "1") (pinfunction "1_1") (pintype "passive"))
      (node (ref "C84") (pin "1") (pinfunction "1_1") (pintype "passive"))
      (node (ref "IC2") (pin "3") (pinfunction "+IN_3") (pintype "input"))
      (node (ref "IC2") (pin "5") (pinfunction "+IN_5") (pintype "input"))
      (node (ref "IC3") (pin "3") (pinfunction "+IN_3") (pintype "input"))
      (node (ref "IC3") (pin "5") (pinfunction "+IN_5") (pintype "input"))
      (node (ref "R69") (pin "2") (pinfunction "2_2") (pintype "passive"))
      (node (ref "R70") (pin "2") (pinfunction "2_2") (pintype "passive"))
    )
    (net (code "200") (name "VMID1") (class "Default")
      (node (ref "C147") (pin "1") (pinfunction "1_1") (pintype "passive"))
      (node (ref "C148") (pin "1") (pinfunction "1_1") (pintype "passive"))
      (node (ref "IC4") (pin "3") (pinfunction "+IN_3") (pintype "input"))
      (node (ref "IC4") (pin "5") (pinfunction "+IN_5") (pintype "input"))
      (node (ref "IC5") (pin "3") (pinfunction "+IN_3") (pintype "input"))
      (node (ref "IC5") (pin "5") (pinfunction "+IN_5") (pintype "input"))
      (node (ref "R98") (pin "2") (pinfunction "2_2") (pintype "passive"))
      (node (ref "R99") (pin "2") (pinfunction "2_2") (pintype "passive"))
    )
    (net (code "201") (name "unconnected-(AMP1-OC_IOM-PadP$9)") (class "Default")
      (node (ref "AMP1") (pin "P$9") (pinfunction "OC_IOM_P$9") (pintype "bidirectional"))
    )
    (net (code "202") (name "unconnected-(AMP1-OC_IOP-PadP$10)") (class "Default")
      (node (ref "AMP1") (pin "P$10") (pinfunction "OC_IOP_P$10") (pintype "bidirectional"))
    )
    (net (code "203") (name "unconnected-(AMP2-OC_IOM-PadP$9)") (class "Default")
      (node (ref "AMP2") (pin "P$9") (pinfunction "OC_IOM_P$9") (pintype "bidirectional"))
    )
    (net (code "204") (name "unconnected-(AMP2-OC_IOP-PadP$10)") (class "Default")
      (node (ref "AMP2") (pin "P$10") (pinfunction "OC_IOP_P$10") (pintype "bidirectional"))
    )
    (net (code "205") (name "unconnected-(IC1-ON1-Pad1)") (class "Default")
      (node (ref "IC1") (pin "1") (pinfunction "ON1_1") (pintype "passive"))
    )
    (net (code "206") (name "unconnected-(IC1-ON2-Pad5)") (class "Default")
      (node (ref "IC1") (pin "5") (pinfunction "ON2_5") (pintype "passive"))
    )
    (net (code "207") (name "unconnected-(IC1-OPT-Pad8)") (class "Default")
      (node (ref "IC1") (pin "8") (pinfunction "OPT_8") (pintype "passive"))
    )
    (net (code "208") (name "unconnected-(IC6-CTS-Pad23)") (class "Default")
      (node (ref "IC6") (pin "23") (pinfunction "CTS_23") (pintype "input"))
    )
    (net (code "209") (name "unconnected-(IC6-DCD-Pad1)") (class "Default")
      (node (ref "IC6") (pin "1") (pinfunction "DCD_1") (pintype "input"))
    )
    (net (code "210") (name "unconnected-(IC6-DSR-Pad27)") (class "Default")
      (node (ref "IC6") (pin "27") (pinfunction "DSR_27") (pintype "input"))
    )
    (net (code "211") (name "unconnected-(IC6-RI-Pad2)") (class "Default")
      (node (ref "IC6") (pin "2") (pinfunction "RI_2") (pintype "input"))
    )
    (net (code "212") (name "unconnected-(IC6-SUSPEND-Pad12)") (class "Default")
      (node (ref "IC6") (pin "12") (pinfunction "SUSPEND_12") (pintype "output"))
    )
    (net (code "213") (name "unconnected-(IC6-~{SUSPEND}-Pad11)") (class "Default")
      (node (ref "IC6") (pin "11") (pinfunction "~{SUSPEND}_11") (pintype "output"))
    )
    (net (code "214") (name "unconnected-(J3-SBU1-Pad10)") (class "Default")
      (node (ref "J3") (pin "10") (pinfunction "SBU1_10") (pintype "passive"))
    )
    (net (code "215") (name "unconnected-(J3-SBU2-Pad4)") (class "Default")
      (node (ref "J3") (pin "4") (pinfunction "SBU2_4") (pintype "passive"))
    )
    (net (code "216") (name "unconnected-(J7-CD_SWITCH2-Pad10)") (class "Default")
      (node (ref "J7") (pin "10") (pinfunction "CD_SWITCH2_10") (pintype "bidirectional"))
    )
    (net (code "217") (name "unconnected-(U1-CLK-Pad20)") (class "Default")
      (node (ref "U1") (pin "20") (pinfunction "CLK_20") (pintype "bidirectional"))
    )
    (net (code "218") (name "unconnected-(U1-CMD-Pad19)") (class "Default")
      (node (ref "U1") (pin "19") (pinfunction "CMD_19") (pintype "bidirectional"))
    )
    (net (code "219") (name "unconnected-(U1-SD0-Pad21)") (class "Default")
      (node (ref "U1") (pin "21") (pinfunction "SD0_21") (pintype "bidirectional"))
    )
    (net (code "220") (name "unconnected-(U1-SD1-Pad22)") (class "Default")
      (node (ref "U1") (pin "22") (pinfunction "SD1_22") (pintype "bidirectional"))
    )
    (net (code "221") (name "unconnected-(U1-SD2-Pad17)") (class "Default")
      (node (ref "U1") (pin "17") (pinfunction "SD2_17") (pintype "bidirectional"))
    )
    (net (code "222") (name "unconnected-(U1-SD3-Pad18)") (class "Default")
      (node (ref "U1") (pin "18") (pinfunction "SD3_18") (pintype "bidirectional"))
    )
    (net (code "223") (name "unconnected-(U1-SENSOR_VN-Pad5)") (class "Default")
      (node (ref "U1") (pin "5") (pinfunction "SENSOR_VN_5") (pintype "bidirectional"))
    )
    (net (code "224") (name "unconnected-(U1-SENSOR_VP-Pad4)") (class "Default")
      (node (ref "U1") (pin "4") (pinfunction "SENSOR_VP_4") (pintype "bidirectional"))
    )
    (net (code "225") (name "unconnected-(U3A-CLATCH{slash}WP-Pad21)") (class "Default")
      (node (ref "U3") (pin "21") (pinfunction "CLATCH/WP_21") (pintype "bidirectional"))
    )
  )
)
